# EEZ_DIB_MIO168_r1B5.net
KiCad netlist of a schematic drawn in EAGLE
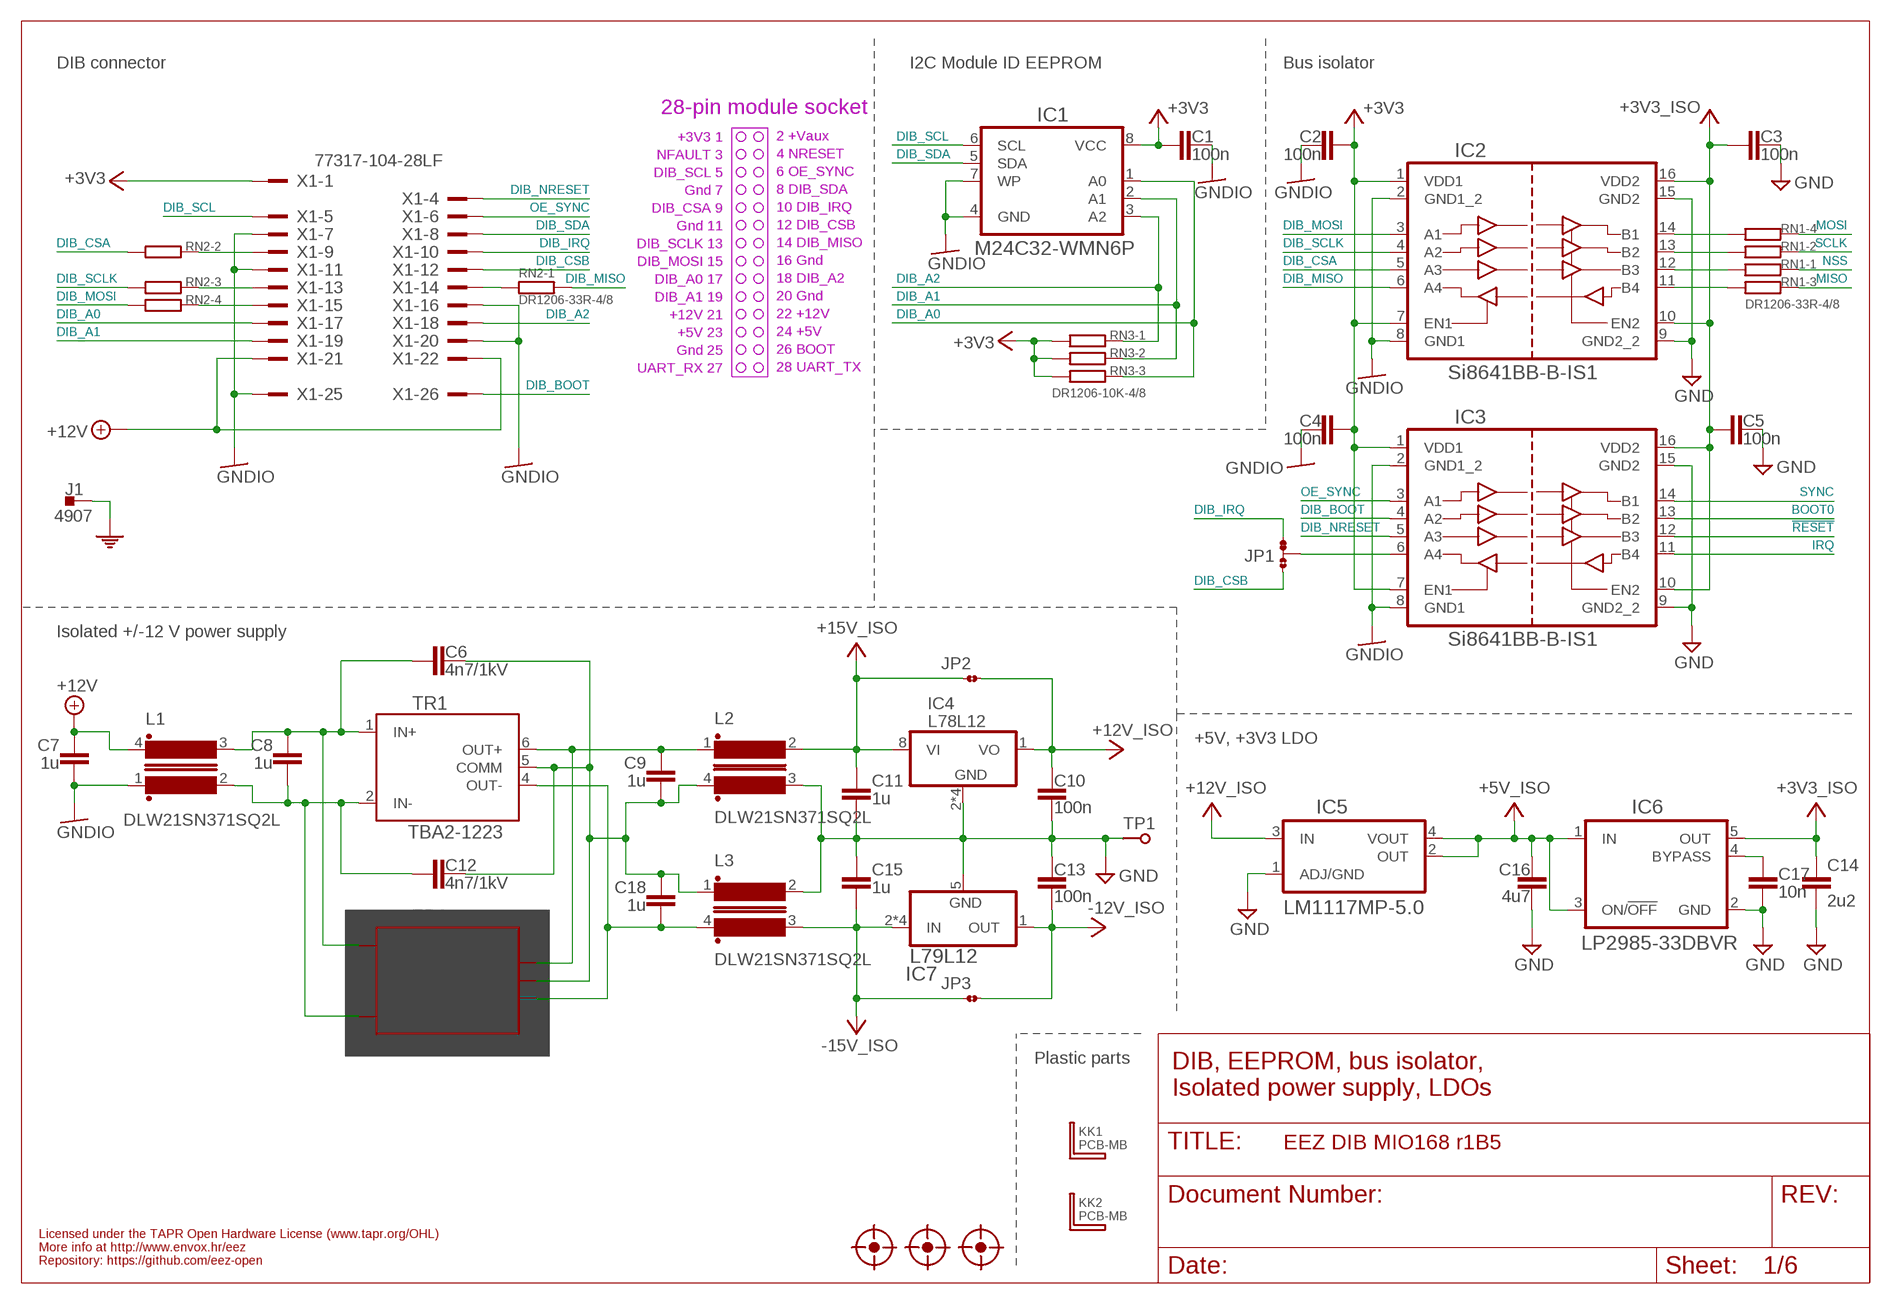
[diagram p0: schematic, sheet 1]
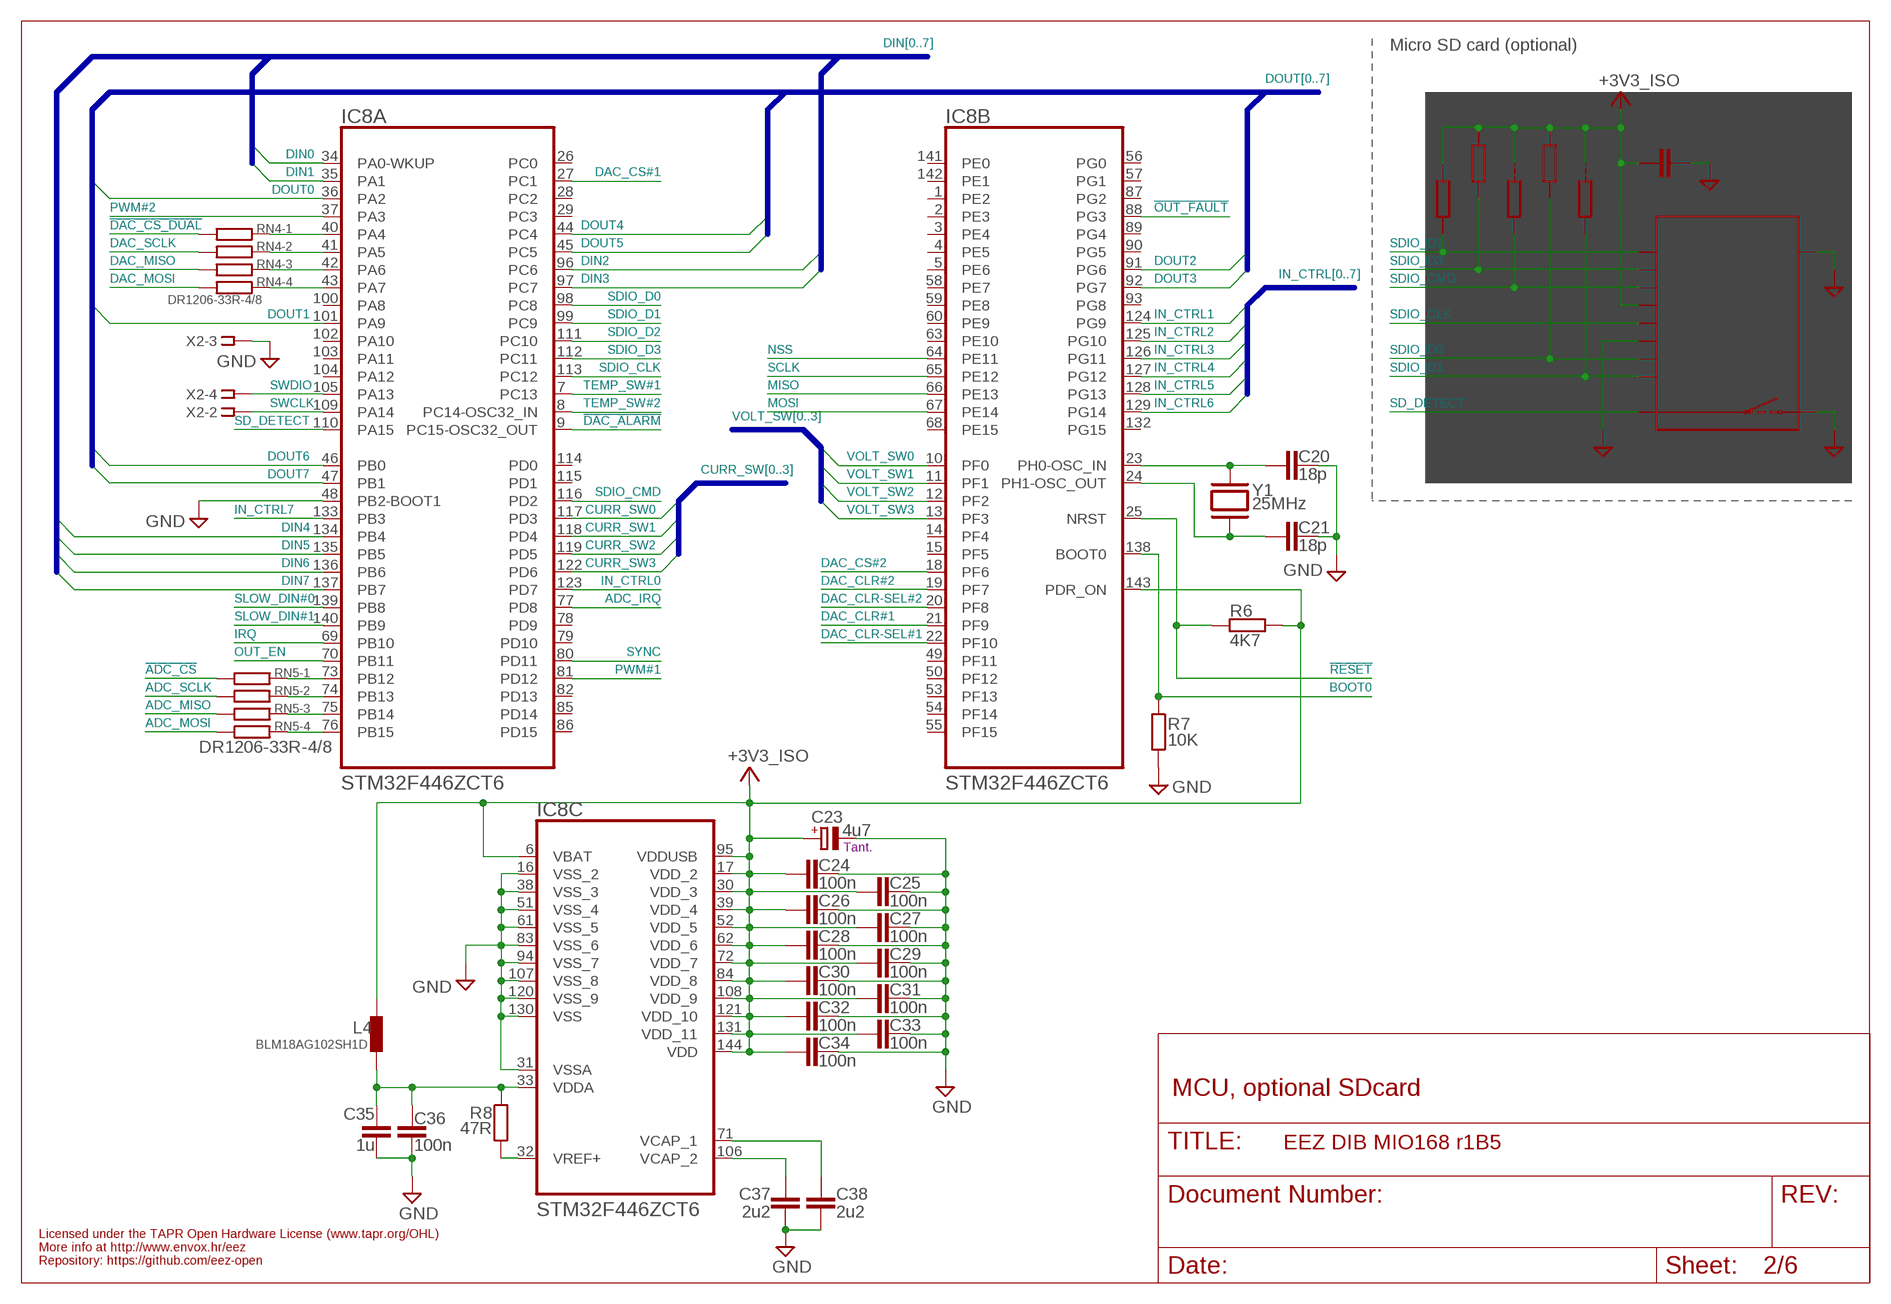
[diagram p1: schematic, sheet 2]
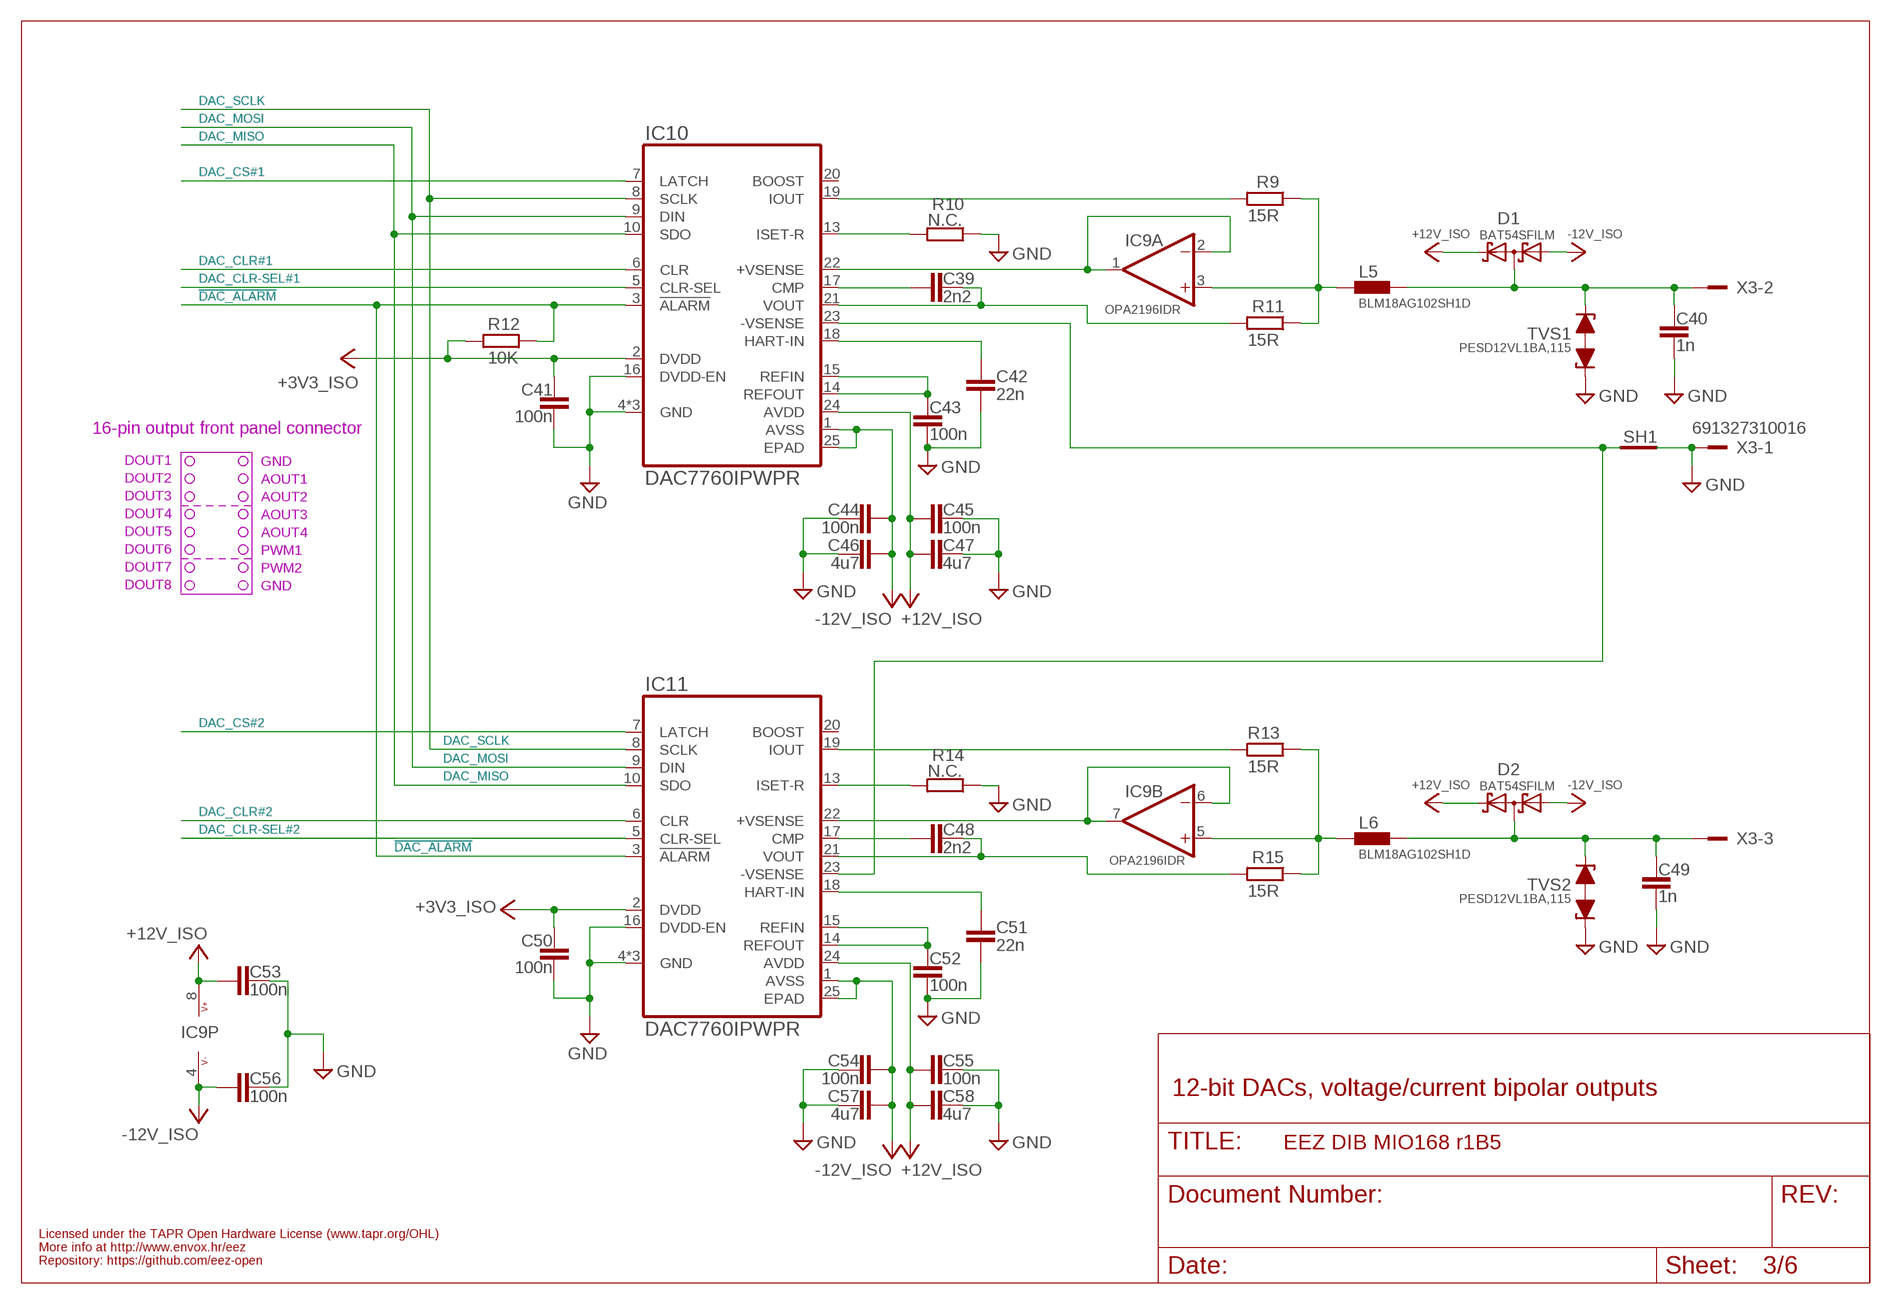
[diagram p2: schematic, sheet 3]
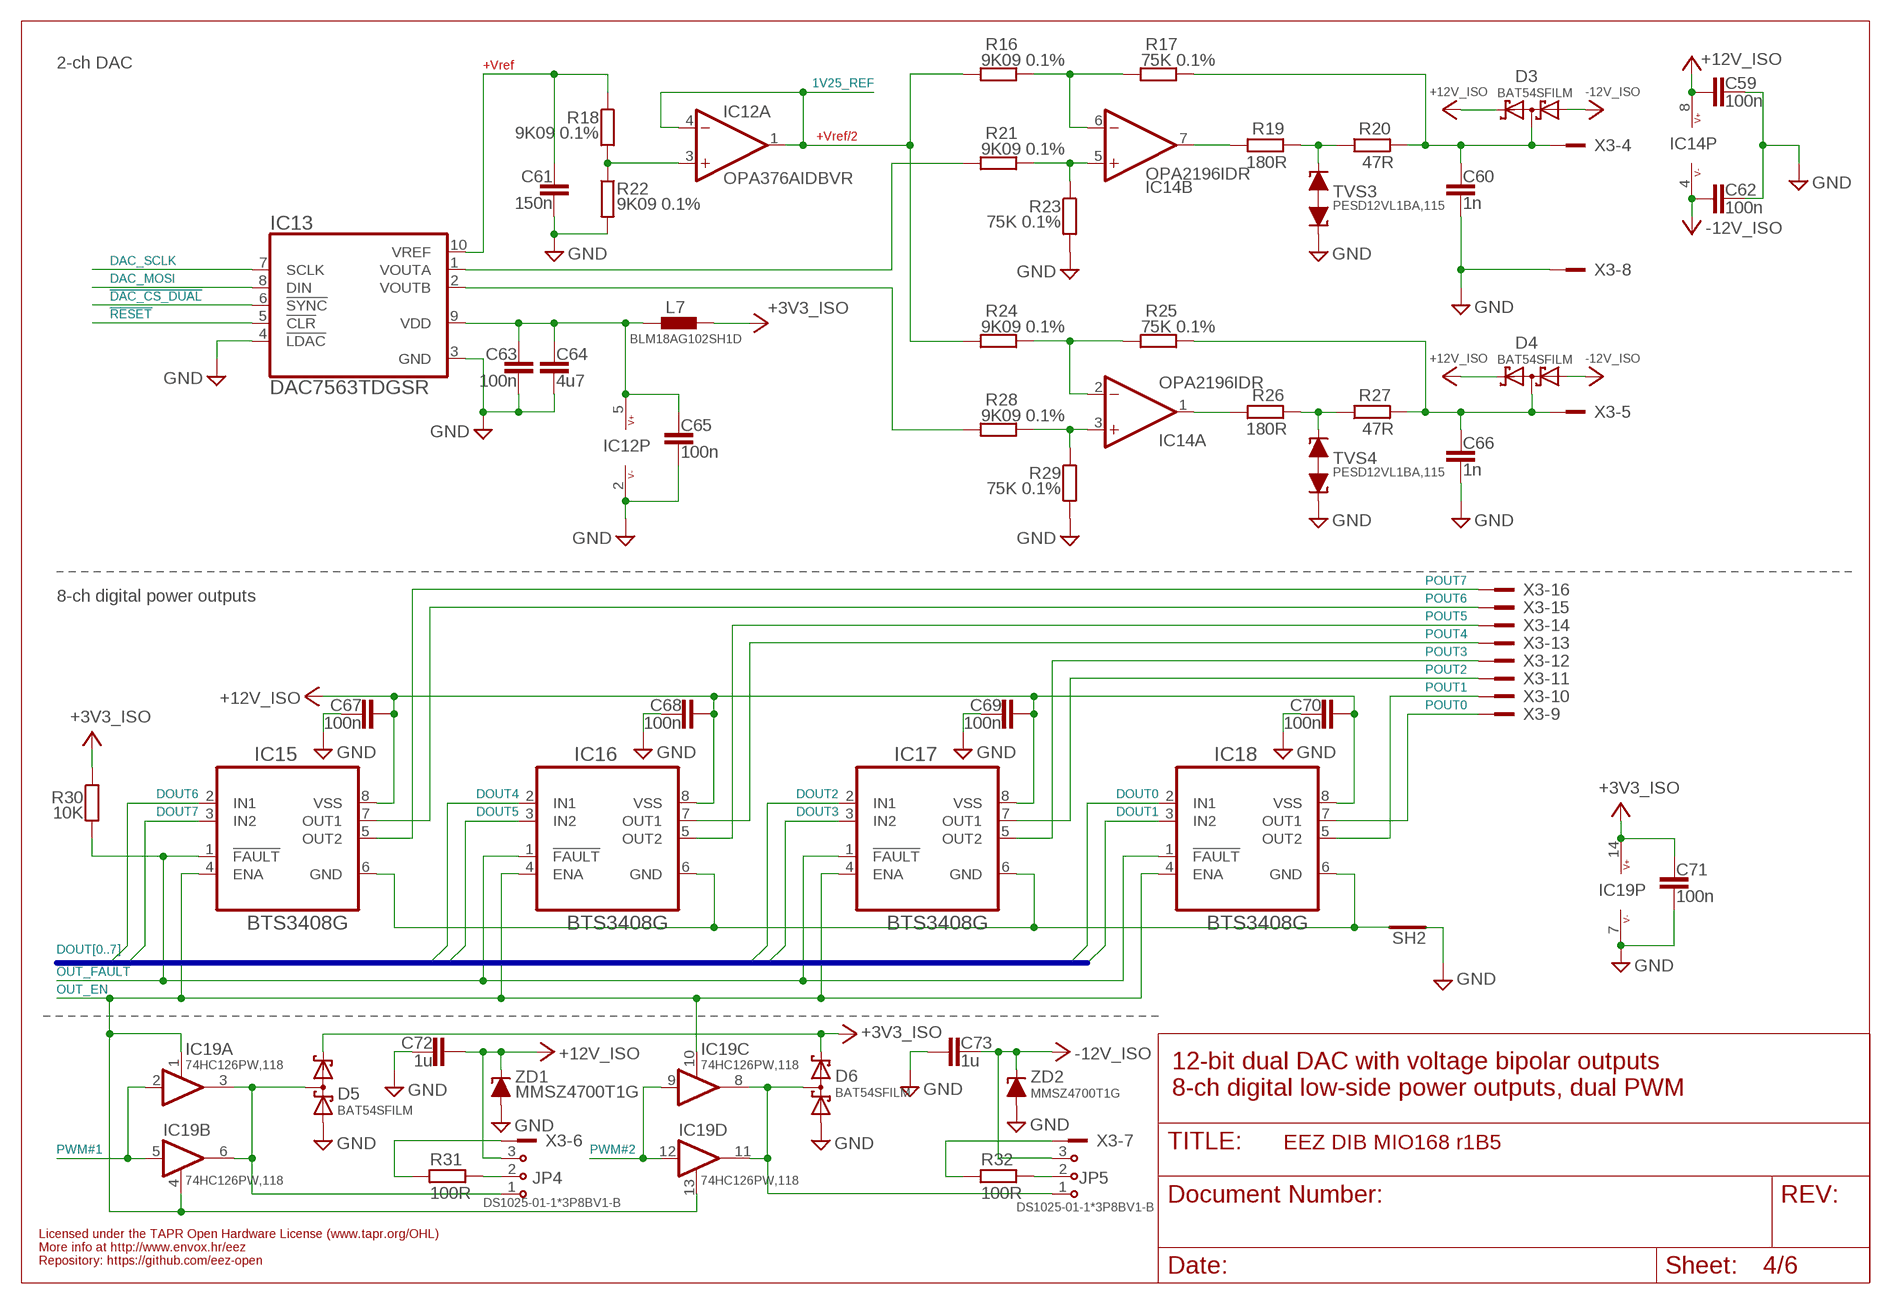
[diagram p3: schematic, sheet 4]
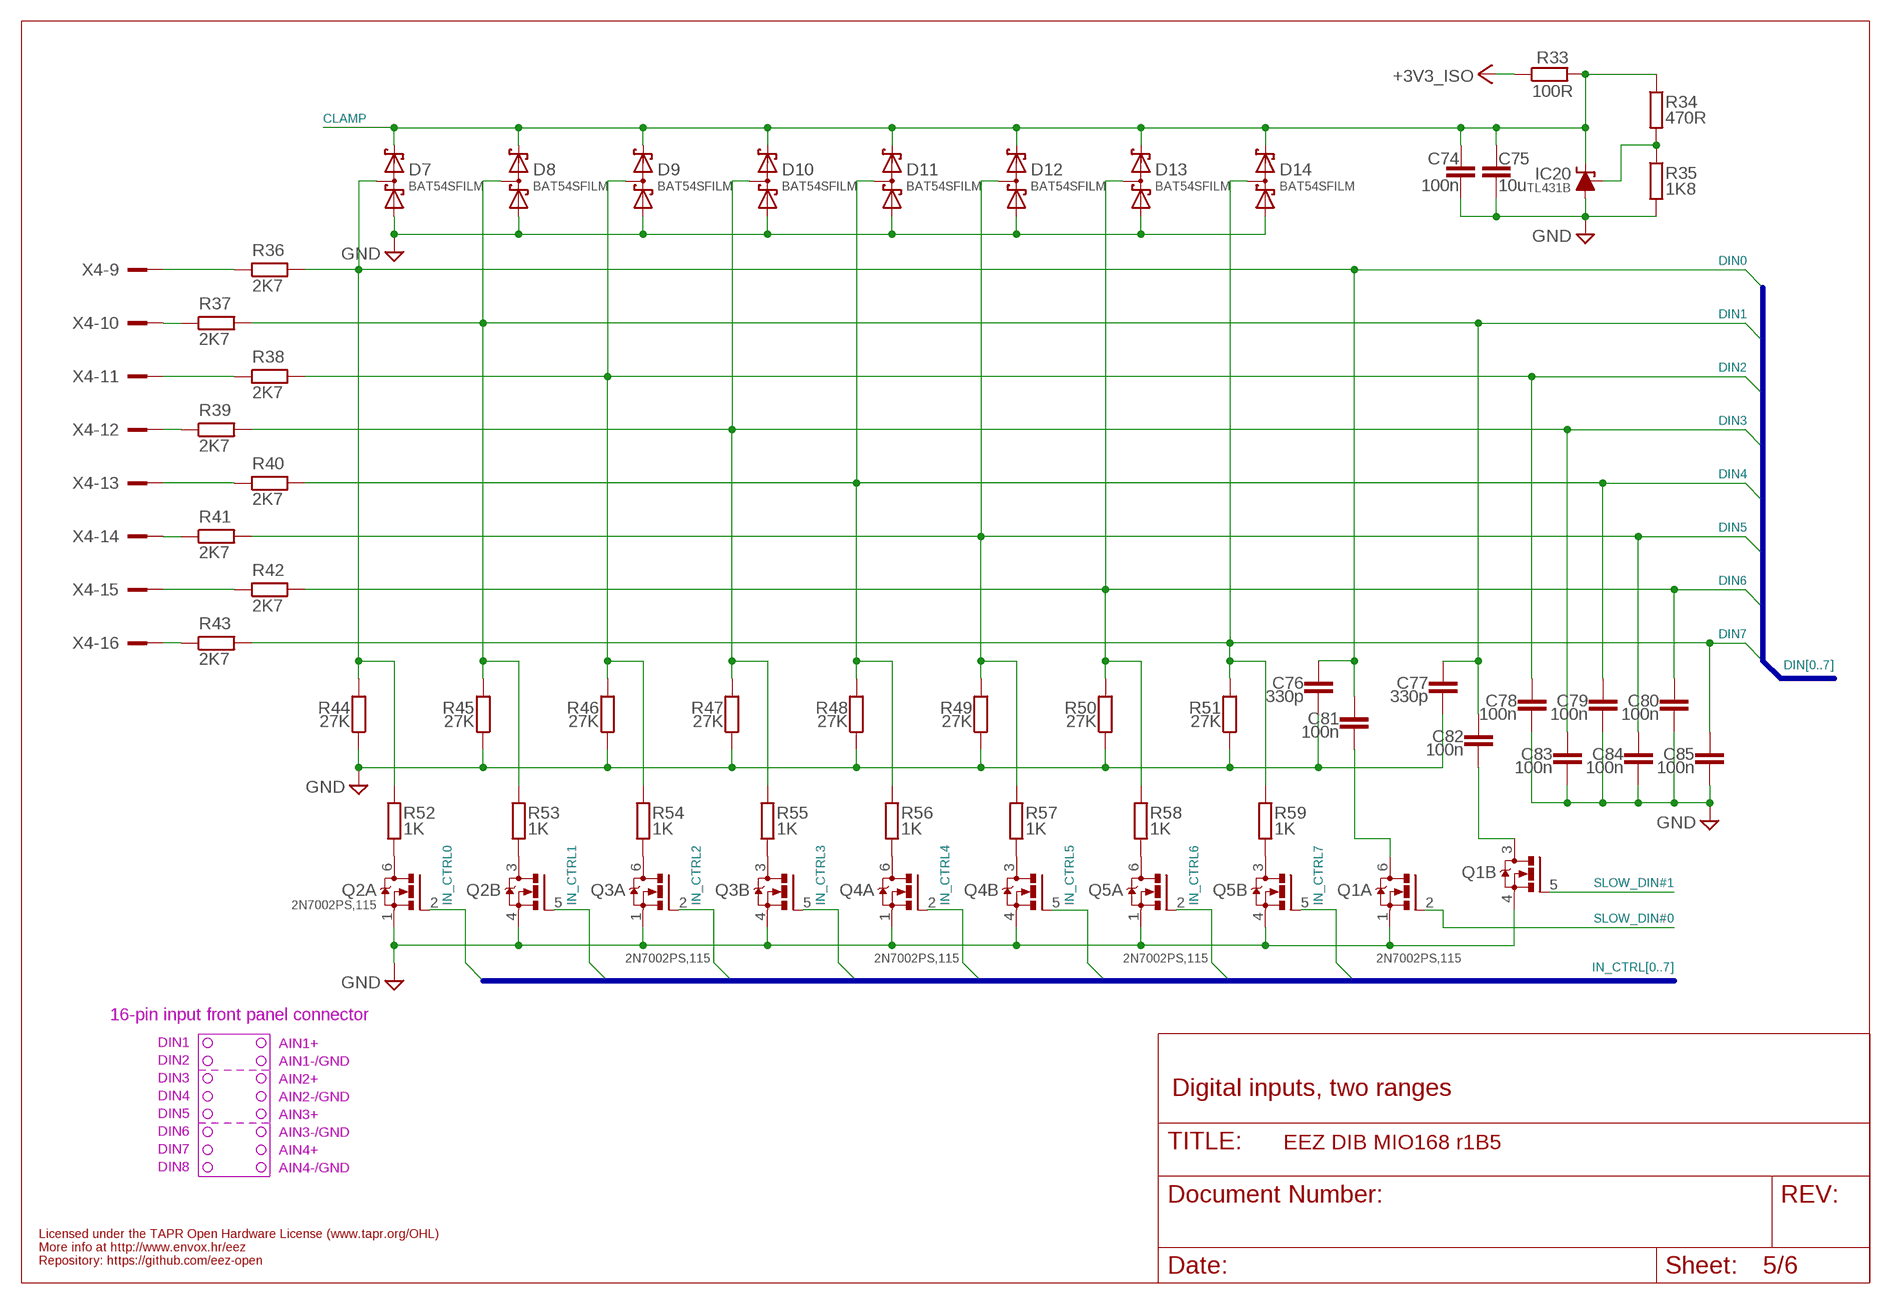
[diagram p4: schematic, sheet 5]
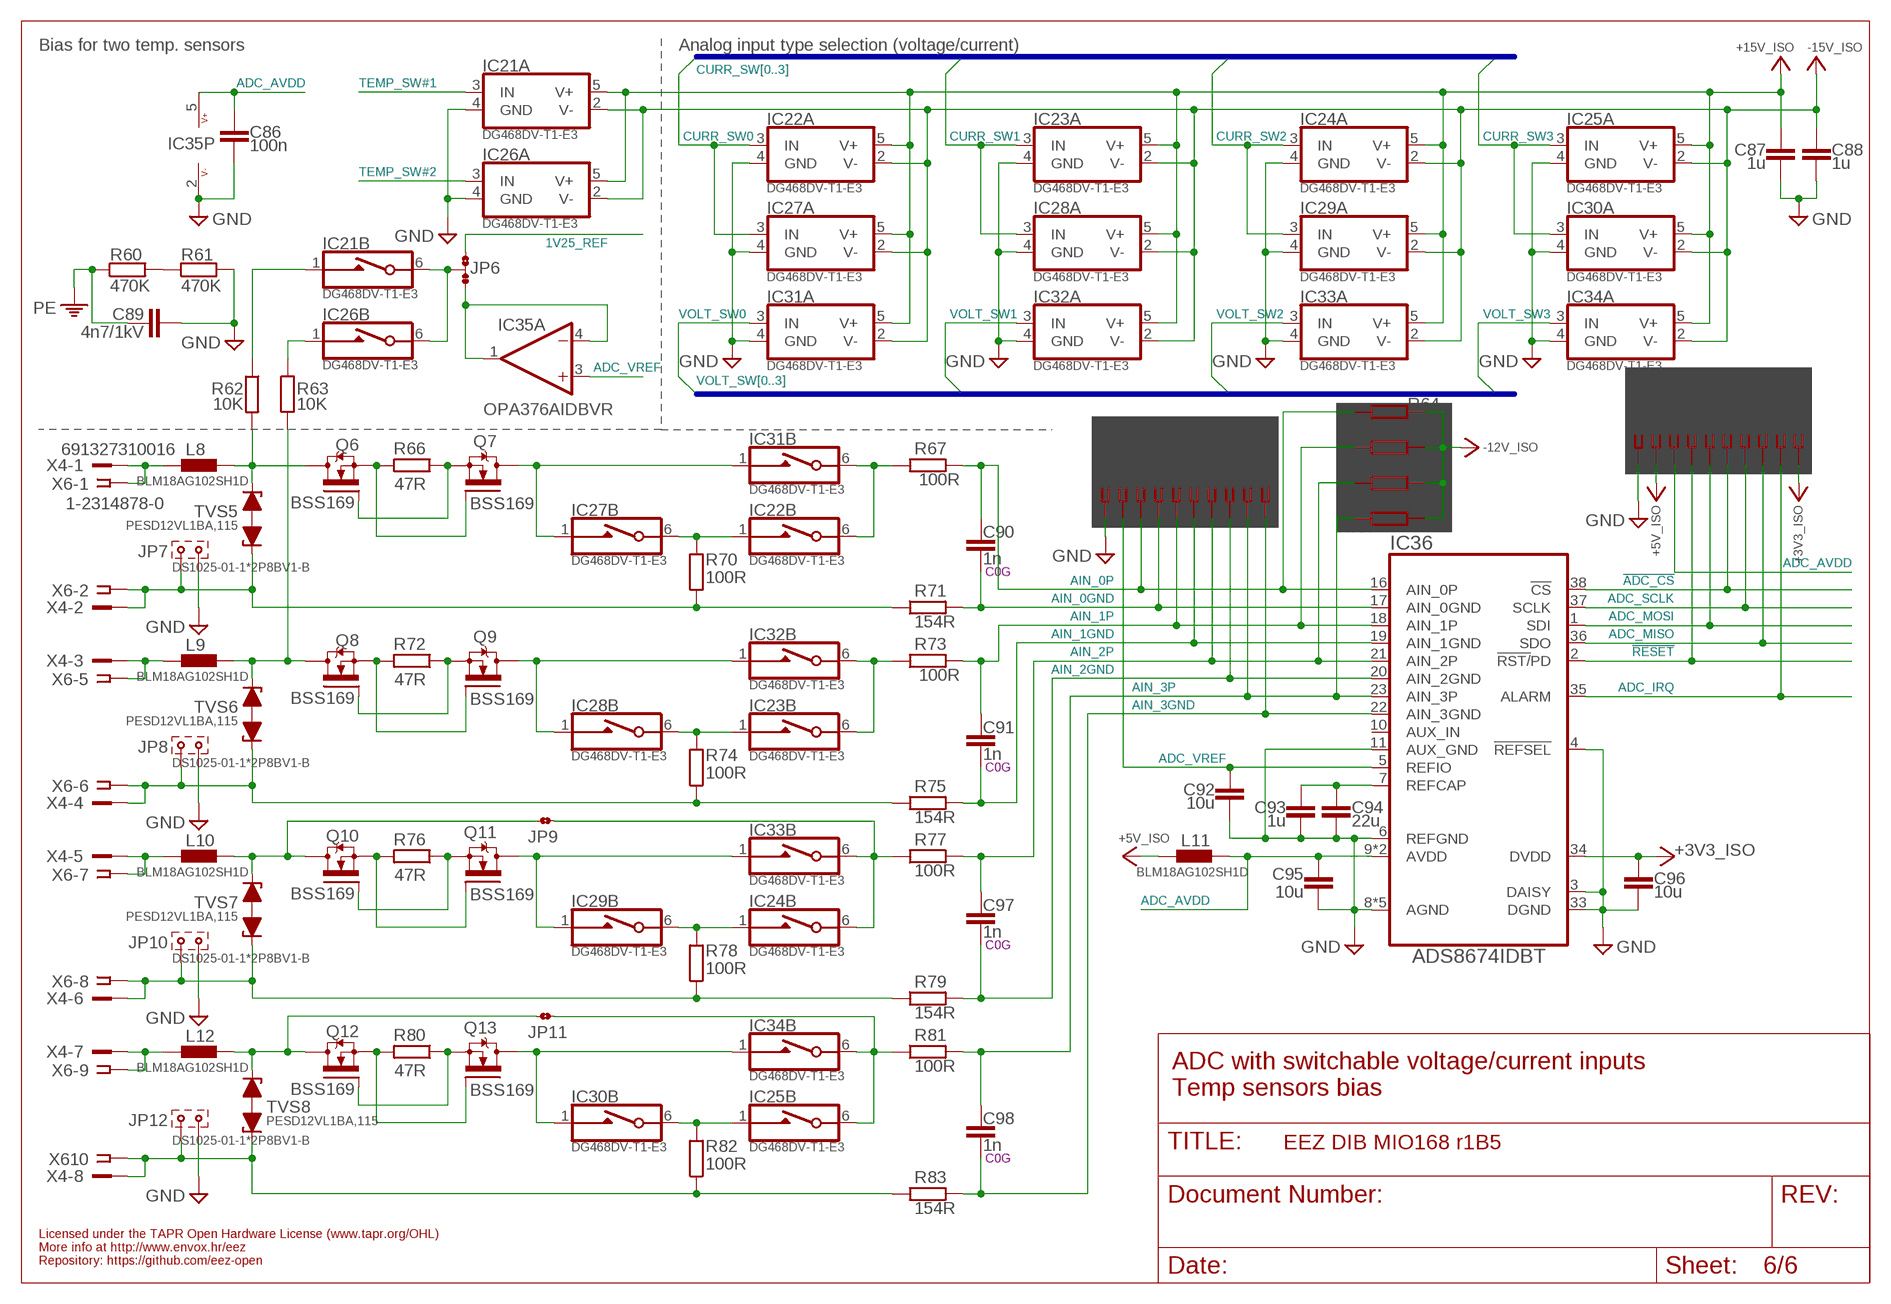
[diagram p5: schematic, sheet 6]

(export (version "E")
  (design (tool "Eeschema 10.0.6"))
  (components
    (comp (ref "C1")
      (value "100n")
      (footprint "eagle-import:C0603")
      (libsource (lib "eagle-import") (part "C-EUC0603"))
    )
    (comp (ref "C2")
      (value "100n")
      (footprint "eagle-import:C0603")
      (libsource (lib "eagle-import") (part "C-EUC0603"))
    )
    (comp (ref "C3")
      (value "100n")
      (footprint "eagle-import:C0603")
      (libsource (lib "eagle-import") (part "C-EUC0603"))
    )
    (comp (ref "C4")
      (value "100n")
      (footprint "eagle-import:C0603")
      (libsource (lib "eagle-import") (part "C-EUC0603"))
    )
    (comp (ref "C5")
      (value "100n")
      (footprint "eagle-import:C0603")
      (libsource (lib "eagle-import") (part "C-EUC0603"))
    )
    (comp (ref "C6")
      (value "4n7/1kV")
      (footprint "eagle-import:C1812")
      (libsource (lib "eagle-import") (part "C-EUC1812"))
    )
    (comp (ref "C7")
      (value "1u")
      (footprint "eagle-import:C0805")
      (libsource (lib "eagle-import") (part "C-EUC0805"))
    )
    (comp (ref "C8")
      (value "1u")
      (footprint "eagle-import:C0805")
      (libsource (lib "eagle-import") (part "C-EUC0805"))
    )
    (comp (ref "C9")
      (value "1u")
      (footprint "eagle-import:C0805")
      (libsource (lib "eagle-import") (part "C-EUC0805"))
    )
    (comp (ref "C10")
      (value "100n")
      (footprint "eagle-import:C0603")
      (libsource (lib "eagle-import") (part "C-EUC0603"))
    )
    (comp (ref "C11")
      (value "1u")
      (footprint "eagle-import:C0805")
      (libsource (lib "eagle-import") (part "C-EUC0805"))
    )
    (comp (ref "C12")
      (value "4n7/1kV")
      (footprint "eagle-import:C1812")
      (libsource (lib "eagle-import") (part "C-EUC1812"))
    )
    (comp (ref "C13")
      (value "100n")
      (footprint "eagle-import:C0603")
      (libsource (lib "eagle-import") (part "C-EUC0603"))
    )
    (comp (ref "C14")
      (value "2u2")
      (footprint "eagle-import:C0805")
      (libsource (lib "eagle-import") (part "C-EUC0805"))
    )
    (comp (ref "C15")
      (value "1u")
      (footprint "eagle-import:C0805")
      (libsource (lib "eagle-import") (part "C-EUC0805"))
    )
    (comp (ref "C16")
      (value "4u7")
      (footprint "eagle-import:C0805")
      (libsource (lib "eagle-import") (part "C-EUC0805"))
    )
    (comp (ref "C17")
      (value "10n")
      (footprint "eagle-import:C0805")
      (libsource (lib "eagle-import") (part "C-EUC0805"))
    )
    (comp (ref "C18")
      (value "1u")
      (footprint "eagle-import:C0805")
      (libsource (lib "eagle-import") (part "C-EUC0805"))
    )
    (comp (ref "FM1")
      (value "FIDUCIAL_2")
      (footprint "eagle-import:FIDUCIAL_DUAL")
      (libsource (lib "eagle-import") (part "FIDUCIAL_2"))
    )
    (comp (ref "FM2")
      (value "FIDUCIAL_2")
      (footprint "eagle-import:FIDUCIAL_DUAL")
      (libsource (lib "eagle-import") (part "FIDUCIAL_2"))
    )
    (comp (ref "FM3")
      (value "FIDUCIAL_2")
      (footprint "eagle-import:FIDUCIAL_DUAL")
      (libsource (lib "eagle-import") (part "FIDUCIAL_2"))
    )
    (comp (ref "IC1")
      (value "M24C32-WMN6P")
      (footprint "eagle-import:SOIC127P600X173-8N")
      (libsource (lib "eagle-import") (part "AT24CXXSOIC8"))
    )
    (comp (ref "IC2")
      (value "Si8641BB-B-IS1")
      (footprint "eagle-import:SOIC-16")
      (libsource (lib "eagle-import") (part "SI8641NSOIC-16"))
    )
    (comp (ref "IC3")
      (value "Si8641BB-B-IS1")
      (footprint "eagle-import:SOIC-16")
      (libsource (lib "eagle-import") (part "SI8641NSOIC-16"))
    )
    (comp (ref "IC4")
      (value "L78L12")
      (footprint "eagle-import:SOIC127P600X173-8N")
      (libsource (lib "eagle-import") (part "MC78LXXSOIC8"))
    )
    (comp (ref "IC5")
      (value "LM1117MP-5.0")
      (footprint "eagle-import:SOT230P696X180-4N")
      (libsource (lib "eagle-import") (part "LM1117MP-5.0"))
    )
    (comp (ref "IC6")
      (value "LP2985-33DBVR")
      (footprint "eagle-import:SOT95P270X145-5N")
      (libsource (lib "eagle-import") (part "LP2985"))
    )
    (comp (ref "IC7")
      (value "L79L12")
      (footprint "eagle-import:SOIC127P600X173-8N")
      (libsource (lib "eagle-import") (part "MC79LXXSOIC"))
    )
    (comp (ref "J1")
      (value "4907")
      (footprint "eagle-import:PCB_TAB-4907")
      (libsource (lib "eagle-import") (part "PCB_TAB-4907"))
    )
    (comp (ref "JP1")
      (value "JP3-CUT-0805-ROTATED")
      (footprint "eagle-import:JP3-0805-CUT2")
      (libsource (lib "eagle-import") (part "JP3-CUT-0805-ROTATED"))
    )
    (comp (ref "JP2")
      (value "JP2-CUT-0805")
      (footprint "eagle-import:R_0805")
      (libsource (lib "eagle-import") (part "JP2-CUT-0805"))
    )
    (comp (ref "JP3")
      (value "JP2-CUT-0805")
      (footprint "eagle-import:R_0805")
      (libsource (lib "eagle-import") (part "JP2-CUT-0805"))
    )
    (comp (ref "KK1")
      (value "PCB-MB")
      (footprint "eagle-import:PCB-MB")
      (libsource (lib "eagle-import") (part "PCB-MB"))
    )
    (comp (ref "KK2")
      (value "PCB-MB")
      (footprint "eagle-import:PCB-MB")
      (libsource (lib "eagle-import") (part "PCB-MB"))
    )
    (comp (ref "L1")
      (value "DLW21SN371SQ2L")
      (footprint "eagle-import:MURATA_DLW21S")
      (libsource (lib "eagle-import") (part "DLW21S"))
    )
    (comp (ref "L2")
      (value "DLW21SN371SQ2L")
      (footprint "eagle-import:MURATA_DLW21S")
      (libsource (lib "eagle-import") (part "DLW21S"))
    )
    (comp (ref "L3")
      (value "DLW21SN371SQ2L")
      (footprint "eagle-import:MURATA_DLW21S")
      (libsource (lib "eagle-import") (part "DLW21S"))
    )
    (comp (ref "RN1")
      (value "DR1206-33R-4/8")
      (footprint "eagle-import:CAY16")
      (libsource (lib "eagle-import") (part "R_ARRAY4"))
    )
    (comp (ref "RN2")
      (value "DR1206-33R-4/8")
      (footprint "eagle-import:CAY16")
      (libsource (lib "eagle-import") (part "R_ARRAY4"))
    )
    (comp (ref "RN3")
      (value "DR1206-10K-4/8")
      (footprint "eagle-import:CAY16")
      (libsource (lib "eagle-import") (part "R_ARRAY4"))
    )
    (comp (ref "TP1")
      (value "PCB_TEST_TABSHIELD")
      (footprint "eagle-import:PCB_SHIELD_TAB")
      (libsource (lib "eagle-import") (part "PCB_TEST_TABSHIELD"))
    )
    (comp (ref "TR1")
      (value "TBA2-1223")
      (footprint "eagle-import:TBA2")
      (libsource (lib "eagle-import") (part "TBA-DUAL-2W"))
    )
    (comp (ref "TR2")
      (value "MDD02M-15")
      (footprint "eagle-import:MDD02")
      (libsource (lib "eagle-import") (part "MDD02"))
    )
    (comp (ref "X1")
      (value "77317-104-28LF")
      (footprint "eagle-import:77317-104-28LF")
      (libsource (lib "eagle-import") (part "77317-104-28LF"))
    )
    (comp (ref "C74")
      (value "100n")
      (footprint "eagle-import:C0603")
      (libsource (lib "eagle-import") (part "C-EUC0603"))
    )
    (comp (ref "C75")
      (value "10u")
      (footprint "eagle-import:C1206")
      (libsource (lib "eagle-import") (part "C-EUC1206"))
    )
    (comp (ref "C76")
      (value "330p")
      (footprint "eagle-import:C0805")
      (libsource (lib "eagle-import") (part "C-EUC0805"))
    )
    (comp (ref "C77")
      (value "330p")
      (footprint "eagle-import:C0805")
      (libsource (lib "eagle-import") (part "C-EUC0805"))
    )
    (comp (ref "C78")
      (value "100n")
      (footprint "eagle-import:C0603")
      (libsource (lib "eagle-import") (part "C-EUC0603"))
    )
    (comp (ref "C79")
      (value "100n")
      (footprint "eagle-import:C0603")
      (libsource (lib "eagle-import") (part "C-EUC0603"))
    )
    (comp (ref "C80")
      (value "100n")
      (footprint "eagle-import:C0603")
      (libsource (lib "eagle-import") (part "C-EUC0603"))
    )
    (comp (ref "C81")
      (value "100n")
      (footprint "eagle-import:C0603")
      (libsource (lib "eagle-import") (part "C-EUC0603"))
    )
    (comp (ref "C82")
      (value "100n")
      (footprint "eagle-import:C0603")
      (libsource (lib "eagle-import") (part "C-EUC0603"))
    )
    (comp (ref "C83")
      (value "100n")
      (footprint "eagle-import:C0603")
      (libsource (lib "eagle-import") (part "C-EUC0603"))
    )
    (comp (ref "C84")
      (value "100n")
      (footprint "eagle-import:C0603")
      (libsource (lib "eagle-import") (part "C-EUC0603"))
    )
    (comp (ref "C85")
      (value "100n")
      (footprint "eagle-import:C0603")
      (libsource (lib "eagle-import") (part "C-EUC0603"))
    )
    (comp (ref "D7")
      (value "BAT54SFILM")
      (footprint "eagle-import:SOT23")
      (libsource (lib "eagle-import") (part "BAT54S"))
    )
    (comp (ref "D8")
      (value "BAT54SFILM")
      (footprint "eagle-import:SOT23")
      (libsource (lib "eagle-import") (part "BAT54S"))
    )
    (comp (ref "D9")
      (value "BAT54SFILM")
      (footprint "eagle-import:SOT23")
      (libsource (lib "eagle-import") (part "BAT54S"))
    )
    (comp (ref "D10")
      (value "BAT54SFILM")
      (footprint "eagle-import:SOT23")
      (libsource (lib "eagle-import") (part "BAT54S"))
    )
    (comp (ref "D11")
      (value "BAT54SFILM")
      (footprint "eagle-import:SOT23")
      (libsource (lib "eagle-import") (part "BAT54S"))
    )
    (comp (ref "D12")
      (value "BAT54SFILM")
      (footprint "eagle-import:SOT23")
      (libsource (lib "eagle-import") (part "BAT54S"))
    )
    (comp (ref "D13")
      (value "BAT54SFILM")
      (footprint "eagle-import:SOT23")
      (libsource (lib "eagle-import") (part "BAT54S"))
    )
    (comp (ref "D14")
      (value "BAT54SFILM")
      (footprint "eagle-import:SOT23")
      (libsource (lib "eagle-import") (part "BAT54S"))
    )
    (comp (ref "IC20")
      (value "TL431B")
      (footprint "eagle-import:SOT103P240X110-3N")
      (libsource (lib "eagle-import") (part "TL431"))
    )
    (comp (ref "Q1")
      (value "2N7002PS,115")
      (footprint "eagle-import:SC88")
      (libsource (lib "eagle-import") (part "2N7002PS,115"))
    )
    (comp (ref "Q2")
      (value "2N7002PS,115")
      (footprint "eagle-import:SC88")
      (libsource (lib "eagle-import") (part "2N7002PS,115"))
    )
    (comp (ref "Q3")
      (value "2N7002PS,115")
      (footprint "eagle-import:SC88")
      (libsource (lib "eagle-import") (part "2N7002PS,115"))
    )
    (comp (ref "Q4")
      (value "2N7002PS,115")
      (footprint "eagle-import:SC88")
      (libsource (lib "eagle-import") (part "2N7002PS,115"))
    )
    (comp (ref "Q5")
      (value "2N7002PS,115")
      (footprint "eagle-import:SC88")
      (libsource (lib "eagle-import") (part "2N7002PS,115"))
    )
    (comp (ref "R33")
      (value "100R")
      (footprint "eagle-import:R0805")
      (libsource (lib "eagle-import") (part "R-EU_R0805"))
    )
    (comp (ref "R34")
      (value "470R")
      (footprint "eagle-import:R0805")
      (libsource (lib "eagle-import") (part "R-EU_R0805"))
    )
    (comp (ref "R35")
      (value "1K8")
      (footprint "eagle-import:R0805")
      (libsource (lib "eagle-import") (part "R-EU_R0805"))
    )
    (comp (ref "R36")
      (value "2K7")
      (footprint "eagle-import:R1206")
      (libsource (lib "eagle-import") (part "R-EU_R1206"))
    )
    (comp (ref "R37")
      (value "2K7")
      (footprint "eagle-import:R1206")
      (libsource (lib "eagle-import") (part "R-EU_R1206"))
    )
    (comp (ref "R38")
      (value "2K7")
      (footprint "eagle-import:R1206")
      (libsource (lib "eagle-import") (part "R-EU_R1206"))
    )
    (comp (ref "R39")
      (value "2K7")
      (footprint "eagle-import:R1206")
      (libsource (lib "eagle-import") (part "R-EU_R1206"))
    )
    (comp (ref "R40")
      (value "2K7")
      (footprint "eagle-import:R1206")
      (libsource (lib "eagle-import") (part "R-EU_R1206"))
    )
    (comp (ref "R41")
      (value "2K7")
      (footprint "eagle-import:R1206")
      (libsource (lib "eagle-import") (part "R-EU_R1206"))
    )
    (comp (ref "R42")
      (value "2K7")
      (footprint "eagle-import:R1206")
      (libsource (lib "eagle-import") (part "R-EU_R1206"))
    )
    (comp (ref "R43")
      (value "2K7")
      (footprint "eagle-import:R1206")
      (libsource (lib "eagle-import") (part "R-EU_R1206"))
    )
    (comp (ref "R44")
      (value "27K")
      (footprint "eagle-import:R0805")
      (libsource (lib "eagle-import") (part "R-EU_R0805"))
    )
    (comp (ref "R45")
      (value "27K")
      (footprint "eagle-import:R0805")
      (libsource (lib "eagle-import") (part "R-EU_R0805"))
    )
    (comp (ref "R46")
      (value "27K")
      (footprint "eagle-import:R0805")
      (libsource (lib "eagle-import") (part "R-EU_R0805"))
    )
    (comp (ref "R47")
      (value "27K")
      (footprint "eagle-import:R0805")
      (libsource (lib "eagle-import") (part "R-EU_R0805"))
    )
    (comp (ref "R48")
      (value "27K")
      (footprint "eagle-import:R0805")
      (libsource (lib "eagle-import") (part "R-EU_R0805"))
    )
    (comp (ref "R49")
      (value "27K")
      (footprint "eagle-import:R0805")
      (libsource (lib "eagle-import") (part "R-EU_R0805"))
    )
    (comp (ref "R50")
      (value "27K")
      (footprint "eagle-import:R0805")
      (libsource (lib "eagle-import") (part "R-EU_R0805"))
    )
    (comp (ref "R51")
      (value "27K")
      (footprint "eagle-import:R0805")
      (libsource (lib "eagle-import") (part "R-EU_R0805"))
    )
    (comp (ref "R52")
      (value "1K")
      (footprint "eagle-import:R0805")
      (libsource (lib "eagle-import") (part "R-EU_R0805"))
    )
    (comp (ref "R53")
      (value "1K")
      (footprint "eagle-import:R0805")
      (libsource (lib "eagle-import") (part "R-EU_R0805"))
    )
    (comp (ref "R54")
      (value "1K")
      (footprint "eagle-import:R0805")
      (libsource (lib "eagle-import") (part "R-EU_R0805"))
    )
    (comp (ref "R55")
      (value "1K")
      (footprint "eagle-import:R0805")
      (libsource (lib "eagle-import") (part "R-EU_R0805"))
    )
    (comp (ref "R56")
      (value "1K")
      (footprint "eagle-import:R0805")
      (libsource (lib "eagle-import") (part "R-EU_R0805"))
    )
    (comp (ref "R57")
      (value "1K")
      (footprint "eagle-import:R0805")
      (libsource (lib "eagle-import") (part "R-EU_R0805"))
    )
    (comp (ref "R58")
      (value "1K")
      (footprint "eagle-import:R0805")
      (libsource (lib "eagle-import") (part "R-EU_R0805"))
    )
    (comp (ref "R59")
      (value "1K")
      (footprint "eagle-import:R0805")
      (libsource (lib "eagle-import") (part "R-EU_R0805"))
    )
    (comp (ref "X4")
      (value "691327310016")
      (footprint "eagle-import:691327310016")
      (libsource (lib "eagle-import") (part "691327310016"))
    )
    (comp (ref "C39")
      (value "2n2")
      (footprint "eagle-import:C0805")
      (libsource (lib "eagle-import") (part "C-EUC0805"))
    )
    (comp (ref "C40")
      (value "1n")
      (footprint "eagle-import:C0805")
      (libsource (lib "eagle-import") (part "C-EUC0805"))
    )
    (comp (ref "C41")
      (value "100n")
      (footprint "eagle-import:C0603")
      (libsource (lib "eagle-import") (part "C-EUC0603"))
    )
    (comp (ref "C42")
      (value "22n")
      (footprint "eagle-import:C0805")
      (libsource (lib "eagle-import") (part "C-EUC0805"))
    )
    (comp (ref "C43")
      (value "100n")
      (footprint "eagle-import:C0603")
      (libsource (lib "eagle-import") (part "C-EUC0603"))
    )
    (comp (ref "C44")
      (value "100n")
      (footprint "eagle-import:C0603")
      (libsource (lib "eagle-import") (part "C-EUC0603"))
    )
    (comp (ref "C45")
      (value "100n")
      (footprint "eagle-import:C0603")
      (libsource (lib "eagle-import") (part "C-EUC0603"))
    )
    (comp (ref "C46")
      (value "4u7")
      (footprint "eagle-import:C0805")
      (libsource (lib "eagle-import") (part "C-EUC0805"))
    )
    (comp (ref "C47")
      (value "4u7")
      (footprint "eagle-import:C0805")
      (libsource (lib "eagle-import") (part "C-EUC0805"))
    )
    (comp (ref "C48")
      (value "2n2")
      (footprint "eagle-import:C0805")
      (libsource (lib "eagle-import") (part "C-EUC0805"))
    )
    (comp (ref "C49")
      (value "1n")
      (footprint "eagle-import:C0805")
      (libsource (lib "eagle-import") (part "C-EUC0805"))
    )
    (comp (ref "C50")
      (value "100n")
      (footprint "eagle-import:C0603")
      (libsource (lib "eagle-import") (part "C-EUC0603"))
    )
    (comp (ref "C51")
      (value "22n")
      (footprint "eagle-import:C0805")
      (libsource (lib "eagle-import") (part "C-EUC0805"))
    )
    (comp (ref "C52")
      (value "100n")
      (footprint "eagle-import:C0603")
      (libsource (lib "eagle-import") (part "C-EUC0603"))
    )
    (comp (ref "C53")
      (value "100n")
      (footprint "eagle-import:C0603")
      (libsource (lib "eagle-import") (part "C-EUC0603"))
    )
    (comp (ref "C54")
      (value "100n")
      (footprint "eagle-import:C0603")
      (libsource (lib "eagle-import") (part "C-EUC0603"))
    )
    (comp (ref "C55")
      (value "100n")
      (footprint "eagle-import:C0603")
      (libsource (lib "eagle-import") (part "C-EUC0603"))
    )
    (comp (ref "C56")
      (value "100n")
      (footprint "eagle-import:C0603")
      (libsource (lib "eagle-import") (part "C-EUC0603"))
    )
    (comp (ref "C57")
      (value "4u7")
      (footprint "eagle-import:C0805")
      (libsource (lib "eagle-import") (part "C-EUC0805"))
    )
    (comp (ref "C58")
      (value "4u7")
      (footprint "eagle-import:C0805")
      (libsource (lib "eagle-import") (part "C-EUC0805"))
    )
    (comp (ref "D1")
      (value "BAT54SFILM")
      (footprint "eagle-import:SOT23")
      (libsource (lib "eagle-import") (part "BAT54S"))
    )
    (comp (ref "D2")
      (value "BAT54SFILM")
      (footprint "eagle-import:SOT23")
      (libsource (lib "eagle-import") (part "BAT54S"))
    )
    (comp (ref "IC9")
      (value "OPA2196IDR")
      (footprint "eagle-import:SOIC127P600X173-8N")
      (libsource (lib "eagle-import") (part "TL072SOIC8"))
    )
    (comp (ref "IC10")
      (value "DAC7760IPWPR")
      (footprint "eagle-import:PWP24")
      (libsource (lib "eagle-import") (part "DAC7760IPWPR"))
    )
    (comp (ref "IC11")
      (value "DAC7760IPWPR")
      (footprint "eagle-import:PWP24")
      (libsource (lib "eagle-import") (part "DAC7760IPWPR"))
    )
    (comp (ref "L5")
      (value "BLM18AG102SH1D")
      (footprint "eagle-import:BEAD0603")
      (libsource (lib "eagle-import") (part "FERRITE_BEAD0603"))
    )
    (comp (ref "L6")
      (value "BLM18AG102SH1D")
      (footprint "eagle-import:BEAD0603")
      (libsource (lib "eagle-import") (part "FERRITE_BEAD0603"))
    )
    (comp (ref "R9")
      (value "15R")
      (footprint "eagle-import:R0805")
      (libsource (lib "eagle-import") (part "R-EU_R0805"))
    )
    (comp (ref "R10")
      (value "N.C.")
      (footprint "eagle-import:R0805")
      (libsource (lib "eagle-import") (part "R-EU_R0805"))
    )
    (comp (ref "R11")
      (value "15R")
      (footprint "eagle-import:R0805")
      (libsource (lib "eagle-import") (part "R-EU_R0805"))
    )
    (comp (ref "R12")
      (value "10K")
      (footprint "eagle-import:R0805")
      (libsource (lib "eagle-import") (part "R-EU_R0805"))
    )
    (comp (ref "R13")
      (value "15R")
      (footprint "eagle-import:R0805")
      (libsource (lib "eagle-import") (part "R-EU_R0805"))
    )
    (comp (ref "R14")
      (value "N.C.")
      (footprint "eagle-import:R0805")
      (libsource (lib "eagle-import") (part "R-EU_R0805"))
    )
    (comp (ref "R15")
      (value "15R")
      (footprint "eagle-import:R0805")
      (libsource (lib "eagle-import") (part "R-EU_R0805"))
    )
    (comp (ref "SH1")
      (value "SHORTNOHOLE")
      (footprint "eagle-import:SHORT_NOHOLE")
      (libsource (lib "eagle-import") (part "SHORTNOHOLE"))
    )
    (comp (ref "TVS1")
      (value "PESD12VL1BA,115")
      (footprint "eagle-import:SOD323-BIDIR")
      (libsource (lib "eagle-import") (part "PESDXL1BA"))
    )
    (comp (ref "TVS2")
      (value "PESD12VL1BA,115")
      (footprint "eagle-import:SOD323-BIDIR")
      (libsource (lib "eagle-import") (part "PESDXL1BA"))
    )
    (comp (ref "X3")
      (value "691327310016")
      (footprint "eagle-import:691327310016")
      (libsource (lib "eagle-import") (part "691327310016"))
    )
    (comp (ref "C59")
      (value "100n")
      (footprint "eagle-import:C0603")
      (libsource (lib "eagle-import") (part "C-EUC0603"))
    )
    (comp (ref "C60")
      (value "1n")
      (footprint "eagle-import:C0805")
      (libsource (lib "eagle-import") (part "C-EUC0805"))
    )
    (comp (ref "C61")
      (value "150n")
      (footprint "eagle-import:C0805")
      (libsource (lib "eagle-import") (part "C-EUC0805"))
    )
    (comp (ref "C62")
      (value "100n")
      (footprint "eagle-import:C0603")
      (libsource (lib "eagle-import") (part "C-EUC0603"))
    )
    (comp (ref "C63")
      (value "100n")
      (footprint "eagle-import:C0603")
      (libsource (lib "eagle-import") (part "C-EUC0603"))
    )
    (comp (ref "C64")
      (value "4u7")
      (footprint "eagle-import:C0805")
      (libsource (lib "eagle-import") (part "C-EUC0805"))
    )
    (comp (ref "C65")
      (value "100n")
      (footprint "eagle-import:C0603")
      (libsource (lib "eagle-import") (part "C-EUC0603"))
    )
    (comp (ref "C66")
      (value "1n")
      (footprint "eagle-import:C0805")
      (libsource (lib "eagle-import") (part "C-EUC0805"))
    )
    (comp (ref "C67")
      (value "100n")
      (footprint "eagle-import:C0603")
      (libsource (lib "eagle-import") (part "C-EUC0603"))
    )
    (comp (ref "C68")
      (value "100n")
      (footprint "eagle-import:C0603")
      (libsource (lib "eagle-import") (part "C-EUC0603"))
    )
    (comp (ref "C69")
      (value "100n")
      (footprint "eagle-import:C0603")
      (libsource (lib "eagle-import") (part "C-EUC0603"))
    )
    (comp (ref "C70")
      (value "100n")
      (footprint "eagle-import:C0603")
      (libsource (lib "eagle-import") (part "C-EUC0603"))
    )
    (comp (ref "C71")
      (value "100n")
      (footprint "eagle-import:C0603")
      (libsource (lib "eagle-import") (part "C-EUC0603"))
    )
    (comp (ref "C72")
      (value "1u")
      (footprint "eagle-import:C0805")
      (libsource (lib "eagle-import") (part "C-EUC0805"))
    )
    (comp (ref "C73")
      (value "1u")
      (footprint "eagle-import:C0805")
      (libsource (lib "eagle-import") (part "C-EUC0805"))
    )
    (comp (ref "D3")
      (value "BAT54SFILM")
      (footprint "eagle-import:SOT23")
      (libsource (lib "eagle-import") (part "BAT54S"))
    )
    (comp (ref "D4")
      (value "BAT54SFILM")
      (footprint "eagle-import:SOT23")
      (libsource (lib "eagle-import") (part "BAT54S"))
    )
    (comp (ref "D5")
      (value "BAT54SFILM")
      (footprint "eagle-import:SOT23")
      (libsource (lib "eagle-import") (part "BAT54S"))
    )
    (comp (ref "D6")
      (value "BAT54SFILM")
      (footprint "eagle-import:SOT23")
      (libsource (lib "eagle-import") (part "BAT54S"))
    )
    (comp (ref "IC12")
      (value "OPA376AIDBVR")
      (footprint "eagle-import:DBV5")
      (libsource (lib "eagle-import") (part "OPA376AIDBVR"))
    )
    (comp (ref "IC13")
      (value "DAC7563TDGSR")
      (footprint "eagle-import:DGS10")
      (libsource (lib "eagle-import") (part "DAC7563TDGSR"))
    )
    (comp (ref "IC14")
      (value "OPA2196IDR")
      (footprint "eagle-import:SOIC127P600X173-8N")
      (libsource (lib "eagle-import") (part "TL072SOIC8"))
    )
    (comp (ref "IC15")
      (value "BTS3408G")
      (footprint "eagle-import:SOIC127P600X173-8N")
      (libsource (lib "eagle-import") (part "BTS3408G"))
    )
    (comp (ref "IC16")
      (value "BTS3408G")
      (footprint "eagle-import:SOIC127P600X173-8N")
      (libsource (lib "eagle-import") (part "BTS3408G"))
    )
    (comp (ref "IC17")
      (value "BTS3408G")
      (footprint "eagle-import:SOIC127P600X173-8N")
      (libsource (lib "eagle-import") (part "BTS3408G"))
    )
    (comp (ref "IC18")
      (value "BTS3408G")
      (footprint "eagle-import:SOIC127P600X173-8N")
      (libsource (lib "eagle-import") (part "BTS3408G"))
    )
    (comp (ref "IC19")
      (value "74HC126PW,118")
      (footprint "eagle-import:PW14")
      (libsource (lib "eagle-import") (part "74HC126PW,118"))
    )
    (comp (ref "JP4")
      (value "DS1025-01-1*3P8BV1-B")
      (footprint "eagle-import:ZL303-03P")
      (libsource (lib "eagle-import") (part "JUMPER-3PIN2MM"))
    )
    (comp (ref "JP5")
      (value "DS1025-01-1*3P8BV1-B")
      (footprint "eagle-import:ZL303-03P")
      (libsource (lib "eagle-import") (part "JUMPER-3PIN2MM"))
    )
    (comp (ref "L7")
      (value "BLM18AG102SH1D")
      (footprint "eagle-import:BEAD0603")
      (libsource (lib "eagle-import") (part "FERRITE_BEAD0603"))
    )
    (comp (ref "R16")
      (value "9K09 0.1%")
      (footprint "eagle-import:R0805")
      (libsource (lib "eagle-import") (part "R-EU_R0805"))
    )
    (comp (ref "R17")
      (value "75K 0.1%")
      (footprint "eagle-import:R0805")
      (libsource (lib "eagle-import") (part "R-EU_R0805"))
    )
    (comp (ref "R18")
      (value "9K09 0.1%")
      (footprint "eagle-import:R0805")
      (libsource (lib "eagle-import") (part "R-EU_R0805"))
    )
    (comp (ref "R19")
      (value "180R")
      (footprint "eagle-import:R0805")
      (libsource (lib "eagle-import") (part "R-EU_R0805"))
    )
    (comp (ref "R20")
      (value "47R")
      (footprint "eagle-import:R0805")
      (libsource (lib "eagle-import") (part "R-EU_R0805"))
    )
    (comp (ref "R21")
      (value "9K09 0.1%")
      (footprint "eagle-import:R0805")
      (libsource (lib "eagle-import") (part "R-EU_R0805"))
    )
    (comp (ref "R22")
      (value "9K09 0.1%")
      (footprint "eagle-import:R0805")
      (libsource (lib "eagle-import") (part "R-EU_R0805"))
    )
    (comp (ref "R23")
      (value "75K 0.1%")
      (footprint "eagle-import:R0805")
      (libsource (lib "eagle-import") (part "R-EU_R0805"))
    )
    (comp (ref "R24")
      (value "9K09 0.1%")
      (footprint "eagle-import:R0805")
      (libsource (lib "eagle-import") (part "R-EU_R0805"))
    )
    (comp (ref "R25")
      (value "75K 0.1%")
      (footprint "eagle-import:R0805")
      (libsource (lib "eagle-import") (part "R-EU_R0805"))
    )
    (comp (ref "R26")
      (value "180R")
      (footprint "eagle-import:R0805")
      (libsource (lib "eagle-import") (part "R-EU_R0805"))
    )
    (comp (ref "R27")
      (value "47R")
      (footprint "eagle-import:R0805")
      (libsource (lib "eagle-import") (part "R-EU_R0805"))
    )
    (comp (ref "R28")
      (value "9K09 0.1%")
      (footprint "eagle-import:R0805")
      (libsource (lib "eagle-import") (part "R-EU_R0805"))
    )
    (comp (ref "R29")
      (value "75K 0.1%")
      (footprint "eagle-import:R0805")
      (libsource (lib "eagle-import") (part "R-EU_R0805"))
    )
    (comp (ref "R30")
      (value "10K")
      (footprint "eagle-import:R0805")
      (libsource (lib "eagle-import") (part "R-EU_R0805"))
    )
    (comp (ref "R31")
      (value "100R")
      (footprint "eagle-import:R0805")
      (libsource (lib "eagle-import") (part "R-EU_R0805"))
    )
    (comp (ref "R32")
      (value "100R")
      (footprint "eagle-import:R0805")
      (libsource (lib "eagle-import") (part "R-EU_R0805"))
    )
    (comp (ref "SH2")
      (value "SHORTNOHOLE")
      (footprint "eagle-import:SHORT_NOHOLE")
      (libsource (lib "eagle-import") (part "SHORTNOHOLE"))
    )
    (comp (ref "TVS3")
      (value "PESD12VL1BA,115")
      (footprint "eagle-import:SOD323-BIDIR")
      (libsource (lib "eagle-import") (part "PESDXL1BA"))
    )
    (comp (ref "TVS4")
      (value "PESD12VL1BA,115")
      (footprint "eagle-import:SOD323-BIDIR")
      (libsource (lib "eagle-import") (part "PESDXL1BA"))
    )
    (comp (ref "ZD1")
      (value "MMSZ4700T1G")
      (footprint "eagle-import:SOD123")
      (libsource (lib "eagle-import") (part "ZENER-DIODESOD123"))
    )
    (comp (ref "ZD2")
      (value "MMSZ4700T1G")
      (footprint "eagle-import:SOD123")
      (libsource (lib "eagle-import") (part "ZENER-DIODESOD123"))
    )
    (comp (ref "C86")
      (value "100n")
      (footprint "eagle-import:C0603")
      (libsource (lib "eagle-import") (part "C-EUC0603"))
    )
    (comp (ref "C87")
      (value "1u")
      (footprint "eagle-import:C0805")
      (libsource (lib "eagle-import") (part "C-EUC0805"))
    )
    (comp (ref "C88")
      (value "1u")
      (footprint "eagle-import:C0805")
      (libsource (lib "eagle-import") (part "C-EUC0805"))
    )
    (comp (ref "C89")
      (value "4n7/1kV")
      (footprint "eagle-import:C1812")
      (libsource (lib "eagle-import") (part "C-EUC1812"))
    )
    (comp (ref "C90")
      (value "1n")
      (footprint "eagle-import:C0805")
      (libsource (lib "eagle-import") (part "C-EUC0805"))
    )
    (comp (ref "C91")
      (value "1n")
      (footprint "eagle-import:C0805")
      (libsource (lib "eagle-import") (part "C-EUC0805"))
    )
    (comp (ref "C92")
      (value "10u")
      (footprint "eagle-import:C1206")
      (libsource (lib "eagle-import") (part "C-EUC1206"))
    )
    (comp (ref "C93")
      (value "1u")
      (footprint "eagle-import:C0805")
      (libsource (lib "eagle-import") (part "C-EUC0805"))
    )
    (comp (ref "C94")
      (value "22u")
      (footprint "eagle-import:C1206")
      (libsource (lib "eagle-import") (part "C-EUC1206"))
    )
    (comp (ref "C95")
      (value "10u")
      (footprint "eagle-import:C1206")
      (libsource (lib "eagle-import") (part "C-EUC1206"))
    )
    (comp (ref "C96")
      (value "10u")
      (footprint "eagle-import:C1206")
      (libsource (lib "eagle-import") (part "C-EUC1206"))
    )
    (comp (ref "C97")
      (value "1n")
      (footprint "eagle-import:C0805")
      (libsource (lib "eagle-import") (part "C-EUC0805"))
    )
    (comp (ref "C98")
      (value "1n")
      (footprint "eagle-import:C0805")
      (libsource (lib "eagle-import") (part "C-EUC0805"))
    )
    (comp (ref "IC21")
      (value "DG468DV-T1-E3")
      (footprint "eagle-import:DG6_TSOP6")
      (libsource (lib "eagle-import") (part "DG468DV-T1-E3"))
    )
    (comp (ref "IC22")
      (value "DG468DV-T1-E3")
      (footprint "eagle-import:DG6_TSOP6")
      (libsource (lib "eagle-import") (part "DG468DV-T1-E3"))
    )
    (comp (ref "IC23")
      (value "DG468DV-T1-E3")
      (footprint "eagle-import:DG6_TSOP6")
      (libsource (lib "eagle-import") (part "DG468DV-T1-E3"))
    )
    (comp (ref "IC24")
      (value "DG468DV-T1-E3")
      (footprint "eagle-import:DG6_TSOP6")
      (libsource (lib "eagle-import") (part "DG468DV-T1-E3"))
    )
    (comp (ref "IC25")
      (value "DG468DV-T1-E3")
      (footprint "eagle-import:DG6_TSOP6")
      (libsource (lib "eagle-import") (part "DG468DV-T1-E3"))
    )
    (comp (ref "IC26")
      (value "DG468DV-T1-E3")
      (footprint "eagle-import:DG6_TSOP6")
      (libsource (lib "eagle-import") (part "DG468DV-T1-E3"))
    )
    (comp (ref "IC27")
      (value "DG468DV-T1-E3")
      (footprint "eagle-import:DG6_TSOP6")
      (libsource (lib "eagle-import") (part "DG468DV-T1-E3"))
    )
    (comp (ref "IC28")
      (value "DG468DV-T1-E3")
      (footprint "eagle-import:DG6_TSOP6")
      (libsource (lib "eagle-import") (part "DG468DV-T1-E3"))
    )
    (comp (ref "IC29")
      (value "DG468DV-T1-E3")
      (footprint "eagle-import:DG6_TSOP6")
      (libsource (lib "eagle-import") (part "DG468DV-T1-E3"))
    )
    (comp (ref "IC30")
      (value "DG468DV-T1-E3")
      (footprint "eagle-import:DG6_TSOP6")
      (libsource (lib "eagle-import") (part "DG468DV-T1-E3"))
    )
    (comp (ref "IC31")
      (value "DG468DV-T1-E3")
      (footprint "eagle-import:DG6_TSOP6")
      (libsource (lib "eagle-import") (part "DG468DV-T1-E3"))
    )
    (comp (ref "IC32")
      (value "DG468DV-T1-E3")
      (footprint "eagle-import:DG6_TSOP6")
      (libsource (lib "eagle-import") (part "DG468DV-T1-E3"))
    )
    (comp (ref "IC33")
      (value "DG468DV-T1-E3")
      (footprint "eagle-import:DG6_TSOP6")
      (libsource (lib "eagle-import") (part "DG468DV-T1-E3"))
    )
    (comp (ref "IC34")
      (value "DG468DV-T1-E3")
      (footprint "eagle-import:DG6_TSOP6")
      (libsource (lib "eagle-import") (part "DG468DV-T1-E3"))
    )
    (comp (ref "IC35")
      (value "OPA376AIDBVR")
      (footprint "eagle-import:DBV5")
      (libsource (lib "eagle-import") (part "OPA376AIDBVR"))
    )
    (comp (ref "IC36")
      (value "ADS8674IDBT")
      (footprint "eagle-import:DBT38")
      (libsource (lib "eagle-import") (part "ADS8674IDBT"))
    )
    (comp (ref "JP6")
      (value "JP3-CUT-0805-ROTATED")
      (footprint "eagle-import:JP3-0805-CUT2")
      (libsource (lib "eagle-import") (part "JP3-CUT-0805-ROTATED"))
    )
    (comp (ref "JP7")
      (value "DS1025-01-1*2P8BV1-B")
      (footprint "eagle-import:2MM-2")
      (libsource (lib "eagle-import") (part "JUMPER-2PIN-2MM"))
    )
    (comp (ref "JP8")
      (value "DS1025-01-1*2P8BV1-B")
      (footprint "eagle-import:2MM-2")
      (libsource (lib "eagle-import") (part "JUMPER-2PIN-2MM"))
    )
    (comp (ref "JP9")
      (value "JP2-CUT-0805")
      (footprint "eagle-import:R_0805")
      (libsource (lib "eagle-import") (part "JP2-CUT-0805"))
    )
    (comp (ref "JP10")
      (value "DS1025-01-1*2P8BV1-B")
      (footprint "eagle-import:2MM-2")
      (libsource (lib "eagle-import") (part "JUMPER-2PIN-2MM"))
    )
    (comp (ref "JP11")
      (value "JP2-CUT-0805")
      (footprint "eagle-import:R_0805")
      (libsource (lib "eagle-import") (part "JP2-CUT-0805"))
    )
    (comp (ref "JP12")
      (value "DS1025-01-1*2P8BV1-B")
      (footprint "eagle-import:2MM-2")
      (libsource (lib "eagle-import") (part "JUMPER-2PIN-2MM"))
    )
    (comp (ref "L8")
      (value "BLM18AG102SH1D")
      (footprint "eagle-import:BEAD0603")
      (libsource (lib "eagle-import") (part "FERRITE_BEAD0603"))
    )
    (comp (ref "L9")
      (value "BLM18AG102SH1D")
      (footprint "eagle-import:BEAD0603")
      (libsource (lib "eagle-import") (part "FERRITE_BEAD0603"))
    )
    (comp (ref "L10")
      (value "BLM18AG102SH1D")
      (footprint "eagle-import:BEAD0603")
      (libsource (lib "eagle-import") (part "FERRITE_BEAD0603"))
    )
    (comp (ref "L11")
      (value "BLM18AG102SH1D")
      (footprint "eagle-import:BEAD0603")
      (libsource (lib "eagle-import") (part "FERRITE_BEAD0603"))
    )
    (comp (ref "L12")
      (value "BLM18AG102SH1D")
      (footprint "eagle-import:BEAD0603")
      (libsource (lib "eagle-import") (part "FERRITE_BEAD0603"))
    )
    (comp (ref "Q6")
      (value "BSS169")
      (footprint "eagle-import:SOT103P240X110-3N")
      (libsource (lib "eagle-import") (part "BSS169"))
    )
    (comp (ref "Q7")
      (value "BSS169")
      (footprint "eagle-import:SOT103P240X110-3N")
      (libsource (lib "eagle-import") (part "BSS169"))
    )
    (comp (ref "Q8")
      (value "BSS169")
      (footprint "eagle-import:SOT103P240X110-3N")
      (libsource (lib "eagle-import") (part "BSS169"))
    )
    (comp (ref "Q9")
      (value "BSS169")
      (footprint "eagle-import:SOT103P240X110-3N")
      (libsource (lib "eagle-import") (part "BSS169"))
    )
    (comp (ref "Q10")
      (value "BSS169")
      (footprint "eagle-import:SOT103P240X110-3N")
      (libsource (lib "eagle-import") (part "BSS169"))
    )
    (comp (ref "Q11")
      (value "BSS169")
      (footprint "eagle-import:SOT103P240X110-3N")
      (libsource (lib "eagle-import") (part "BSS169"))
    )
    (comp (ref "Q12")
      (value "BSS169")
      (footprint "eagle-import:SOT103P240X110-3N")
      (libsource (lib "eagle-import") (part "BSS169"))
    )
    (comp (ref "Q13")
      (value "BSS169")
      (footprint "eagle-import:SOT103P240X110-3N")
      (libsource (lib "eagle-import") (part "BSS169"))
    )
    (comp (ref "R60")
      (value "470K")
      (footprint "eagle-import:R1206")
      (libsource (lib "eagle-import") (part "R-EU_R1206"))
    )
    (comp (ref "R61")
      (value "470K")
      (footprint "eagle-import:R1206")
      (libsource (lib "eagle-import") (part "R-EU_R1206"))
    )
    (comp (ref "R62")
      (value "10K")
      (footprint "eagle-import:R0805")
      (libsource (lib "eagle-import") (part "R-EU_R0805"))
    )
    (comp (ref "R63")
      (value "10K")
      (footprint "eagle-import:R0805")
      (libsource (lib "eagle-import") (part "R-EU_R0805"))
    )
    (comp (ref "R64")
      (value "N.C.")
      (footprint "eagle-import:R0805")
      (libsource (lib "eagle-import") (part "R-EU_R0805"))
    )
    (comp (ref "R65")
      (value "N.C.")
      (footprint "eagle-import:R0805")
      (libsource (lib "eagle-import") (part "R-EU_R0805"))
    )
    (comp (ref "R66")
      (value "47R")
      (footprint "eagle-import:R0805")
      (libsource (lib "eagle-import") (part "R-EU_R0805"))
    )
    (comp (ref "R67")
      (value "100R")
      (footprint "eagle-import:R0805")
      (libsource (lib "eagle-import") (part "R-EU_R0805"))
    )
    (comp (ref "R68")
      (value "N.C.")
      (footprint "eagle-import:R0805")
      (libsource (lib "eagle-import") (part "R-EU_R0805"))
    )
    (comp (ref "R69")
      (value "N.C.")
      (footprint "eagle-import:R0805")
      (libsource (lib "eagle-import") (part "R-EU_R0805"))
    )
    (comp (ref "R70")
      (value "100R")
      (footprint "eagle-import:R0805")
      (libsource (lib "eagle-import") (part "R-EU_R0805"))
    )
    (comp (ref "R71")
      (value "154R")
      (footprint "eagle-import:R0805")
      (libsource (lib "eagle-import") (part "R-EU_R0805"))
    )
    (comp (ref "R72")
      (value "47R")
      (footprint "eagle-import:R0805")
      (libsource (lib "eagle-import") (part "R-EU_R0805"))
    )
    (comp (ref "R73")
      (value "100R")
      (footprint "eagle-import:R0805")
      (libsource (lib "eagle-import") (part "R-EU_R0805"))
    )
    (comp (ref "R74")
      (value "100R")
      (footprint "eagle-import:R0805")
      (libsource (lib "eagle-import") (part "R-EU_R0805"))
    )
    (comp (ref "R75")
      (value "154R")
      (footprint "eagle-import:R0805")
      (libsource (lib "eagle-import") (part "R-EU_R0805"))
    )
    (comp (ref "R76")
      (value "47R")
      (footprint "eagle-import:R0805")
      (libsource (lib "eagle-import") (part "R-EU_R0805"))
    )
    (comp (ref "R77")
      (value "100R")
      (footprint "eagle-import:R0805")
      (libsource (lib "eagle-import") (part "R-EU_R0805"))
    )
    (comp (ref "R78")
      (value "100R")
      (footprint "eagle-import:R0805")
      (libsource (lib "eagle-import") (part "R-EU_R0805"))
    )
    (comp (ref "R79")
      (value "154R")
      (footprint "eagle-import:R0805")
      (libsource (lib "eagle-import") (part "R-EU_R0805"))
    )
    (comp (ref "R80")
      (value "47R")
      (footprint "eagle-import:R0805")
      (libsource (lib "eagle-import") (part "R-EU_R0805"))
    )
    (comp (ref "R81")
      (value "100R")
      (footprint "eagle-import:R0805")
      (libsource (lib "eagle-import") (part "R-EU_R0805"))
    )
    (comp (ref "R82")
      (value "100R")
      (footprint "eagle-import:R0805")
      (libsource (lib "eagle-import") (part "R-EU_R0805"))
    )
    (comp (ref "R83")
      (value "154R")
      (footprint "eagle-import:R0805")
      (libsource (lib "eagle-import") (part "R-EU_R0805"))
    )
    (comp (ref "TVS5")
      (value "PESD12VL1BA,115")
      (footprint "eagle-import:SOD323-BIDIR")
      (libsource (lib "eagle-import") (part "PESDXL1BA"))
    )
    (comp (ref "TVS6")
      (value "PESD12VL1BA,115")
      (footprint "eagle-import:SOD323-BIDIR")
      (libsource (lib "eagle-import") (part "PESDXL1BA"))
    )
    (comp (ref "TVS7")
      (value "PESD12VL1BA,115")
      (footprint "eagle-import:SOD323-BIDIR")
      (libsource (lib "eagle-import") (part "PESDXL1BA"))
    )
    (comp (ref "TVS8")
      (value "PESD12VL1BA,115")
      (footprint "eagle-import:SOD323-BIDIR")
      (libsource (lib "eagle-import") (part "PESDXL1BA"))
    )
    (comp (ref "X5")
      (value "1-2314878-0")
      (footprint "eagle-import:1-2314878-0")
      (libsource (lib "eagle-import") (part "1-2314878-0"))
    )
    (comp (ref "X6")
      (value "1-2314878-0")
      (footprint "eagle-import:1-2314878-0")
      (libsource (lib "eagle-import") (part "1-2314878-0"))
    )
    (comp (ref "X7")
      (value "1-2314878-0")
      (footprint "eagle-import:1-2314878-0")
      (libsource (lib "eagle-import") (part "1-2314878-0"))
    )
    (comp (ref "C19")
      (value "N.C.")
      (footprint "eagle-import:C0805")
      (libsource (lib "eagle-import") (part "C-EUC0805"))
    )
    (comp (ref "C20")
      (value "18p")
      (footprint "eagle-import:C0603")
      (libsource (lib "eagle-import") (part "C-EUC0603"))
    )
    (comp (ref "C21")
      (value "18p")
      (footprint "eagle-import:C0603")
      (libsource (lib "eagle-import") (part "C-EUC0603"))
    )
    (comp (ref "C23")
      (value "4u7")
      (footprint "eagle-import:EC1206")
      (libsource (lib "eagle-import") (part "ECAP1206"))
    )
    (comp (ref "C24")
      (value "100n")
      (footprint "eagle-import:C0603")
      (libsource (lib "eagle-import") (part "C-EUC0603"))
    )
    (comp (ref "C25")
      (value "100n")
      (footprint "eagle-import:C0603")
      (libsource (lib "eagle-import") (part "C-EUC0603"))
    )
    (comp (ref "C26")
      (value "100n")
      (footprint "eagle-import:C0603")
      (libsource (lib "eagle-import") (part "C-EUC0603"))
    )
    (comp (ref "C27")
      (value "100n")
      (footprint "eagle-import:C0603")
      (libsource (lib "eagle-import") (part "C-EUC0603"))
    )
    (comp (ref "C28")
      (value "100n")
      (footprint "eagle-import:C0603")
      (libsource (lib "eagle-import") (part "C-EUC0603"))
    )
    (comp (ref "C29")
      (value "100n")
      (footprint "eagle-import:C0603")
      (libsource (lib "eagle-import") (part "C-EUC0603"))
    )
    (comp (ref "C30")
      (value "100n")
      (footprint "eagle-import:C0603")
      (libsource (lib "eagle-import") (part "C-EUC0603"))
    )
    (comp (ref "C31")
      (value "100n")
      (footprint "eagle-import:C0603")
      (libsource (lib "eagle-import") (part "C-EUC0603"))
    )
    (comp (ref "C32")
      (value "100n")
      (footprint "eagle-import:C0603")
      (libsource (lib "eagle-import") (part "C-EUC0603"))
    )
    (comp (ref "C33")
      (value "100n")
      (footprint "eagle-import:C0603")
      (libsource (lib "eagle-import") (part "C-EUC0603"))
    )
    (comp (ref "C34")
      (value "100n")
      (footprint "eagle-import:C0603")
      (libsource (lib "eagle-import") (part "C-EUC0603"))
    )
    (comp (ref "C35")
      (value "1u")
      (footprint "eagle-import:C0805")
      (libsource (lib "eagle-import") (part "C-EUC0805"))
    )
    (comp (ref "C36")
      (value "100n")
      (footprint "eagle-import:C0603")
      (libsource (lib "eagle-import") (part "C-EUC0603"))
    )
    (comp (ref "C37")
      (value "2u2")
      (footprint "eagle-import:C0805")
      (libsource (lib "eagle-import") (part "C-EUC0805"))
    )
    (comp (ref "C38")
      (value "2u2")
      (footprint "eagle-import:C0805")
      (libsource (lib "eagle-import") (part "C-EUC0805"))
    )
    (comp (ref "IC8")
      (value "STM32F446ZCT6")
      (footprint "eagle-import:LQFP-144")
      (libsource (lib "eagle-import") (part "STM32F446ZCT6"))
    )
    (comp (ref "J2")
      (value "N.C.")
      (footprint "eagle-import:5033981892")
      (libsource (lib "eagle-import") (part "5033981892"))
    )
    (comp (ref "L4")
      (value "BLM18AG102SH1D")
      (footprint "eagle-import:BEAD0603")
      (libsource (lib "eagle-import") (part "FERRITE_BEAD0603"))
    )
    (comp (ref "R1")
      (value "N.C.")
      (footprint "eagle-import:R0805")
      (libsource (lib "eagle-import") (part "R-EU_R0805"))
    )
    (comp (ref "R2")
      (value "N.C.")
      (footprint "eagle-import:R0805")
      (libsource (lib "eagle-import") (part "R-EU_R0805"))
    )
    (comp (ref "R3")
      (value "N.C.")
      (footprint "eagle-import:R0805")
      (libsource (lib "eagle-import") (part "R-EU_R0805"))
    )
    (comp (ref "R4")
      (value "N.C.")
      (footprint "eagle-import:R0805")
      (libsource (lib "eagle-import") (part "R-EU_R0805"))
    )
    (comp (ref "R5")
      (value "N.C.")
      (footprint "eagle-import:R0805")
      (libsource (lib "eagle-import") (part "R-EU_R0805"))
    )
    (comp (ref "R6")
      (value "4K7")
      (footprint "eagle-import:R0805")
      (libsource (lib "eagle-import") (part "R-EU_R0805"))
    )
    (comp (ref "R7")
      (value "10K")
      (footprint "eagle-import:R0805")
      (libsource (lib "eagle-import") (part "R-EU_R0805"))
    )
    (comp (ref "R8")
      (value "47R")
      (footprint "eagle-import:R0805")
      (libsource (lib "eagle-import") (part "R-EU_R0805"))
    )
    (comp (ref "RN4")
      (value "DR1206-33R-4/8")
      (footprint "eagle-import:CAY16")
      (libsource (lib "eagle-import") (part "R_ARRAY4"))
    )
    (comp (ref "RN5")
      (value "DR1206-33R-4/8")
      (footprint "eagle-import:CAY16")
      (libsource (lib "eagle-import") (part "R_ARRAY4"))
    )
    (comp (ref "X2")
      (value "SSW-106-02-S-S")
      (footprint "eagle-import:SSW-106-02-S-S")
      (libsource (lib "eagle-import") (part "SSW-106-02-S-S"))
    )
    (comp (ref "Y1")
      (value "25MHz")
      (footprint "eagle-import:HC-49_4H")
      (libsource (lib "eagle-import") (part "XTALSMD"))
    )
  )
  (nets
    (net (code "1") (name "+3V3") (class "Default")
      (node (ref "C1") (pin "2") (pinfunction "2_2") (pintype "passive"))
      (node (ref "C2") (pin "1") (pinfunction "1_1") (pintype "passive"))
      (node (ref "C4") (pin "1") (pinfunction "1_1") (pintype "passive"))
      (node (ref "IC1") (pin "8") (pinfunction "VCC_8") (pintype "power_in"))
      (node (ref "IC2") (pin "1") (pinfunction "VDD1_1") (pintype "passive"))
      (node (ref "IC2") (pin "7") (pinfunction "EN1_7") (pintype "input"))
      (node (ref "IC3") (pin "1") (pinfunction "VDD1_1") (pintype "passive"))
      (node (ref "IC3") (pin "7") (pinfunction "EN1_7") (pintype "input"))
      (node (ref "RN3") (pin "6") (pinfunction "2_6") (pintype "passive"))
      (node (ref "RN3") (pin "7") (pinfunction "2_7") (pintype "passive"))
      (node (ref "RN3") (pin "8") (pinfunction "2_8") (pintype "passive"))
      (node (ref "X1") (pin "1") (pinfunction "1_1") (pintype "passive"))
    )
    (net (code "2") (name "+3V3_ISO") (class "Default")
      (node (ref "C14") (pin "1") (pinfunction "1_1") (pintype "passive"))
      (node (ref "C19") (pin "1") (pinfunction "1_1") (pintype "passive"))
      (node (ref "C23") (pin "+") (pinfunction "+_+") (pintype "passive"))
      (node (ref "C24") (pin "1") (pinfunction "1_1") (pintype "passive"))
      (node (ref "C25") (pin "1") (pinfunction "1_1") (pintype "passive"))
      (node (ref "C26") (pin "1") (pinfunction "1_1") (pintype "passive"))
      (node (ref "C27") (pin "1") (pinfunction "1_1") (pintype "passive"))
      (node (ref "C28") (pin "1") (pinfunction "1_1") (pintype "passive"))
      (node (ref "C29") (pin "1") (pinfunction "1_1") (pintype "passive"))
      (node (ref "C3") (pin "2") (pinfunction "2_2") (pintype "passive"))
      (node (ref "C30") (pin "1") (pinfunction "1_1") (pintype "passive"))
      (node (ref "C31") (pin "1") (pinfunction "1_1") (pintype "passive"))
      (node (ref "C32") (pin "1") (pinfunction "1_1") (pintype "passive"))
      (node (ref "C33") (pin "1") (pinfunction "1_1") (pintype "passive"))
      (node (ref "C34") (pin "1") (pinfunction "1_1") (pintype "passive"))
      (node (ref "C41") (pin "1") (pinfunction "1_1") (pintype "passive"))
      (node (ref "C5") (pin "2") (pinfunction "2_2") (pintype "passive"))
      (node (ref "C50") (pin "1") (pinfunction "1_1") (pintype "passive"))
      (node (ref "C71") (pin "2") (pinfunction "2_2") (pintype "passive"))
      (node (ref "C96") (pin "2") (pinfunction "2_2") (pintype "passive"))
      (node (ref "D5") (pin "2") (pinfunction "C2_2") (pintype "passive"))
      (node (ref "D6") (pin "2") (pinfunction "C2_2") (pintype "passive"))
      (node (ref "IC10") (pin "2") (pinfunction "DVDD_2") (pintype "power_in"))
      (node (ref "IC11") (pin "2") (pinfunction "DVDD_2") (pintype "power_in"))
      (node (ref "IC19") (pin "14") (pinfunction "V+_14") (pintype "power_in"))
      (node (ref "IC2") (pin "10") (pinfunction "EN2_10") (pintype "input"))
      (node (ref "IC2") (pin "16") (pinfunction "VDD2_16") (pintype "passive"))
      (node (ref "IC3") (pin "10") (pinfunction "EN2_10") (pintype "input"))
      (node (ref "IC3") (pin "16") (pinfunction "VDD2_16") (pintype "passive"))
      (node (ref "IC36") (pin "34") (pinfunction "DVDD_34") (pintype "power_in"))
      (node (ref "IC6") (pin "5") (pinfunction "OUT_5") (pintype "passive"))
      (node (ref "IC8") (pin "108") (pinfunction "VDD_9_108") (pintype "power_in"))
      (node (ref "IC8") (pin "121") (pinfunction "VDD_10_121") (pintype "power_in"))
      (node (ref "IC8") (pin "131") (pinfunction "VDD_11_131") (pintype "power_in"))
      (node (ref "IC8") (pin "143") (pinfunction "PDR_ON_143") (pintype "input"))
      (node (ref "IC8") (pin "144") (pinfunction "VDD_144") (pintype "power_in"))
      (node (ref "IC8") (pin "17") (pinfunction "VDD_2_17") (pintype "bidirectional"))
      (node (ref "IC8") (pin "30") (pinfunction "VDD_3_30") (pintype "power_in"))
      (node (ref "IC8") (pin "39") (pinfunction "VDD_4_39") (pintype "power_in"))
      (node (ref "IC8") (pin "52") (pinfunction "VDD_5_52") (pintype "power_in"))
      (node (ref "IC8") (pin "6") (pinfunction "VBAT_6") (pintype "power_in"))
      (node (ref "IC8") (pin "62") (pinfunction "VDD_6_62") (pintype "power_in"))
      (node (ref "IC8") (pin "72") (pinfunction "VDD_7_72") (pintype "power_in"))
      (node (ref "IC8") (pin "84") (pinfunction "VDD_8_84") (pintype "power_in"))
      (node (ref "IC8") (pin "95") (pinfunction "VDDUSB_95") (pintype "power_in"))
      (node (ref "J2") (pin "4") (pinfunction "VDD_4") (pintype "power_in"))
      (node (ref "L4") (pin "P$1") (pinfunction "1_P$1") (pintype "passive"))
      (node (ref "L7") (pin "P$2") (pinfunction "2_P$2") (pintype "passive"))
      (node (ref "R1") (pin "1") (pinfunction "1_1") (pintype "passive"))
      (node (ref "R12") (pin "1") (pinfunction "1_1") (pintype "passive"))
      (node (ref "R2") (pin "1") (pinfunction "1_1") (pintype "passive"))
      (node (ref "R3") (pin "1") (pinfunction "1_1") (pintype "passive"))
      (node (ref "R30") (pin "1") (pinfunction "1_1") (pintype "passive"))
      (node (ref "R33") (pin "1") (pinfunction "1_1") (pintype "passive"))
      (node (ref "R4") (pin "1") (pinfunction "1_1") (pintype "passive"))
      (node (ref "R5") (pin "1") (pinfunction "1_1") (pintype "passive"))
      (node (ref "R6") (pin "1") (pinfunction "1_1") (pintype "passive"))
      (node (ref "X5") (pin "10") (pinfunction "1_10") (pintype "passive"))
    )
    (net (code "3") (name "+5V_ISO") (class "Default")
      (node (ref "C16") (pin "2") (pinfunction "2_2") (pintype "passive"))
      (node (ref "IC5") (pin "2") (pinfunction "OUT_2") (pintype "output"))
      (node (ref "IC5") (pin "4") (pinfunction "VOUT_4") (pintype "output"))
      (node (ref "IC6") (pin "1") (pinfunction "IN_1") (pintype "input"))
      (node (ref "IC6") (pin "3") (pinfunction "ON/~{OFF}_3") (pintype "input"))
      (node (ref "L11") (pin "P$1") (pinfunction "1_P$1") (pintype "passive"))
      (node (ref "X5") (pin "2") (pinfunction "1_2") (pintype "passive"))
    )
    (net (code "4") (name "+12V") (class "Default")
      (node (ref "C7") (pin "2") (pinfunction "2_2") (pintype "passive"))
      (node (ref "L1") (pin "4") (pinfunction "4_4") (pintype "passive"))
      (node (ref "X1") (pin "21") (pinfunction "1_21") (pintype "passive"))
      (node (ref "X1") (pin "22") (pinfunction "1_22") (pintype "passive"))
    )
    (net (code "5") (name "+12V_ISO") (class "Default")
      (node (ref "C10") (pin "1") (pinfunction "1_1") (pintype "passive"))
      (node (ref "C45") (pin "1") (pinfunction "1_1") (pintype "passive"))
      (node (ref "C47") (pin "2") (pinfunction "2_2") (pintype "passive"))
      (node (ref "C53") (pin "1") (pinfunction "1_1") (pintype "passive"))
      (node (ref "C55") (pin "1") (pinfunction "1_1") (pintype "passive"))
      (node (ref "C58") (pin "2") (pinfunction "2_2") (pintype "passive"))
      (node (ref "C59") (pin "1") (pinfunction "1_1") (pintype "passive"))
      (node (ref "C67") (pin "2") (pinfunction "2_2") (pintype "passive"))
      (node (ref "C68") (pin "2") (pinfunction "2_2") (pintype "passive"))
      (node (ref "C69") (pin "2") (pinfunction "2_2") (pintype "passive"))
      (node (ref "C70") (pin "2") (pinfunction "2_2") (pintype "passive"))
      (node (ref "C72") (pin "1") (pinfunction "1_1") (pintype "passive"))
      (node (ref "D1") (pin "2") (pinfunction "C2_2") (pintype "passive"))
      (node (ref "D2") (pin "2") (pinfunction "C2_2") (pintype "passive"))
      (node (ref "D3") (pin "2") (pinfunction "C2_2") (pintype "passive"))
      (node (ref "D4") (pin "2") (pinfunction "C2_2") (pintype "passive"))
      (node (ref "IC10") (pin "24") (pinfunction "AVDD_24") (pintype "power_in"))
      (node (ref "IC11") (pin "24") (pinfunction "AVDD_24") (pintype "power_in"))
      (node (ref "IC14") (pin "8") (pinfunction "V+_8") (pintype "power_in"))
      (node (ref "IC15") (pin "8") (pinfunction "VSS_8") (pintype "passive"))
      (node (ref "IC16") (pin "8") (pinfunction "VSS_8") (pintype "passive"))
      (node (ref "IC17") (pin "8") (pinfunction "VSS_8") (pintype "passive"))
      (node (ref "IC18") (pin "8") (pinfunction "VSS_8") (pintype "passive"))
      (node (ref "IC4") (pin "1") (pinfunction "VO_1") (pintype "passive"))
      (node (ref "IC5") (pin "3") (pinfunction "IN_3") (pintype "input"))
      (node (ref "IC9") (pin "8") (pinfunction "V+_8") (pintype "power_in"))
      (node (ref "JP2") (pin "2") (pinfunction "2_2") (pintype "passive"))
      (node (ref "JP4") (pin "3") (pinfunction "3_3") (pintype "passive"))
      (node (ref "ZD1") (pin "C") (pinfunction "C_C") (pintype "passive"))
    )
    (net (code "6") (name "+15V_ISO") (class "Default")
      (node (ref "C11") (pin "2") (pinfunction "2_2") (pintype "passive"))
      (node (ref "C87") (pin "1") (pinfunction "1_1") (pintype "passive"))
      (node (ref "IC21") (pin "5") (pinfunction "V+_5") (pintype "passive"))
      (node (ref "IC22") (pin "5") (pinfunction "V+_5") (pintype "passive"))
      (node (ref "IC23") (pin "5") (pinfunction "V+_5") (pintype "passive"))
      (node (ref "IC24") (pin "5") (pinfunction "V+_5") (pintype "passive"))
      (node (ref "IC25") (pin "5") (pinfunction "V+_5") (pintype "passive"))
      (node (ref "IC26") (pin "5") (pinfunction "V+_5") (pintype "passive"))
      (node (ref "IC27") (pin "5") (pinfunction "V+_5") (pintype "passive"))
      (node (ref "IC28") (pin "5") (pinfunction "V+_5") (pintype "passive"))
      (node (ref "IC29") (pin "5") (pinfunction "V+_5") (pintype "passive"))
      (node (ref "IC30") (pin "5") (pinfunction "V+_5") (pintype "passive"))
      (node (ref "IC31") (pin "5") (pinfunction "V+_5") (pintype "passive"))
      (node (ref "IC32") (pin "5") (pinfunction "V+_5") (pintype "passive"))
      (node (ref "IC33") (pin "5") (pinfunction "V+_5") (pintype "passive"))
      (node (ref "IC34") (pin "5") (pinfunction "V+_5") (pintype "passive"))
      (node (ref "IC4") (pin "8") (pinfunction "VI_8") (pintype "input"))
      (node (ref "JP2") (pin "1") (pinfunction "1_1") (pintype "passive"))
      (node (ref "L2") (pin "2") (pinfunction "2_2") (pintype "passive"))
    )
    (net (code "7") (name "-12V_ISO") (class "Default")
      (node (ref "C13") (pin "2") (pinfunction "2_2") (pintype "passive"))
      (node (ref "C44") (pin "1") (pinfunction "1_1") (pintype "passive"))
      (node (ref "C46") (pin "2") (pinfunction "2_2") (pintype "passive"))
      (node (ref "C54") (pin "1") (pinfunction "1_1") (pintype "passive"))
      (node (ref "C56") (pin "1") (pinfunction "1_1") (pintype "passive"))
      (node (ref "C57") (pin "2") (pinfunction "2_2") (pintype "passive"))
      (node (ref "C62") (pin "1") (pinfunction "1_1") (pintype "passive"))
      (node (ref "C73") (pin "1") (pinfunction "1_1") (pintype "passive"))
      (node (ref "D1") (pin "1") (pinfunction "A1_1") (pintype "passive"))
      (node (ref "D2") (pin "1") (pinfunction "A1_1") (pintype "passive"))
      (node (ref "D3") (pin "1") (pinfunction "A1_1") (pintype "passive"))
      (node (ref "D4") (pin "1") (pinfunction "A1_1") (pintype "passive"))
      (node (ref "IC10") (pin "1") (pinfunction "AVSS_1") (pintype "power_in"))
      (node (ref "IC10") (pin "25") (pinfunction "EPAD_25") (pintype "passive"))
      (node (ref "IC11") (pin "1") (pinfunction "AVSS_1") (pintype "power_in"))
      (node (ref "IC11") (pin "25") (pinfunction "EPAD_25") (pintype "passive"))
      (node (ref "IC14") (pin "4") (pinfunction "V-_4") (pintype "power_in"))
      (node (ref "IC7") (pin "1") (pinfunction "OUT_1") (pintype "passive"))
      (node (ref "IC9") (pin "4") (pinfunction "V-_4") (pintype "power_in"))
      (node (ref "JP3") (pin "2") (pinfunction "2_2") (pintype "passive"))
      (node (ref "JP5") (pin "3") (pinfunction "3_3") (pintype "passive"))
      (node (ref "R64") (pin "1") (pinfunction "1_1") (pintype "passive"))
      (node (ref "R65") (pin "1") (pinfunction "1_1") (pintype "passive"))
      (node (ref "R68") (pin "1") (pinfunction "1_1") (pintype "passive"))
      (node (ref "R69") (pin "1") (pinfunction "1_1") (pintype "passive"))
      (node (ref "ZD2") (pin "C") (pinfunction "C_C") (pintype "passive"))
    )
    (net (code "8") (name "-15V_ISO") (class "Default")
      (node (ref "C15") (pin "1") (pinfunction "1_1") (pintype "passive"))
      (node (ref "C88") (pin "1") (pinfunction "1_1") (pintype "passive"))
      (node (ref "IC21") (pin "2") (pinfunction "V-_2") (pintype "passive"))
      (node (ref "IC22") (pin "2") (pinfunction "V-_2") (pintype "passive"))
      (node (ref "IC23") (pin "2") (pinfunction "V-_2") (pintype "passive"))
      (node (ref "IC24") (pin "2") (pinfunction "V-_2") (pintype "passive"))
      (node (ref "IC25") (pin "2") (pinfunction "V-_2") (pintype "passive"))
      (node (ref "IC26") (pin "2") (pinfunction "V-_2") (pintype "passive"))
      (node (ref "IC27") (pin "2") (pinfunction "V-_2") (pintype "passive"))
      (node (ref "IC28") (pin "2") (pinfunction "V-_2") (pintype "passive"))
      (node (ref "IC29") (pin "2") (pinfunction "V-_2") (pintype "passive"))
      (node (ref "IC30") (pin "2") (pinfunction "V-_2") (pintype "passive"))
      (node (ref "IC31") (pin "2") (pinfunction "V-_2") (pintype "passive"))
      (node (ref "IC32") (pin "2") (pinfunction "V-_2") (pintype "passive"))
      (node (ref "IC33") (pin "2") (pinfunction "V-_2") (pintype "passive"))
      (node (ref "IC34") (pin "2") (pinfunction "V-_2") (pintype "passive"))
      (node (ref "IC7") (pin "2") (pinfunction "IN_2") (pintype "input"))
      (node (ref "IC7") (pin "3") (pinfunction "IN_3") (pintype "input"))
      (node (ref "IC7") (pin "6") (pinfunction "IN_6") (pintype "input"))
      (node (ref "IC7") (pin "7") (pinfunction "IN_7") (pintype "input"))
      (node (ref "JP3") (pin "1") (pinfunction "1_1") (pintype "passive"))
      (node (ref "L3") (pin "3") (pinfunction "3_3") (pintype "passive"))
    )
    (net (code "18") (name "1V25_REF") (class "Default")
      (node (ref "IC12") (pin "1") (pinfunction "OUT_1") (pintype "output"))
      (node (ref "IC12") (pin "4") (pinfunction "-IN_4") (pintype "input"))
      (node (ref "JP6") (pin "NO") (pinfunction "NO_NO") (pintype "passive"))
      (node (ref "R16") (pin "2") (pinfunction "2_2") (pintype "passive"))
      (node (ref "R24") (pin "2") (pinfunction "2_2") (pintype "passive"))
    )
    (net (code "19") (name "ADC_AVDD") (class "Default")
      (node (ref "C86") (pin "1") (pinfunction "1_1") (pintype "passive"))
      (node (ref "C95") (pin "2") (pinfunction "2_2") (pintype "passive"))
      (node (ref "IC35") (pin "5") (pinfunction "V+_5") (pintype "power_in"))
      (node (ref "IC36") (pin "30") (pinfunction "AVDD_30") (pintype "power_in"))
      (node (ref "IC36") (pin "9") (pinfunction "AVDD_9") (pintype "power_in"))
      (node (ref "L11") (pin "P$2") (pinfunction "2_P$2") (pintype "passive"))
      (node (ref "X5") (pin "3") (pinfunction "1_3") (pintype "passive"))
    )
    (net (code "20") (name "ADC_IRQ") (class "Default")
      (node (ref "IC36") (pin "35") (pinfunction "ALARM_35") (pintype "output"))
      (node (ref "IC8") (pin "77") (pinfunction "PD8_77") (pintype "bidirectional"))
      (node (ref "X5") (pin "9") (pinfunction "1_9") (pintype "passive"))
    )
    (net (code "21") (name "ADC_MISO") (class "Default")
      (node (ref "IC36") (pin "36") (pinfunction "SDO_36") (pintype "output"))
      (node (ref "RN5") (pin "3") (pinfunction "1_3") (pintype "passive"))
      (node (ref "X5") (pin "8") (pinfunction "1_8") (pintype "passive"))
    )
    (net (code "22") (name "ADC_MOSI") (class "Default")
      (node (ref "IC36") (pin "1") (pinfunction "SDI_1") (pintype "input"))
      (node (ref "RN5") (pin "4") (pinfunction "1_4") (pintype "passive"))
      (node (ref "X5") (pin "5") (pinfunction "1_5") (pintype "passive"))
    )
    (net (code "23") (name "ADC_SCLK") (class "Default")
      (node (ref "IC36") (pin "37") (pinfunction "SCLK_37") (pintype "input"))
      (node (ref "RN5") (pin "2") (pinfunction "1_2") (pintype "passive"))
      (node (ref "X5") (pin "7") (pinfunction "1_7") (pintype "passive"))
    )
    (net (code "24") (name "ADC_VREF") (class "Default")
      (node (ref "C92") (pin "2") (pinfunction "2_2") (pintype "passive"))
      (node (ref "IC35") (pin "3") (pinfunction "+IN_3") (pintype "input"))
      (node (ref "IC36") (pin "5") (pinfunction "REFIO_5") (pintype "bidirectional"))
      (node (ref "X7") (pin "2") (pinfunction "1_2") (pintype "passive"))
    )
    (net (code "25") (name "AIN_0GND") (class "Default")
      (node (ref "C90") (pin "1") (pinfunction "1_1") (pintype "passive"))
      (node (ref "IC36") (pin "17") (pinfunction "AIN_0GND_17") (pintype "input"))
      (node (ref "R71") (pin "2") (pinfunction "2_2") (pintype "passive"))
      (node (ref "X7") (pin "4") (pinfunction "1_4") (pintype "passive"))
    )
    (net (code "26") (name "AIN_0P") (class "Default")
      (node (ref "C90") (pin "2") (pinfunction "2_2") (pintype "passive"))
      (node (ref "IC36") (pin "16") (pinfunction "AIN_0P_16") (pintype "input"))
      (node (ref "R64") (pin "2") (pinfunction "2_2") (pintype "passive"))
      (node (ref "R67") (pin "2") (pinfunction "2_2") (pintype "passive"))
      (node (ref "X7") (pin "3") (pinfunction "1_3") (pintype "passive"))
    )
    (net (code "27") (name "AIN_1GND") (class "Default")
      (node (ref "C91") (pin "1") (pinfunction "1_1") (pintype "passive"))
      (node (ref "IC36") (pin "19") (pinfunction "AIN_1GND_19") (pintype "input"))
      (node (ref "R75") (pin "2") (pinfunction "2_2") (pintype "passive"))
      (node (ref "X7") (pin "6") (pinfunction "1_6") (pintype "passive"))
    )
    (net (code "28") (name "AIN_1P") (class "Default")
      (node (ref "C91") (pin "2") (pinfunction "2_2") (pintype "passive"))
      (node (ref "IC36") (pin "18") (pinfunction "AIN_1P_18") (pintype "input"))
      (node (ref "R65") (pin "2") (pinfunction "2_2") (pintype "passive"))
      (node (ref "R73") (pin "2") (pinfunction "2_2") (pintype "passive"))
      (node (ref "X7") (pin "5") (pinfunction "1_5") (pintype "passive"))
    )
    (net (code "29") (name "AIN_2GND") (class "Default")
      (node (ref "C97") (pin "1") (pinfunction "1_1") (pintype "passive"))
      (node (ref "IC36") (pin "20") (pinfunction "AIN_2GND_20") (pintype "input"))
      (node (ref "R79") (pin "2") (pinfunction "2_2") (pintype "passive"))
      (node (ref "X7") (pin "8") (pinfunction "1_8") (pintype "passive"))
    )
    (net (code "30") (name "AIN_2P") (class "Default")
      (node (ref "C97") (pin "2") (pinfunction "2_2") (pintype "passive"))
      (node (ref "IC36") (pin "21") (pinfunction "AIN_2P_21") (pintype "input"))
      (node (ref "R68") (pin "2") (pinfunction "2_2") (pintype "passive"))
      (node (ref "R77") (pin "2") (pinfunction "2_2") (pintype "passive"))
      (node (ref "X7") (pin "7") (pinfunction "1_7") (pintype "passive"))
    )
    (net (code "31") (name "AIN_3GND") (class "Default")
      (node (ref "C98") (pin "1") (pinfunction "1_1") (pintype "passive"))
      (node (ref "IC36") (pin "22") (pinfunction "AIN_3GND_22") (pintype "input"))
      (node (ref "R83") (pin "2") (pinfunction "2_2") (pintype "passive"))
      (node (ref "X7") (pin "10") (pinfunction "1_10") (pintype "passive"))
    )
    (net (code "32") (name "AIN_3P") (class "Default")
      (node (ref "C98") (pin "2") (pinfunction "2_2") (pintype "passive"))
      (node (ref "IC36") (pin "23") (pinfunction "AIN_3P_23") (pintype "input"))
      (node (ref "R69") (pin "2") (pinfunction "2_2") (pintype "passive"))
      (node (ref "R81") (pin "2") (pinfunction "2_2") (pintype "passive"))
      (node (ref "X7") (pin "9") (pinfunction "1_9") (pintype "passive"))
    )
    (net (code "33") (name "BOOT0") (class "Default")
      (node (ref "IC3") (pin "13") (pinfunction "B2_13") (pintype "output"))
      (node (ref "IC8") (pin "138") (pinfunction "BOOT0_138") (pintype "input"))
      (node (ref "R7") (pin "2") (pinfunction "2_2") (pintype "passive"))
    )
    (net (code "34") (name "CLAMP") (class "Default")
      (node (ref "C74") (pin "1") (pinfunction "1_1") (pintype "passive"))
      (node (ref "C75") (pin "1") (pinfunction "1_1") (pintype "passive"))
      (node (ref "D10") (pin "2") (pinfunction "C2_2") (pintype "passive"))
      (node (ref "D11") (pin "2") (pinfunction "C2_2") (pintype "passive"))
      (node (ref "D12") (pin "2") (pinfunction "C2_2") (pintype "passive"))
      (node (ref "D13") (pin "2") (pinfunction "C2_2") (pintype "passive"))
      (node (ref "D14") (pin "2") (pinfunction "C2_2") (pintype "passive"))
      (node (ref "D7") (pin "2") (pinfunction "C2_2") (pintype "passive"))
      (node (ref "D8") (pin "2") (pinfunction "C2_2") (pintype "passive"))
      (node (ref "D9") (pin "2") (pinfunction "C2_2") (pintype "passive"))
      (node (ref "IC20") (pin "1") (pinfunction "C_1") (pintype "passive"))
      (node (ref "R33") (pin "2") (pinfunction "2_2") (pintype "passive"))
      (node (ref "R34") (pin "1") (pinfunction "1_1") (pintype "passive"))
    )
    (net (code "35") (name "CURR_SW0") (class "Default")
      (node (ref "IC22") (pin "3") (pinfunction "IN_3") (pintype "input"))
      (node (ref "IC27") (pin "3") (pinfunction "IN_3") (pintype "input"))
      (node (ref "IC8") (pin "117") (pinfunction "PD3_117") (pintype "bidirectional"))
    )
    (net (code "36") (name "CURR_SW1") (class "Default")
      (node (ref "IC23") (pin "3") (pinfunction "IN_3") (pintype "input"))
      (node (ref "IC28") (pin "3") (pinfunction "IN_3") (pintype "input"))
      (node (ref "IC8") (pin "118") (pinfunction "PD4_118") (pintype "bidirectional"))
    )
    (net (code "37") (name "CURR_SW2") (class "Default")
      (node (ref "IC24") (pin "3") (pinfunction "IN_3") (pintype "input"))
      (node (ref "IC29") (pin "3") (pinfunction "IN_3") (pintype "input"))
      (node (ref "IC8") (pin "119") (pinfunction "PD5_119") (pintype "bidirectional"))
    )
    (net (code "38") (name "CURR_SW3") (class "Default")
      (node (ref "IC25") (pin "3") (pinfunction "IN_3") (pintype "input"))
      (node (ref "IC30") (pin "3") (pinfunction "IN_3") (pintype "input"))
      (node (ref "IC8") (pin "122") (pinfunction "PD6_122") (pintype "bidirectional"))
    )
    (net (code "39") (name "DAC_CLR#1") (class "Default")
      (node (ref "IC10") (pin "6") (pinfunction "CLR_6") (pintype "input"))
      (node (ref "IC8") (pin "21") (pinfunction "PF9_21") (pintype "bidirectional"))
    )
    (net (code "40") (name "DAC_CLR#2") (class "Default")
      (node (ref "IC11") (pin "6") (pinfunction "CLR_6") (pintype "input"))
      (node (ref "IC8") (pin "19") (pinfunction "PF7_19") (pintype "bidirectional"))
    )
    (net (code "41") (name "DAC_CLR-SEL#1") (class "Default")
      (node (ref "IC10") (pin "5") (pinfunction "CLR-SEL_5") (pintype "input"))
      (node (ref "IC8") (pin "22") (pinfunction "PF10_22") (pintype "bidirectional"))
    )
    (net (code "42") (name "DAC_CLR-SEL#2") (class "Default")
      (node (ref "IC11") (pin "5") (pinfunction "CLR-SEL_5") (pintype "input"))
      (node (ref "IC8") (pin "20") (pinfunction "PF8_20") (pintype "bidirectional"))
    )
    (net (code "43") (name "DAC_CS#1") (class "Default")
      (node (ref "IC10") (pin "7") (pinfunction "LATCH_7") (pintype "input"))
      (node (ref "IC8") (pin "27") (pinfunction "PC1_27") (pintype "bidirectional"))
    )
    (net (code "44") (name "DAC_CS#2") (class "Default")
      (node (ref "IC11") (pin "7") (pinfunction "LATCH_7") (pintype "input"))
      (node (ref "IC8") (pin "18") (pinfunction "PF6_18") (pintype "bidirectional"))
    )
    (net (code "45") (name "DAC_MISO") (class "Default")
      (node (ref "IC10") (pin "10") (pinfunction "SDO_10") (pintype "output"))
      (node (ref "IC11") (pin "10") (pinfunction "SDO_10") (pintype "output"))
      (node (ref "RN4") (pin "3") (pinfunction "1_3") (pintype "passive"))
    )
    (net (code "46") (name "DAC_MOSI") (class "Default")
      (node (ref "IC10") (pin "9") (pinfunction "DIN_9") (pintype "input"))
      (node (ref "IC11") (pin "9") (pinfunction "DIN_9") (pintype "input"))
      (node (ref "IC13") (pin "8") (pinfunction "DIN_8") (pintype "input"))
      (node (ref "RN4") (pin "4") (pinfunction "1_4") (pintype "passive"))
    )
    (net (code "47") (name "DAC_SCLK") (class "Default")
      (node (ref "IC10") (pin "8") (pinfunction "SCLK_8") (pintype "input"))
      (node (ref "IC11") (pin "8") (pinfunction "SCLK_8") (pintype "input"))
      (node (ref "IC13") (pin "7") (pinfunction "SCLK_7") (pintype "input"))
      (node (ref "RN4") (pin "2") (pinfunction "1_2") (pintype "passive"))
    )
    (net (code "48") (name "DIB_A0") (class "Default")
      (node (ref "IC1") (pin "1") (pinfunction "A0_1") (pintype "input"))
      (node (ref "RN3") (pin "3") (pinfunction "1_3") (pintype "passive"))
      (node (ref "X1") (pin "17") (pinfunction "1_17") (pintype "passive"))
    )
    (net (code "49") (name "DIB_A1") (class "Default")
      (node (ref "IC1") (pin "2") (pinfunction "A1_2") (pintype "input"))
      (node (ref "RN3") (pin "2") (pinfunction "1_2") (pintype "passive"))
      (node (ref "X1") (pin "19") (pinfunction "1_19") (pintype "passive"))
    )
    (net (code "50") (name "DIB_A2") (class "Default")
      (node (ref "IC1") (pin "3") (pinfunction "A2_3") (pintype "input"))
      (node (ref "RN3") (pin "1") (pinfunction "1_1") (pintype "passive"))
      (node (ref "X1") (pin "18") (pinfunction "1_18") (pintype "passive"))
    )
    (net (code "51") (name "DIB_BOOT") (class "Default")
      (node (ref "IC3") (pin "4") (pinfunction "A2_4") (pintype "input"))
      (node (ref "X1") (pin "26") (pinfunction "1_26") (pintype "passive"))
    )
    (net (code "52") (name "DIB_CSA") (class "Default")
      (node (ref "IC2") (pin "5") (pinfunction "A3_5") (pintype "input"))
      (node (ref "RN2") (pin "2") (pinfunction "1_2") (pintype "passive"))
    )
    (net (code "53") (name "DIB_CSB") (class "Default")
      (node (ref "JP1") (pin "NO") (pinfunction "NO_NO") (pintype "passive"))
      (node (ref "X1") (pin "12") (pinfunction "1_12") (pintype "passive"))
    )
    (net (code "54") (name "DIB_IRQ") (class "Default")
      (node (ref "JP1") (pin "NC") (pinfunction "NC_NC") (pintype "passive"))
      (node (ref "X1") (pin "10") (pinfunction "1_10") (pintype "passive"))
    )
    (net (code "55") (name "DIB_MISO") (class "Default")
      (node (ref "IC2") (pin "6") (pinfunction "A4_6") (pintype "output"))
      (node (ref "RN2") (pin "1") (pinfunction "1_1") (pintype "passive"))
    )
    (net (code "56") (name "DIB_MOSI") (class "Default")
      (node (ref "IC2") (pin "3") (pinfunction "A1_3") (pintype "input"))
      (node (ref "RN2") (pin "4") (pinfunction "1_4") (pintype "passive"))
    )
    (net (code "57") (name "DIB_NRESET") (class "Default")
      (node (ref "IC3") (pin "5") (pinfunction "A3_5") (pintype "input"))
      (node (ref "X1") (pin "4") (pinfunction "1_4") (pintype "passive"))
    )
    (net (code "58") (name "DIB_SCL") (class "Default")
      (node (ref "IC1") (pin "6") (pinfunction "SCL_6") (pintype "bidirectional"))
      (node (ref "X1") (pin "5") (pinfunction "1_5") (pintype "passive"))
    )
    (net (code "59") (name "DIB_SCLK") (class "Default")
      (node (ref "IC2") (pin "4") (pinfunction "A2_4") (pintype "input"))
      (node (ref "RN2") (pin "3") (pinfunction "1_3") (pintype "passive"))
    )
    (net (code "60") (name "DIB_SDA") (class "Default")
      (node (ref "IC1") (pin "5") (pinfunction "SDA_5") (pintype "bidirectional"))
      (node (ref "X1") (pin "8") (pinfunction "1_8") (pintype "passive"))
    )
    (net (code "61") (name "DIN0") (class "Default")
      (node (ref "C76") (pin "1") (pinfunction "1_1") (pintype "passive"))
      (node (ref "C81") (pin "1") (pinfunction "1_1") (pintype "passive"))
      (node (ref "D7") (pin "3") (pinfunction "C1A2_3") (pintype "passive"))
      (node (ref "IC8") (pin "34") (pinfunction "PA0-WKUP_34") (pintype "bidirectional"))
      (node (ref "R36") (pin "2") (pinfunction "2_2") (pintype "passive"))
      (node (ref "R44") (pin "2") (pinfunction "2_2") (pintype "passive"))
      (node (ref "R52") (pin "1") (pinfunction "1_1") (pintype "passive"))
    )
    (net (code "62") (name "DIN1") (class "Default")
      (node (ref "C77") (pin "1") (pinfunction "1_1") (pintype "passive"))
      (node (ref "C82") (pin "1") (pinfunction "1_1") (pintype "passive"))
      (node (ref "D8") (pin "3") (pinfunction "C1A2_3") (pintype "passive"))
      (node (ref "IC8") (pin "35") (pinfunction "PA1_35") (pintype "bidirectional"))
      (node (ref "R37") (pin "2") (pinfunction "2_2") (pintype "passive"))
      (node (ref "R45") (pin "2") (pinfunction "2_2") (pintype "passive"))
      (node (ref "R53") (pin "1") (pinfunction "1_1") (pintype "passive"))
    )
    (net (code "63") (name "DIN2") (class "Default")
      (node (ref "C78") (pin "1") (pinfunction "1_1") (pintype "passive"))
      (node (ref "D9") (pin "3") (pinfunction "C1A2_3") (pintype "passive"))
      (node (ref "IC8") (pin "96") (pinfunction "PC6_96") (pintype "bidirectional"))
      (node (ref "R38") (pin "2") (pinfunction "2_2") (pintype "passive"))
      (node (ref "R46") (pin "2") (pinfunction "2_2") (pintype "passive"))
      (node (ref "R54") (pin "1") (pinfunction "1_1") (pintype "passive"))
    )
    (net (code "64") (name "DIN3") (class "Default")
      (node (ref "C83") (pin "1") (pinfunction "1_1") (pintype "passive"))
      (node (ref "D10") (pin "3") (pinfunction "C1A2_3") (pintype "passive"))
      (node (ref "IC8") (pin "97") (pinfunction "PC7_97") (pintype "bidirectional"))
      (node (ref "R39") (pin "2") (pinfunction "2_2") (pintype "passive"))
      (node (ref "R47") (pin "2") (pinfunction "2_2") (pintype "passive"))
      (node (ref "R55") (pin "1") (pinfunction "1_1") (pintype "passive"))
    )
    (net (code "65") (name "DIN4") (class "Default")
      (node (ref "C79") (pin "1") (pinfunction "1_1") (pintype "passive"))
      (node (ref "D11") (pin "3") (pinfunction "C1A2_3") (pintype "passive"))
      (node (ref "IC8") (pin "134") (pinfunction "PB4_134") (pintype "bidirectional"))
      (node (ref "R40") (pin "2") (pinfunction "2_2") (pintype "passive"))
      (node (ref "R48") (pin "2") (pinfunction "2_2") (pintype "passive"))
      (node (ref "R56") (pin "1") (pinfunction "1_1") (pintype "passive"))
    )
    (net (code "66") (name "DIN5") (class "Default")
      (node (ref "C84") (pin "1") (pinfunction "1_1") (pintype "passive"))
      (node (ref "D12") (pin "3") (pinfunction "C1A2_3") (pintype "passive"))
      (node (ref "IC8") (pin "135") (pinfunction "PB5_135") (pintype "bidirectional"))
      (node (ref "R41") (pin "2") (pinfunction "2_2") (pintype "passive"))
      (node (ref "R49") (pin "2") (pinfunction "2_2") (pintype "passive"))
      (node (ref "R57") (pin "1") (pinfunction "1_1") (pintype "passive"))
    )
    (net (code "67") (name "DIN6") (class "Default")
      (node (ref "C80") (pin "1") (pinfunction "1_1") (pintype "passive"))
      (node (ref "D13") (pin "3") (pinfunction "C1A2_3") (pintype "passive"))
      (node (ref "IC8") (pin "136") (pinfunction "PB6_136") (pintype "bidirectional"))
      (node (ref "R42") (pin "2") (pinfunction "2_2") (pintype "passive"))
      (node (ref "R50") (pin "2") (pinfunction "2_2") (pintype "passive"))
      (node (ref "R58") (pin "1") (pinfunction "1_1") (pintype "passive"))
    )
    (net (code "68") (name "DIN7") (class "Default")
      (node (ref "C85") (pin "1") (pinfunction "1_1") (pintype "passive"))
      (node (ref "D14") (pin "3") (pinfunction "C1A2_3") (pintype "passive"))
      (node (ref "IC8") (pin "137") (pinfunction "PB7_137") (pintype "bidirectional"))
      (node (ref "R43") (pin "2") (pinfunction "2_2") (pintype "passive"))
      (node (ref "R51") (pin "2") (pinfunction "2_2") (pintype "passive"))
      (node (ref "R59") (pin "1") (pinfunction "1_1") (pintype "passive"))
    )
    (net (code "69") (name "DOUT0") (class "Default")
      (node (ref "IC18") (pin "2") (pinfunction "IN1_2") (pintype "input"))
      (node (ref "IC8") (pin "36") (pinfunction "PA2_36") (pintype "bidirectional"))
    )
    (net (code "70") (name "DOUT1") (class "Default")
      (node (ref "IC18") (pin "3") (pinfunction "IN2_3") (pintype "input"))
      (node (ref "IC8") (pin "101") (pinfunction "PA9_101") (pintype "bidirectional"))
    )
    (net (code "71") (name "DOUT2") (class "Default")
      (node (ref "IC17") (pin "2") (pinfunction "IN1_2") (pintype "input"))
      (node (ref "IC8") (pin "91") (pinfunction "PG6_91") (pintype "bidirectional"))
    )
    (net (code "72") (name "DOUT3") (class "Default")
      (node (ref "IC17") (pin "3") (pinfunction "IN2_3") (pintype "input"))
      (node (ref "IC8") (pin "92") (pinfunction "PG7_92") (pintype "bidirectional"))
    )
    (net (code "73") (name "DOUT4") (class "Default")
      (node (ref "IC16") (pin "2") (pinfunction "IN1_2") (pintype "input"))
      (node (ref "IC8") (pin "44") (pinfunction "PC4_44") (pintype "bidirectional"))
    )
    (net (code "74") (name "DOUT5") (class "Default")
      (node (ref "IC16") (pin "3") (pinfunction "IN2_3") (pintype "input"))
      (node (ref "IC8") (pin "45") (pinfunction "PC5_45") (pintype "bidirectional"))
    )
    (net (code "75") (name "DOUT6") (class "Default")
      (node (ref "IC15") (pin "2") (pinfunction "IN1_2") (pintype "input"))
      (node (ref "IC8") (pin "46") (pinfunction "PB0_46") (pintype "bidirectional"))
    )
    (net (code "76") (name "DOUT7") (class "Default")
      (node (ref "IC15") (pin "3") (pinfunction "IN2_3") (pintype "input"))
      (node (ref "IC8") (pin "47") (pinfunction "PB1_47") (pintype "bidirectional"))
    )
    (net (code "77") (name "GND") (class "Default")
      (node (ref "C10") (pin "2") (pinfunction "2_2") (pintype "passive"))
      (node (ref "C11") (pin "1") (pinfunction "1_1") (pintype "passive"))
      (node (ref "C13") (pin "1") (pinfunction "1_1") (pintype "passive"))
      (node (ref "C14") (pin "2") (pinfunction "2_2") (pintype "passive"))
      (node (ref "C15") (pin "2") (pinfunction "2_2") (pintype "passive"))
      (node (ref "C16") (pin "1") (pinfunction "1_1") (pintype "passive"))
      (node (ref "C17") (pin "1") (pinfunction "1_1") (pintype "passive"))
      (node (ref "C19") (pin "2") (pinfunction "2_2") (pintype "passive"))
      (node (ref "C20") (pin "1") (pinfunction "1_1") (pintype "passive"))
      (node (ref "C21") (pin "1") (pinfunction "1_1") (pintype "passive"))
      (node (ref "C23") (pin "-") (pinfunction "-_-") (pintype "passive"))
      (node (ref "C24") (pin "2") (pinfunction "2_2") (pintype "passive"))
      (node (ref "C25") (pin "2") (pinfunction "2_2") (pintype "passive"))
      (node (ref "C26") (pin "2") (pinfunction "2_2") (pintype "passive"))
      (node (ref "C27") (pin "2") (pinfunction "2_2") (pintype "passive"))
      (node (ref "C28") (pin "2") (pinfunction "2_2") (pintype "passive"))
      (node (ref "C29") (pin "2") (pinfunction "2_2") (pintype "passive"))
      (node (ref "C3") (pin "1") (pinfunction "1_1") (pintype "passive"))
      (node (ref "C30") (pin "2") (pinfunction "2_2") (pintype "passive"))
      (node (ref "C31") (pin "2") (pinfunction "2_2") (pintype "passive"))
      (node (ref "C32") (pin "2") (pinfunction "2_2") (pintype "passive"))
      (node (ref "C33") (pin "2") (pinfunction "2_2") (pintype "passive"))
      (node (ref "C34") (pin "2") (pinfunction "2_2") (pintype "passive"))
      (node (ref "C35") (pin "2") (pinfunction "2_2") (pintype "passive"))
      (node (ref "C36") (pin "2") (pinfunction "2_2") (pintype "passive"))
      (node (ref "C37") (pin "1") (pinfunction "1_1") (pintype "passive"))
      (node (ref "C38") (pin "1") (pinfunction "1_1") (pintype "passive"))
      (node (ref "C40") (pin "2") (pinfunction "2_2") (pintype "passive"))
      (node (ref "C41") (pin "2") (pinfunction "2_2") (pintype "passive"))
      (node (ref "C42") (pin "1") (pinfunction "1_1") (pintype "passive"))
      (node (ref "C43") (pin "2") (pinfunction "2_2") (pintype "passive"))
      (node (ref "C44") (pin "2") (pinfunction "2_2") (pintype "passive"))
      (node (ref "C45") (pin "2") (pinfunction "2_2") (pintype "passive"))
      (node (ref "C46") (pin "1") (pinfunction "1_1") (pintype "passive"))
      (node (ref "C47") (pin "1") (pinfunction "1_1") (pintype "passive"))
      (node (ref "C49") (pin "2") (pinfunction "2_2") (pintype "passive"))
      (node (ref "C5") (pin "1") (pinfunction "1_1") (pintype "passive"))
      (node (ref "C50") (pin "2") (pinfunction "2_2") (pintype "passive"))
      (node (ref "C51") (pin "1") (pinfunction "1_1") (pintype "passive"))
      (node (ref "C52") (pin "2") (pinfunction "2_2") (pintype "passive"))
      (node (ref "C53") (pin "2") (pinfunction "2_2") (pintype "passive"))
      (node (ref "C54") (pin "2") (pinfunction "2_2") (pintype "passive"))
      (node (ref "C55") (pin "2") (pinfunction "2_2") (pintype "passive"))
      (node (ref "C56") (pin "2") (pinfunction "2_2") (pintype "passive"))
      (node (ref "C57") (pin "1") (pinfunction "1_1") (pintype "passive"))
      (node (ref "C58") (pin "1") (pinfunction "1_1") (pintype "passive"))
      (node (ref "C59") (pin "2") (pinfunction "2_2") (pintype "passive"))
      (node (ref "C60") (pin "2") (pinfunction "2_2") (pintype "passive"))
      (node (ref "C61") (pin "1") (pinfunction "1_1") (pintype "passive"))
      (node (ref "C62") (pin "2") (pinfunction "2_2") (pintype "passive"))
      (node (ref "C63") (pin "2") (pinfunction "2_2") (pintype "passive"))
      (node (ref "C64") (pin "1") (pinfunction "1_1") (pintype "passive"))
      (node (ref "C65") (pin "2") (pinfunction "2_2") (pintype "passive"))
      (node (ref "C66") (pin "2") (pinfunction "2_2") (pintype "passive"))
      (node (ref "C67") (pin "1") (pinfunction "1_1") (pintype "passive"))
      (node (ref "C68") (pin "1") (pinfunction "1_1") (pintype "passive"))
      (node (ref "C69") (pin "1") (pinfunction "1_1") (pintype "passive"))
      (node (ref "C70") (pin "1") (pinfunction "1_1") (pintype "passive"))
      (node (ref "C71") (pin "1") (pinfunction "1_1") (pintype "passive"))
      (node (ref "C72") (pin "2") (pinfunction "2_2") (pintype "passive"))
      (node (ref "C73") (pin "2") (pinfunction "2_2") (pintype "passive"))
      (node (ref "C74") (pin "2") (pinfunction "2_2") (pintype "passive"))
      (node (ref "C75") (pin "2") (pinfunction "2_2") (pintype "passive"))
      (node (ref "C76") (pin "2") (pinfunction "2_2") (pintype "passive"))
      (node (ref "C77") (pin "2") (pinfunction "2_2") (pintype "passive"))
      (node (ref "C78") (pin "2") (pinfunction "2_2") (pintype "passive"))
      (node (ref "C79") (pin "2") (pinfunction "2_2") (pintype "passive"))
      (node (ref "C80") (pin "2") (pinfunction "2_2") (pintype "passive"))
      (node (ref "C83") (pin "2") (pinfunction "2_2") (pintype "passive"))
      (node (ref "C84") (pin "2") (pinfunction "2_2") (pintype "passive"))
      (node (ref "C85") (pin "2") (pinfunction "2_2") (pintype "passive"))
      (node (ref "C86") (pin "2") (pinfunction "2_2") (pintype "passive"))
      (node (ref "C87") (pin "2") (pinfunction "2_2") (pintype "passive"))
      (node (ref "C88") (pin "2") (pinfunction "2_2") (pintype "passive"))
      (node (ref "C89") (pin "2") (pinfunction "2_2") (pintype "passive"))
      (node (ref "C92") (pin "1") (pinfunction "1_1") (pintype "passive"))
      (node (ref "C93") (pin "1") (pinfunction "1_1") (pintype "passive"))
      (node (ref "C94") (pin "1") (pinfunction "1_1") (pintype "passive"))
      (node (ref "C95") (pin "1") (pinfunction "1_1") (pintype "passive"))
      (node (ref "C96") (pin "1") (pinfunction "1_1") (pintype "passive"))
      (node (ref "D10") (pin "1") (pinfunction "A1_1") (pintype "passive"))
      (node (ref "D11") (pin "1") (pinfunction "A1_1") (pintype "passive"))
      (node (ref "D12") (pin "1") (pinfunction "A1_1") (pintype "passive"))
      (node (ref "D13") (pin "1") (pinfunction "A1_1") (pintype "passive"))
      (node (ref "D14") (pin "1") (pinfunction "A1_1") (pintype "passive"))
      (node (ref "D5") (pin "1") (pinfunction "A1_1") (pintype "passive"))
      (node (ref "D6") (pin "1") (pinfunction "A1_1") (pintype "passive"))
      (node (ref "D7") (pin "1") (pinfunction "A1_1") (pintype "passive"))
      (node (ref "D8") (pin "1") (pinfunction "A1_1") (pintype "passive"))
      (node (ref "D9") (pin "1") (pinfunction "A1_1") (pintype "passive"))
      (node (ref "IC10") (pin "11") (pinfunction "GND_11") (pintype "power_in"))
      (node (ref "IC10") (pin "12") (pinfunction "GND_12") (pintype "power_in"))
      (node (ref "IC10") (pin "16") (pinfunction "DVDD-EN_16") (pintype "power_in"))
      (node (ref "IC10") (pin "4") (pinfunction "GND_4") (pintype "power_in"))
      (node (ref "IC11") (pin "11") (pinfunction "GND_11") (pintype "power_in"))
      (node (ref "IC11") (pin "12") (pinfunction "GND_12") (pintype "power_in"))
      (node (ref "IC11") (pin "16") (pinfunction "DVDD-EN_16") (pintype "power_in"))
      (node (ref "IC11") (pin "4") (pinfunction "GND_4") (pintype "power_in"))
      (node (ref "IC12") (pin "2") (pinfunction "V-_2") (pintype "power_in"))
      (node (ref "IC13") (pin "3") (pinfunction "GND_3") (pintype "power_in"))
      (node (ref "IC13") (pin "4") (pinfunction "~{LDAC}_4") (pintype "input"))
      (node (ref "IC19") (pin "7") (pinfunction "V-_7") (pintype "power_in"))
      (node (ref "IC2") (pin "15") (pinfunction "GND2_15") (pintype "passive"))
      (node (ref "IC2") (pin "9") (pinfunction "GND2_2_9") (pintype "passive"))
      (node (ref "IC20") (pin "3") (pinfunction "A_3") (pintype "passive"))
      (node (ref "IC21") (pin "4") (pinfunction "GND_4") (pintype "passive"))
      (node (ref "IC22") (pin "4") (pinfunction "GND_4") (pintype "passive"))
      (node (ref "IC23") (pin "4") (pinfunction "GND_4") (pintype "passive"))
      (node (ref "IC24") (pin "4") (pinfunction "GND_4") (pintype "passive"))
      (node (ref "IC25") (pin "4") (pinfunction "GND_4") (pintype "passive"))
      (node (ref "IC26") (pin "4") (pinfunction "GND_4") (pintype "passive"))
      (node (ref "IC27") (pin "4") (pinfunction "GND_4") (pintype "passive"))
      (node (ref "IC28") (pin "4") (pinfunction "GND_4") (pintype "passive"))
      (node (ref "IC29") (pin "4") (pinfunction "GND_4") (pintype "passive"))
      (node (ref "IC3") (pin "15") (pinfunction "GND2_15") (pintype "passive"))
      (node (ref "IC3") (pin "9") (pinfunction "GND2_2_9") (pintype "passive"))
      (node (ref "IC30") (pin "4") (pinfunction "GND_4") (pintype "passive"))
      (node (ref "IC31") (pin "4") (pinfunction "GND_4") (pintype "passive"))
      (node (ref "IC32") (pin "4") (pinfunction "GND_4") (pintype "passive"))
      (node (ref "IC33") (pin "4") (pinfunction "GND_4") (pintype "passive"))
      (node (ref "IC34") (pin "4") (pinfunction "GND_4") (pintype "passive"))
      (node (ref "IC35") (pin "2") (pinfunction "V-_2") (pintype "power_in"))
      (node (ref "IC36") (pin "11") (pinfunction "AUX_GND_11") (pintype "power_in"))
      (node (ref "IC36") (pin "28") (pinfunction "AGND_28") (pintype "power_in"))
      (node (ref "IC36") (pin "29") (pinfunction "AGND_29") (pintype "power_in"))
      (node (ref "IC36") (pin "3") (pinfunction "DAISY_3") (pintype "input"))
      (node (ref "IC36") (pin "31") (pinfunction "AGND_31") (pintype "power_in"))
      (node (ref "IC36") (pin "32") (pinfunction "AGND_32") (pintype "power_in"))
      (node (ref "IC36") (pin "33") (pinfunction "DGND_33") (pintype "power_in"))
      (node (ref "IC36") (pin "4") (pinfunction "~{REFSEL}_4") (pintype "input"))
      (node (ref "IC36") (pin "6") (pinfunction "REFGND_6") (pintype "power_in"))
      (node (ref "IC36") (pin "8") (pinfunction "AGND_8") (pintype "power_in"))
      (node (ref "IC4") (pin "2") (pinfunction "GND_2") (pintype "passive"))
      (node (ref "IC4") (pin "3") (pinfunction "GND_3") (pintype "passive"))
      (node (ref "IC4") (pin "6") (pinfunction "GND_6") (pintype "passive"))
      (node (ref "IC4") (pin "7") (pinfunction "GND_7") (pintype "passive"))
      (node (ref "IC5") (pin "1") (pinfunction "ADJ/GND_1") (pintype "passive"))
      (node (ref "IC6") (pin "2") (pinfunction "GND_2") (pintype "passive"))
      (node (ref "IC7") (pin "5") (pinfunction "GND_5") (pintype "passive"))
      (node (ref "IC8") (pin "107") (pinfunction "VSS_8_107") (pintype "power_in"))
      (node (ref "IC8") (pin "120") (pinfunction "VSS_9_120") (pintype "power_in"))
      (node (ref "IC8") (pin "130") (pinfunction "VSS_130") (pintype "power_in"))
      (node (ref "IC8") (pin "16") (pinfunction "VSS_2_16") (pintype "bidirectional"))
      (node (ref "IC8") (pin "31") (pinfunction "VSSA_31") (pintype "power_in"))
      (node (ref "IC8") (pin "38") (pinfunction "VSS_3_38") (pintype "power_in"))
      (node (ref "IC8") (pin "48") (pinfunction "PB2-BOOT1_48") (pintype "bidirectional"))
      (node (ref "IC8") (pin "51") (pinfunction "VSS_4_51") (pintype "power_in"))
      (node (ref "IC8") (pin "61") (pinfunction "VSS_5_61") (pintype "power_in"))
      (node (ref "IC8") (pin "83") (pinfunction "VSS_6_83") (pintype "power_in"))
      (node (ref "IC8") (pin "94") (pinfunction "VSS_7_94") (pintype "power_in"))
      (node (ref "J2") (pin "6") (pinfunction "VSS_6") (pintype "power_in"))
      (node (ref "J2") (pin "S") (pinfunction "SH_S") (pintype "passive"))
      (node (ref "J2") (pin "S1") (pinfunction "SH_S1") (pintype "passive"))
      (node (ref "J2") (pin "S2") (pinfunction "SH_S2") (pintype "passive"))
      (node (ref "J2") (pin "SW2") (pinfunction "SW2_SW2") (pintype "passive"))
      (node (ref "JP10") (pin "2") (pinfunction "2_2") (pintype "passive"))
      (node (ref "JP12") (pin "2") (pinfunction "2_2") (pintype "passive"))
      (node (ref "JP7") (pin "2") (pinfunction "2_2") (pintype "passive"))
      (node (ref "JP8") (pin "2") (pinfunction "2_2") (pintype "passive"))
      (node (ref "L2") (pin "3") (pinfunction "3_3") (pintype "passive"))
      (node (ref "L3") (pin "2") (pinfunction "2_2") (pintype "passive"))
      (node (ref "Q1") (pin "1") (pinfunction "S_1") (pintype "passive"))
      (node (ref "Q1") (pin "4") (pinfunction "S_4") (pintype "passive"))
      (node (ref "Q2") (pin "1") (pinfunction "S_1") (pintype "passive"))
      (node (ref "Q2") (pin "4") (pinfunction "S_4") (pintype "passive"))
      (node (ref "Q3") (pin "1") (pinfunction "S_1") (pintype "passive"))
      (node (ref "Q3") (pin "4") (pinfunction "S_4") (pintype "passive"))
      (node (ref "Q4") (pin "1") (pinfunction "S_1") (pintype "passive"))
      (node (ref "Q4") (pin "4") (pinfunction "S_4") (pintype "passive"))
      (node (ref "Q5") (pin "1") (pinfunction "S_1") (pintype "passive"))
      (node (ref "Q5") (pin "4") (pinfunction "S_4") (pintype "passive"))
      (node (ref "R10") (pin "1") (pinfunction "1_1") (pintype "passive"))
      (node (ref "R14") (pin "1") (pinfunction "1_1") (pintype "passive"))
      (node (ref "R22") (pin "2") (pinfunction "2_2") (pintype "passive"))
      (node (ref "R23") (pin "2") (pinfunction "2_2") (pintype "passive"))
      (node (ref "R29") (pin "2") (pinfunction "2_2") (pintype "passive"))
      (node (ref "R35") (pin "2") (pinfunction "2_2") (pintype "passive"))
      (node (ref "R44") (pin "1") (pinfunction "1_1") (pintype "passive"))
      (node (ref "R45") (pin "1") (pinfunction "1_1") (pintype "passive"))
      (node (ref "R46") (pin "1") (pinfunction "1_1") (pintype "passive"))
      (node (ref "R47") (pin "1") (pinfunction "1_1") (pintype "passive"))
      (node (ref "R48") (pin "1") (pinfunction "1_1") (pintype "passive"))
      (node (ref "R49") (pin "1") (pinfunction "1_1") (pintype "passive"))
      (node (ref "R50") (pin "1") (pinfunction "1_1") (pintype "passive"))
      (node (ref "R51") (pin "1") (pinfunction "1_1") (pintype "passive"))
      (node (ref "R61") (pin "2") (pinfunction "2_2") (pintype "passive"))
      (node (ref "R7") (pin "1") (pinfunction "1_1") (pintype "passive"))
      (node (ref "SH1") (pin "1") (pinfunction "GND_A_1") (pintype "bidirectional"))
      (node (ref "SH2") (pin "1") (pinfunction "GND_A_1") (pintype "bidirectional"))
      (node (ref "TP1") (pin "1") (pinfunction "P$1_1") (pintype "bidirectional"))
      (node (ref "TVS1") (pin "C1") (pinfunction "1_C1") (pintype "passive"))
      (node (ref "TVS2") (pin "C1") (pinfunction "1_C1") (pintype "passive"))
      (node (ref "TVS3") (pin "C1") (pinfunction "1_C1") (pintype "passive"))
      (node (ref "TVS4") (pin "C1") (pinfunction "1_C1") (pintype "passive"))
      (node (ref "X2") (pin "3") (pinfunction "1_3") (pintype "passive"))
      (node (ref "X3") (pin "1") (pinfunction "1_1") (pintype "passive"))
      (node (ref "X3") (pin "8") (pinfunction "1_8") (pintype "passive"))
      (node (ref "X5") (pin "1") (pinfunction "1_1") (pintype "passive"))
      (node (ref "X7") (pin "1") (pinfunction "1_1") (pintype "passive"))
      (node (ref "ZD1") (pin "A") (pinfunction "A_A") (pintype "passive"))
      (node (ref "ZD2") (pin "A") (pinfunction "A_A") (pintype "passive"))
    )
    (net (code "78") (name "GNDIO") (class "Default")
      (node (ref "C1") (pin "1") (pinfunction "1_1") (pintype "passive"))
      (node (ref "C2") (pin "2") (pinfunction "2_2") (pintype "passive"))
      (node (ref "C4") (pin "2") (pinfunction "2_2") (pintype "passive"))
      (node (ref "C7") (pin "1") (pinfunction "1_1") (pintype "passive"))
      (node (ref "IC1") (pin "4") (pinfunction "GND_4") (pintype "passive"))
      (node (ref "IC1") (pin "7") (pinfunction "WP_7") (pintype "input"))
      (node (ref "IC2") (pin "2") (pinfunction "GND1_2_2") (pintype "passive"))
      (node (ref "IC2") (pin "8") (pinfunction "GND1_8") (pintype "passive"))
      (node (ref "IC3") (pin "2") (pinfunction "GND1_2_2") (pintype "passive"))
      (node (ref "IC3") (pin "8") (pinfunction "GND1_8") (pintype "passive"))
      (node (ref "L1") (pin "1") (pinfunction "1_1") (pintype "passive"))
      (node (ref "X1") (pin "11") (pinfunction "1_11") (pintype "passive"))
      (node (ref "X1") (pin "16") (pinfunction "1_16") (pintype "passive"))
      (node (ref "X1") (pin "20") (pinfunction "1_20") (pintype "passive"))
      (node (ref "X1") (pin "25") (pinfunction "1_25") (pintype "passive"))
      (node (ref "X1") (pin "7") (pinfunction "1_7") (pintype "passive"))
    )
    (net (code "79") (name "IN_CTRL0") (class "Default")
      (node (ref "IC8") (pin "123") (pinfunction "PD7_123") (pintype "bidirectional"))
      (node (ref "Q2") (pin "2") (pinfunction "G_2") (pintype "passive"))
    )
    (net (code "80") (name "IN_CTRL1") (class "Default")
      (node (ref "IC8") (pin "124") (pinfunction "PG9_124") (pintype "bidirectional"))
      (node (ref "Q2") (pin "5") (pinfunction "G_5") (pintype "passive"))
    )
    (net (code "81") (name "IN_CTRL2") (class "Default")
      (node (ref "IC8") (pin "125") (pinfunction "PG10_125") (pintype "bidirectional"))
      (node (ref "Q3") (pin "2") (pinfunction "G_2") (pintype "passive"))
    )
    (net (code "82") (name "IN_CTRL3") (class "Default")
      (node (ref "IC8") (pin "126") (pinfunction "PG11_126") (pintype "bidirectional"))
      (node (ref "Q3") (pin "5") (pinfunction "G_5") (pintype "passive"))
    )
    (net (code "83") (name "IN_CTRL4") (class "Default")
      (node (ref "IC8") (pin "127") (pinfunction "PG12_127") (pintype "bidirectional"))
      (node (ref "Q4") (pin "2") (pinfunction "G_2") (pintype "passive"))
    )
    (net (code "84") (name "IN_CTRL5") (class "Default")
      (node (ref "IC8") (pin "128") (pinfunction "PG13_128") (pintype "bidirectional"))
      (node (ref "Q4") (pin "5") (pinfunction "G_5") (pintype "passive"))
    )
    (net (code "85") (name "IN_CTRL6") (class "Default")
      (node (ref "IC8") (pin "129") (pinfunction "PG14_129") (pintype "bidirectional"))
      (node (ref "Q5") (pin "2") (pinfunction "G_2") (pintype "passive"))
    )
    (net (code "86") (name "IN_CTRL7") (class "Default")
      (node (ref "IC8") (pin "133") (pinfunction "PB3_133") (pintype "bidirectional"))
      (node (ref "Q5") (pin "5") (pinfunction "G_5") (pintype "passive"))
    )
    (net (code "87") (name "IRQ") (class "Default")
      (node (ref "IC3") (pin "11") (pinfunction "B4_11") (pintype "input"))
      (node (ref "IC8") (pin "69") (pinfunction "PB10_69") (pintype "bidirectional"))
    )
    (net (code "88") (name "MISO") (class "Default")
      (node (ref "IC8") (pin "66") (pinfunction "PE13_66") (pintype "bidirectional"))
      (node (ref "RN1") (pin "6") (pinfunction "2_6") (pintype "passive"))
    )
    (net (code "89") (name "MOSI") (class "Default")
      (node (ref "IC8") (pin "67") (pinfunction "PE14_67") (pintype "bidirectional"))
      (node (ref "RN1") (pin "5") (pinfunction "2_5") (pintype "passive"))
    )
    (net (code "90") (name "NSS") (class "Default")
      (node (ref "IC8") (pin "64") (pinfunction "PE11_64") (pintype "bidirectional"))
      (node (ref "RN1") (pin "8") (pinfunction "2_8") (pintype "passive"))
    )
    (net (code "91") (name "Net-(D1-C1A2)") (class "Default")
      (node (ref "C40") (pin "1") (pinfunction "1_1") (pintype "passive"))
      (node (ref "D1") (pin "3") (pinfunction "C1A2_3") (pintype "passive"))
      (node (ref "L5") (pin "P$2") (pinfunction "2_P$2") (pintype "passive"))
      (node (ref "TVS1") (pin "C2") (pinfunction "2_C2") (pintype "passive"))
      (node (ref "X3") (pin "2") (pinfunction "1_2") (pintype "passive"))
    )
    (net (code "92") (name "Net-(D2-C1A2)") (class "Default")
      (node (ref "C49") (pin "1") (pinfunction "1_1") (pintype "passive"))
      (node (ref "D2") (pin "3") (pinfunction "C1A2_3") (pintype "passive"))
      (node (ref "L6") (pin "P$2") (pinfunction "2_P$2") (pintype "passive"))
      (node (ref "TVS2") (pin "C2") (pinfunction "2_C2") (pintype "passive"))
      (node (ref "X3") (pin "3") (pinfunction "1_3") (pintype "passive"))
    )
    (net (code "93") (name "Net-(D3-C1A2)") (class "Default")
      (node (ref "C60") (pin "1") (pinfunction "1_1") (pintype "passive"))
      (node (ref "D3") (pin "3") (pinfunction "C1A2_3") (pintype "passive"))
      (node (ref "R17") (pin "1") (pinfunction "1_1") (pintype "passive"))
      (node (ref "R20") (pin "2") (pinfunction "2_2") (pintype "passive"))
      (node (ref "X3") (pin "4") (pinfunction "1_4") (pintype "passive"))
    )
    (net (code "94") (name "Net-(D4-C1A2)") (class "Default")
      (node (ref "C66") (pin "1") (pinfunction "1_1") (pintype "passive"))
      (node (ref "D4") (pin "3") (pinfunction "C1A2_3") (pintype "passive"))
      (node (ref "R25") (pin "1") (pinfunction "1_1") (pintype "passive"))
      (node (ref "R27") (pin "2") (pinfunction "2_2") (pintype "passive"))
      (node (ref "X3") (pin "5") (pinfunction "1_5") (pintype "passive"))
    )
    (net (code "95") (name "Net-(D5-C1A2)") (class "Default")
      (node (ref "D5") (pin "3") (pinfunction "C1A2_3") (pintype "passive"))
      (node (ref "IC19") (pin "3") (pinfunction "O_3") (pintype "output"))
      (node (ref "IC19") (pin "6") (pinfunction "O_6") (pintype "output"))
      (node (ref "JP4") (pin "1") (pinfunction "1_1") (pintype "passive"))
    )
    (net (code "96") (name "Net-(D6-C1A2)") (class "Default")
      (node (ref "D6") (pin "3") (pinfunction "C1A2_3") (pintype "passive"))
      (node (ref "IC19") (pin "11") (pinfunction "O_11") (pintype "output"))
      (node (ref "IC19") (pin "8") (pinfunction "O_8") (pintype "output"))
      (node (ref "JP5") (pin "1") (pinfunction "1_1") (pintype "passive"))
    )
    (net (code "97") (name "Net-(IC2-B1)") (class "Default")
      (node (ref "IC2") (pin "14") (pinfunction "B1_14") (pintype "output"))
      (node (ref "RN1") (pin "4") (pinfunction "1_4") (pintype "passive"))
    )
    (net (code "98") (name "Net-(IC2-B2)") (class "Default")
      (node (ref "IC2") (pin "13") (pinfunction "B2_13") (pintype "output"))
      (node (ref "RN1") (pin "2") (pinfunction "1_2") (pintype "passive"))
    )
    (net (code "99") (name "Net-(IC2-B3)") (class "Default")
      (node (ref "IC2") (pin "12") (pinfunction "B3_12") (pintype "output"))
      (node (ref "RN1") (pin "1") (pinfunction "1_1") (pintype "passive"))
    )
    (net (code "100") (name "Net-(IC2-B4)") (class "Default")
      (node (ref "IC2") (pin "11") (pinfunction "B4_11") (pintype "input"))
      (node (ref "RN1") (pin "3") (pinfunction "1_3") (pintype "passive"))
    )
    (net (code "101") (name "Net-(IC3-A4)") (class "Default")
      (node (ref "IC3") (pin "6") (pinfunction "A4_6") (pintype "output"))
      (node (ref "JP1") (pin "COM") (pinfunction "COM_COM") (pintype "passive"))
    )
    (net (code "102") (name "Net-(IC6-BYPASS)") (class "Default")
      (node (ref "C17") (pin "2") (pinfunction "2_2") (pintype "passive"))
      (node (ref "IC6") (pin "4") (pinfunction "BYPASS_4") (pintype "passive"))
    )
    (net (code "103") (name "Net-(IC8A-PA4)") (class "Default")
      (node (ref "IC8") (pin "40") (pinfunction "PA4_40") (pintype "bidirectional"))
      (node (ref "RN4") (pin "8") (pinfunction "2_8") (pintype "passive"))
    )
    (net (code "104") (name "Net-(IC8A-PA5)") (class "Default")
      (node (ref "IC8") (pin "41") (pinfunction "PA5_41") (pintype "bidirectional"))
      (node (ref "RN4") (pin "7") (pinfunction "2_7") (pintype "passive"))
    )
    (net (code "105") (name "Net-(IC8A-PA6)") (class "Default")
      (node (ref "IC8") (pin "42") (pinfunction "PA6_42") (pintype "bidirectional"))
      (node (ref "RN4") (pin "6") (pinfunction "2_6") (pintype "passive"))
    )
    (net (code "106") (name "Net-(IC8A-PA7)") (class "Default")
      (node (ref "IC8") (pin "43") (pinfunction "PA7_43") (pintype "bidirectional"))
      (node (ref "RN4") (pin "5") (pinfunction "2_5") (pintype "passive"))
    )
    (net (code "107") (name "Net-(IC8A-PB12)") (class "Default")
      (node (ref "IC8") (pin "73") (pinfunction "PB12_73") (pintype "bidirectional"))
      (node (ref "RN5") (pin "8") (pinfunction "2_8") (pintype "passive"))
    )
    (net (code "108") (name "Net-(IC8A-PB13)") (class "Default")
      (node (ref "IC8") (pin "74") (pinfunction "PB13_74") (pintype "bidirectional"))
      (node (ref "RN5") (pin "7") (pinfunction "2_7") (pintype "passive"))
    )
    (net (code "109") (name "Net-(IC8A-PB14)") (class "Default")
      (node (ref "IC8") (pin "75") (pinfunction "PB14_75") (pintype "bidirectional"))
      (node (ref "RN5") (pin "6") (pinfunction "2_6") (pintype "passive"))
    )
    (net (code "110") (name "Net-(IC8A-PB15)") (class "Default")
      (node (ref "IC8") (pin "76") (pinfunction "PB15_76") (pintype "bidirectional"))
      (node (ref "RN5") (pin "5") (pinfunction "2_5") (pintype "passive"))
    )
    (net (code "111") (name "Net-(IC8B-PH0-OSC_IN)") (class "Default")
      (node (ref "C20") (pin "2") (pinfunction "2_2") (pintype "passive"))
      (node (ref "IC8") (pin "23") (pinfunction "PH0-OSC_IN_23") (pintype "bidirectional"))
      (node (ref "Y1") (pin "2") (pinfunction "2_2") (pintype "passive"))
    )
    (net (code "112") (name "Net-(IC8B-PH1-OSC_OUT)") (class "Default")
      (node (ref "C21") (pin "2") (pinfunction "2_2") (pintype "passive"))
      (node (ref "IC8") (pin "24") (pinfunction "PH1-OSC_OUT_24") (pintype "bidirectional"))
      (node (ref "Y1") (pin "1") (pinfunction "1_1") (pintype "passive"))
    )
    (net (code "113") (name "Net-(IC8C-VCAP_1)") (class "Default")
      (node (ref "C38") (pin "2") (pinfunction "2_2") (pintype "passive"))
      (node (ref "IC8") (pin "71") (pinfunction "VCAP_1_71") (pintype "power_in"))
    )
    (net (code "114") (name "Net-(IC8C-VCAP_2)") (class "Default")
      (node (ref "C37") (pin "2") (pinfunction "2_2") (pintype "passive"))
      (node (ref "IC8") (pin "106") (pinfunction "VCAP_2_106") (pintype "power_in"))
    )
    (net (code "115") (name "Net-(IC8C-VDDA)") (class "Default")
      (node (ref "C35") (pin "1") (pinfunction "1_1") (pintype "passive"))
      (node (ref "C36") (pin "1") (pinfunction "1_1") (pintype "passive"))
      (node (ref "IC8") (pin "33") (pinfunction "VDDA_33") (pintype "power_in"))
      (node (ref "L4") (pin "P$2") (pinfunction "2_P$2") (pintype "passive"))
      (node (ref "R8") (pin "1") (pinfunction "1_1") (pintype "passive"))
    )
    (net (code "116") (name "Net-(IC8C-VREF+)") (class "Default")
      (node (ref "IC8") (pin "32") (pinfunction "VREF+_32") (pintype "power_in"))
      (node (ref "R8") (pin "2") (pinfunction "2_2") (pintype "passive"))
    )
    (net (code "117") (name "Net-(IC9A-+IN)") (class "Default")
      (node (ref "IC9") (pin "3") (pinfunction "+IN_3") (pintype "input"))
      (node (ref "L5") (pin "P$1") (pinfunction "1_P$1") (pintype "passive"))
      (node (ref "R11") (pin "1") (pinfunction "1_1") (pintype "passive"))
      (node (ref "R9") (pin "1") (pinfunction "1_1") (pintype "passive"))
    )
    (net (code "118") (name "Net-(IC9B-+IN)") (class "Default")
      (node (ref "IC9") (pin "5") (pinfunction "+IN_5") (pintype "input"))
      (node (ref "L6") (pin "P$1") (pinfunction "1_P$1") (pintype "passive"))
      (node (ref "R13") (pin "1") (pinfunction "1_1") (pintype "passive"))
      (node (ref "R15") (pin "1") (pinfunction "1_1") (pintype "passive"))
    )
    (net (code "119") (name "Net-(IC10-+VSENSE)") (class "Default")
      (node (ref "IC10") (pin "22") (pinfunction "+VSENSE_22") (pintype "input"))
      (node (ref "IC9") (pin "1") (pinfunction "OUT_1") (pintype "output"))
      (node (ref "IC9") (pin "2") (pinfunction "-IN_2") (pintype "input"))
    )
    (net (code "120") (name "Net-(IC10--VSENSE)") (class "Default")
      (node (ref "IC10") (pin "23") (pinfunction "-VSENSE_23") (pintype "input"))
      (node (ref "IC11") (pin "23") (pinfunction "-VSENSE_23") (pintype "input"))
      (node (ref "SH1") (pin "2") (pinfunction "GND_B_2") (pintype "bidirectional"))
    )
    (net (code "121") (name "Net-(IC10-CMP)") (class "Default")
      (node (ref "C39") (pin "2") (pinfunction "2_2") (pintype "passive"))
      (node (ref "IC10") (pin "17") (pinfunction "CMP_17") (pintype "output"))
    )
    (net (code "122") (name "Net-(IC10-HART-IN)") (class "Default")
      (node (ref "C42") (pin "2") (pinfunction "2_2") (pintype "passive"))
      (node (ref "IC10") (pin "18") (pinfunction "HART-IN_18") (pintype "input"))
    )
    (net (code "123") (name "Net-(IC10-IOUT)") (class "Default")
      (node (ref "IC10") (pin "19") (pinfunction "IOUT_19") (pintype "output"))
      (node (ref "R9") (pin "2") (pinfunction "2_2") (pintype "passive"))
    )
    (net (code "124") (name "Net-(IC10-ISET-R)") (class "Default")
      (node (ref "IC10") (pin "13") (pinfunction "ISET-R_13") (pintype "input"))
      (node (ref "R10") (pin "2") (pinfunction "2_2") (pintype "passive"))
    )
    (net (code "125") (name "Net-(IC10-REFIN)") (class "Default")
      (node (ref "C43") (pin "1") (pinfunction "1_1") (pintype "passive"))
      (node (ref "IC10") (pin "14") (pinfunction "REFOUT_14") (pintype "output"))
      (node (ref "IC10") (pin "15") (pinfunction "REFIN_15") (pintype "input"))
    )
    (net (code "126") (name "Net-(IC10-VOUT)") (class "Default")
      (node (ref "C39") (pin "1") (pinfunction "1_1") (pintype "passive"))
      (node (ref "IC10") (pin "21") (pinfunction "VOUT_21") (pintype "output"))
      (node (ref "R11") (pin "2") (pinfunction "2_2") (pintype "passive"))
    )
    (net (code "127") (name "Net-(IC11-+VSENSE)") (class "Default")
      (node (ref "IC11") (pin "22") (pinfunction "+VSENSE_22") (pintype "input"))
      (node (ref "IC9") (pin "6") (pinfunction "-IN_6") (pintype "input"))
      (node (ref "IC9") (pin "7") (pinfunction "OUT_7") (pintype "output"))
    )
    (net (code "128") (name "Net-(IC11-CMP)") (class "Default")
      (node (ref "C48") (pin "2") (pinfunction "2_2") (pintype "passive"))
      (node (ref "IC11") (pin "17") (pinfunction "CMP_17") (pintype "output"))
    )
    (net (code "129") (name "Net-(IC11-HART-IN)") (class "Default")
      (node (ref "C51") (pin "2") (pinfunction "2_2") (pintype "passive"))
      (node (ref "IC11") (pin "18") (pinfunction "HART-IN_18") (pintype "input"))
    )
    (net (code "130") (name "Net-(IC11-IOUT)") (class "Default")
      (node (ref "IC11") (pin "19") (pinfunction "IOUT_19") (pintype "output"))
      (node (ref "R13") (pin "2") (pinfunction "2_2") (pintype "passive"))
    )
    (net (code "131") (name "Net-(IC11-ISET-R)") (class "Default")
      (node (ref "IC11") (pin "13") (pinfunction "ISET-R_13") (pintype "input"))
      (node (ref "R14") (pin "2") (pinfunction "2_2") (pintype "passive"))
    )
    (net (code "132") (name "Net-(IC11-REFIN)") (class "Default")
      (node (ref "C52") (pin "1") (pinfunction "1_1") (pintype "passive"))
      (node (ref "IC11") (pin "14") (pinfunction "REFOUT_14") (pintype "output"))
      (node (ref "IC11") (pin "15") (pinfunction "REFIN_15") (pintype "input"))
    )
    (net (code "133") (name "Net-(IC11-VOUT)") (class "Default")
      (node (ref "C48") (pin "1") (pinfunction "1_1") (pintype "passive"))
      (node (ref "IC11") (pin "21") (pinfunction "VOUT_21") (pintype "output"))
      (node (ref "R15") (pin "2") (pinfunction "2_2") (pintype "passive"))
    )
    (net (code "134") (name "Net-(IC12A-+IN)") (class "Default")
      (node (ref "IC12") (pin "3") (pinfunction "+IN_3") (pintype "input"))
      (node (ref "R18") (pin "2") (pinfunction "2_2") (pintype "passive"))
      (node (ref "R22") (pin "1") (pinfunction "1_1") (pintype "passive"))
    )
    (net (code "135") (name "Net-(IC12B-V+)") (class "Default")
      (node (ref "C63") (pin "1") (pinfunction "1_1") (pintype "passive"))
      (node (ref "C64") (pin "2") (pinfunction "2_2") (pintype "passive"))
      (node (ref "C65") (pin "1") (pinfunction "1_1") (pintype "passive"))
      (node (ref "IC12") (pin "5") (pinfunction "V+_5") (pintype "power_in"))
      (node (ref "IC13") (pin "9") (pinfunction "VDD_9") (pintype "power_in"))
      (node (ref "L7") (pin "P$1") (pinfunction "1_P$1") (pintype "passive"))
    )
    (net (code "136") (name "Net-(IC13-VOUTA)") (class "Default")
      (node (ref "IC13") (pin "1") (pinfunction "VOUTA_1") (pintype "output"))
      (node (ref "R21") (pin "2") (pinfunction "2_2") (pintype "passive"))
    )
    (net (code "137") (name "Net-(IC13-VOUTB)") (class "Default")
      (node (ref "IC13") (pin "2") (pinfunction "VOUTB_2") (pintype "output"))
      (node (ref "R28") (pin "2") (pinfunction "2_2") (pintype "passive"))
    )
    (net (code "138") (name "Net-(IC13-VREF)") (class "Default")
      (node (ref "C61") (pin "2") (pinfunction "2_2") (pintype "passive"))
      (node (ref "IC13") (pin "10") (pinfunction "VREF_10") (pintype "bidirectional"))
      (node (ref "R18") (pin "1") (pinfunction "1_1") (pintype "passive"))
    )
    (net (code "139") (name "Net-(IC14A-+IN)") (class "Default")
      (node (ref "IC14") (pin "3") (pinfunction "+IN_3") (pintype "input"))
      (node (ref "R28") (pin "1") (pinfunction "1_1") (pintype "passive"))
      (node (ref "R29") (pin "1") (pinfunction "1_1") (pintype "passive"))
    )
    (net (code "140") (name "Net-(IC14A--IN)") (class "Default")
      (node (ref "IC14") (pin "2") (pinfunction "-IN_2") (pintype "input"))
      (node (ref "R24") (pin "1") (pinfunction "1_1") (pintype "passive"))
      (node (ref "R25") (pin "2") (pinfunction "2_2") (pintype "passive"))
    )
    (net (code "141") (name "Net-(IC14A-OUT)") (class "Default")
      (node (ref "IC14") (pin "1") (pinfunction "OUT_1") (pintype "output"))
      (node (ref "R26") (pin "1") (pinfunction "1_1") (pintype "passive"))
    )
    (net (code "142") (name "Net-(IC14B-+IN)") (class "Default")
      (node (ref "IC14") (pin "5") (pinfunction "+IN_5") (pintype "input"))
      (node (ref "R21") (pin "1") (pinfunction "1_1") (pintype "passive"))
      (node (ref "R23") (pin "1") (pinfunction "1_1") (pintype "passive"))
    )
    (net (code "143") (name "Net-(IC14B--IN)") (class "Default")
      (node (ref "IC14") (pin "6") (pinfunction "-IN_6") (pintype "input"))
      (node (ref "R16") (pin "1") (pinfunction "1_1") (pintype "passive"))
      (node (ref "R17") (pin "2") (pinfunction "2_2") (pintype "passive"))
    )
    (net (code "144") (name "Net-(IC14B-OUT)") (class "Default")
      (node (ref "IC14") (pin "7") (pinfunction "OUT_7") (pintype "output"))
      (node (ref "R19") (pin "1") (pinfunction "1_1") (pintype "passive"))
    )
    (net (code "145") (name "Net-(IC15-GND)") (class "Default")
      (node (ref "IC15") (pin "6") (pinfunction "GND_6") (pintype "passive"))
      (node (ref "IC16") (pin "6") (pinfunction "GND_6") (pintype "passive"))
      (node (ref "IC17") (pin "6") (pinfunction "GND_6") (pintype "passive"))
      (node (ref "IC18") (pin "6") (pinfunction "GND_6") (pintype "passive"))
      (node (ref "SH2") (pin "2") (pinfunction "GND_B_2") (pintype "bidirectional"))
    )
    (net (code "146") (name "Net-(IC20-R)") (class "Default")
      (node (ref "IC20") (pin "2") (pinfunction "R_2") (pintype "passive"))
      (node (ref "R34") (pin "2") (pinfunction "2_2") (pintype "passive"))
      (node (ref "R35") (pin "1") (pinfunction "1_1") (pintype "passive"))
    )
    (net (code "147") (name "Net-(IC21B-COM)") (class "Default")
      (node (ref "IC21") (pin "6") (pinfunction "COM_6") (pintype "bidirectional"))
      (node (ref "IC26") (pin "6") (pinfunction "COM_6") (pintype "bidirectional"))
      (node (ref "JP6") (pin "COM") (pinfunction "COM_COM") (pintype "passive"))
    )
    (net (code "148") (name "Net-(IC21B-NO)") (class "Default")
      (node (ref "IC21") (pin "1") (pinfunction "NO_1") (pintype "bidirectional"))
      (node (ref "R62") (pin "1") (pinfunction "1_1") (pintype "passive"))
    )
    (net (code "149") (name "Net-(IC22B-COM)") (class "Default")
      (node (ref "IC22") (pin "6") (pinfunction "COM_6") (pintype "bidirectional"))
      (node (ref "IC31") (pin "6") (pinfunction "COM_6") (pintype "bidirectional"))
      (node (ref "R67") (pin "1") (pinfunction "1_1") (pintype "passive"))
    )
    (net (code "150") (name "Net-(IC22B-NO)") (class "Default")
      (node (ref "IC22") (pin "1") (pinfunction "NO_1") (pintype "bidirectional"))
      (node (ref "IC27") (pin "6") (pinfunction "COM_6") (pintype "bidirectional"))
      (node (ref "R70") (pin "2") (pinfunction "2_2") (pintype "passive"))
    )
    (net (code "151") (name "Net-(IC23B-COM)") (class "Default")
      (node (ref "IC23") (pin "6") (pinfunction "COM_6") (pintype "bidirectional"))
      (node (ref "IC32") (pin "6") (pinfunction "COM_6") (pintype "bidirectional"))
      (node (ref "R73") (pin "1") (pinfunction "1_1") (pintype "passive"))
    )
    (net (code "152") (name "Net-(IC23B-NO)") (class "Default")
      (node (ref "IC23") (pin "1") (pinfunction "NO_1") (pintype "bidirectional"))
      (node (ref "IC28") (pin "6") (pinfunction "COM_6") (pintype "bidirectional"))
      (node (ref "R74") (pin "2") (pinfunction "2_2") (pintype "passive"))
    )
    (net (code "153") (name "Net-(IC24B-COM)") (class "Default")
      (node (ref "IC24") (pin "6") (pinfunction "COM_6") (pintype "bidirectional"))
      (node (ref "IC33") (pin "6") (pinfunction "COM_6") (pintype "bidirectional"))
      (node (ref "JP9") (pin "2") (pinfunction "2_2") (pintype "passive"))
      (node (ref "R77") (pin "1") (pinfunction "1_1") (pintype "passive"))
    )
    (net (code "154") (name "Net-(IC24B-NO)") (class "Default")
      (node (ref "IC24") (pin "1") (pinfunction "NO_1") (pintype "bidirectional"))
      (node (ref "IC29") (pin "6") (pinfunction "COM_6") (pintype "bidirectional"))
      (node (ref "R78") (pin "2") (pinfunction "2_2") (pintype "passive"))
    )
    (net (code "155") (name "Net-(IC25B-COM)") (class "Default")
      (node (ref "IC25") (pin "6") (pinfunction "COM_6") (pintype "bidirectional"))
      (node (ref "IC34") (pin "6") (pinfunction "COM_6") (pintype "bidirectional"))
      (node (ref "JP11") (pin "2") (pinfunction "2_2") (pintype "passive"))
      (node (ref "R81") (pin "1") (pinfunction "1_1") (pintype "passive"))
    )
    (net (code "156") (name "Net-(IC25B-NO)") (class "Default")
      (node (ref "IC25") (pin "1") (pinfunction "NO_1") (pintype "bidirectional"))
      (node (ref "IC30") (pin "6") (pinfunction "COM_6") (pintype "bidirectional"))
      (node (ref "R82") (pin "2") (pinfunction "2_2") (pintype "passive"))
    )
    (net (code "157") (name "Net-(IC26B-NO)") (class "Default")
      (node (ref "IC26") (pin "1") (pinfunction "NO_1") (pintype "bidirectional"))
      (node (ref "R63") (pin "1") (pinfunction "1_1") (pintype "passive"))
    )
    (net (code "158") (name "Net-(IC27B-NO)") (class "Default")
      (node (ref "IC27") (pin "1") (pinfunction "NO_1") (pintype "bidirectional"))
      (node (ref "IC31") (pin "1") (pinfunction "NO_1") (pintype "bidirectional"))
      (node (ref "Q7") (pin "3") (pinfunction "D_3") (pintype "passive"))
    )
    (net (code "159") (name "Net-(IC28B-NO)") (class "Default")
      (node (ref "IC28") (pin "1") (pinfunction "NO_1") (pintype "bidirectional"))
      (node (ref "IC32") (pin "1") (pinfunction "NO_1") (pintype "bidirectional"))
      (node (ref "Q9") (pin "3") (pinfunction "D_3") (pintype "passive"))
    )
    (net (code "160") (name "Net-(IC29B-NO)") (class "Default")
      (node (ref "IC29") (pin "1") (pinfunction "NO_1") (pintype "bidirectional"))
      (node (ref "IC33") (pin "1") (pinfunction "NO_1") (pintype "bidirectional"))
      (node (ref "Q11") (pin "3") (pinfunction "D_3") (pintype "passive"))
    )
    (net (code "161") (name "Net-(IC30B-NO)") (class "Default")
      (node (ref "IC30") (pin "1") (pinfunction "NO_1") (pintype "bidirectional"))
      (node (ref "IC34") (pin "1") (pinfunction "NO_1") (pintype "bidirectional"))
      (node (ref "Q13") (pin "3") (pinfunction "D_3") (pintype "passive"))
    )
    (net (code "162") (name "Net-(IC35A--IN)") (class "Default")
      (node (ref "IC35") (pin "1") (pinfunction "OUT_1") (pintype "output"))
      (node (ref "IC35") (pin "4") (pinfunction "-IN_4") (pintype "input"))
      (node (ref "JP6") (pin "NC") (pinfunction "NC_NC") (pintype "passive"))
    )
    (net (code "163") (name "Net-(IC36-REFCAP)") (class "Default")
      (node (ref "C93") (pin "2") (pinfunction "2_2") (pintype "passive"))
      (node (ref "C94") (pin "2") (pinfunction "2_2") (pintype "passive"))
      (node (ref "IC36") (pin "7") (pinfunction "REFCAP_7") (pintype "output"))
    )
    (net (code "164") (name "Net-(JP4-Pad2)") (class "Default")
      (node (ref "JP4") (pin "2") (pinfunction "2_2") (pintype "passive"))
      (node (ref "R31") (pin "1") (pinfunction "1_1") (pintype "passive"))
    )
    (net (code "165") (name "Net-(JP5-Pad2)") (class "Default")
      (node (ref "JP5") (pin "2") (pinfunction "2_2") (pintype "passive"))
      (node (ref "R32") (pin "1") (pinfunction "1_1") (pintype "passive"))
    )
    (net (code "166") (name "Net-(L8-1)") (class "Default")
      (node (ref "L8") (pin "P$1") (pinfunction "1_P$1") (pintype "passive"))
      (node (ref "X4") (pin "1") (pinfunction "1_1") (pintype "passive"))
      (node (ref "X6") (pin "1") (pinfunction "1_1") (pintype "passive"))
    )
    (net (code "167") (name "Net-(L8-2)") (class "Default")
      (node (ref "L8") (pin "P$2") (pinfunction "2_P$2") (pintype "passive"))
      (node (ref "Q6") (pin "3") (pinfunction "D_3") (pintype "passive"))
      (node (ref "R62") (pin "2") (pinfunction "2_2") (pintype "passive"))
      (node (ref "TVS5") (pin "C2") (pinfunction "2_C2") (pintype "passive"))
    )
    (net (code "168") (name "Net-(L9-1)") (class "Default")
      (node (ref "L9") (pin "P$1") (pinfunction "1_P$1") (pintype "passive"))
      (node (ref "X4") (pin "3") (pinfunction "1_3") (pintype "passive"))
      (node (ref "X6") (pin "5") (pinfunction "1_5") (pintype "passive"))
    )
    (net (code "169") (name "Net-(L9-2)") (class "Default")
      (node (ref "L9") (pin "P$2") (pinfunction "2_P$2") (pintype "passive"))
      (node (ref "Q8") (pin "3") (pinfunction "D_3") (pintype "passive"))
      (node (ref "R63") (pin "2") (pinfunction "2_2") (pintype "passive"))
      (node (ref "TVS6") (pin "C2") (pinfunction "2_C2") (pintype "passive"))
    )
    (net (code "170") (name "Net-(L10-1)") (class "Default")
      (node (ref "L10") (pin "P$1") (pinfunction "1_P$1") (pintype "passive"))
      (node (ref "X4") (pin "5") (pinfunction "1_5") (pintype "passive"))
      (node (ref "X6") (pin "7") (pinfunction "1_7") (pintype "passive"))
    )
    (net (code "171") (name "Net-(L10-2)") (class "Default")
      (node (ref "JP9") (pin "1") (pinfunction "1_1") (pintype "passive"))
      (node (ref "L10") (pin "P$2") (pinfunction "2_P$2") (pintype "passive"))
      (node (ref "Q10") (pin "3") (pinfunction "D_3") (pintype "passive"))
      (node (ref "TVS7") (pin "C2") (pinfunction "2_C2") (pintype "passive"))
    )
    (net (code "172") (name "Net-(L12-1)") (class "Default")
      (node (ref "L12") (pin "P$1") (pinfunction "1_P$1") (pintype "passive"))
      (node (ref "X4") (pin "7") (pinfunction "1_7") (pintype "passive"))
      (node (ref "X6") (pin "9") (pinfunction "1_9") (pintype "passive"))
    )
    (net (code "173") (name "Net-(L12-2)") (class "Default")
      (node (ref "JP11") (pin "1") (pinfunction "1_1") (pintype "passive"))
      (node (ref "L12") (pin "P$2") (pinfunction "2_P$2") (pintype "passive"))
      (node (ref "Q12") (pin "3") (pinfunction "D_3") (pintype "passive"))
      (node (ref "TVS8") (pin "C2") (pinfunction "2_C2") (pintype "passive"))
    )
    (net (code "174") (name "Net-(Q1A-D)") (class "Default")
      (node (ref "C81") (pin "2") (pinfunction "2_2") (pintype "passive"))
      (node (ref "Q1") (pin "6") (pinfunction "D_6") (pintype "passive"))
    )
    (net (code "175") (name "Net-(Q1B-D)") (class "Default")
      (node (ref "C82") (pin "2") (pinfunction "2_2") (pintype "passive"))
      (node (ref "Q1") (pin "3") (pinfunction "D_3") (pintype "passive"))
    )
    (net (code "176") (name "Net-(Q2A-D)") (class "Default")
      (node (ref "Q2") (pin "6") (pinfunction "D_6") (pintype "passive"))
      (node (ref "R52") (pin "2") (pinfunction "2_2") (pintype "passive"))
    )
    (net (code "177") (name "Net-(Q2B-D)") (class "Default")
      (node (ref "Q2") (pin "3") (pinfunction "D_3") (pintype "passive"))
      (node (ref "R53") (pin "2") (pinfunction "2_2") (pintype "passive"))
    )
    (net (code "178") (name "Net-(Q3A-D)") (class "Default")
      (node (ref "Q3") (pin "6") (pinfunction "D_6") (pintype "passive"))
      (node (ref "R54") (pin "2") (pinfunction "2_2") (pintype "passive"))
    )
    (net (code "179") (name "Net-(Q3B-D)") (class "Default")
      (node (ref "Q3") (pin "3") (pinfunction "D_3") (pintype "passive"))
      (node (ref "R55") (pin "2") (pinfunction "2_2") (pintype "passive"))
    )
    (net (code "180") (name "Net-(Q4A-D)") (class "Default")
      (node (ref "Q4") (pin "6") (pinfunction "D_6") (pintype "passive"))
      (node (ref "R56") (pin "2") (pinfunction "2_2") (pintype "passive"))
    )
    (net (code "181") (name "Net-(Q4B-D)") (class "Default")
      (node (ref "Q4") (pin "3") (pinfunction "D_3") (pintype "passive"))
      (node (ref "R57") (pin "2") (pinfunction "2_2") (pintype "passive"))
    )
    (net (code "182") (name "Net-(Q5A-D)") (class "Default")
      (node (ref "Q5") (pin "6") (pinfunction "D_6") (pintype "passive"))
      (node (ref "R58") (pin "2") (pinfunction "2_2") (pintype "passive"))
    )
    (net (code "183") (name "Net-(Q5B-D)") (class "Default")
      (node (ref "Q5") (pin "3") (pinfunction "D_3") (pintype "passive"))
      (node (ref "R59") (pin "2") (pinfunction "2_2") (pintype "passive"))
    )
    (net (code "184") (name "Net-(Q6-G)") (class "Default")
      (node (ref "Q6") (pin "1") (pinfunction "G_1") (pintype "passive"))
      (node (ref "Q7") (pin "2") (pinfunction "S_2") (pintype "passive"))
      (node (ref "R66") (pin "1") (pinfunction "1_1") (pintype "passive"))
    )
    (net (code "185") (name "Net-(Q6-S)") (class "Default")
      (node (ref "Q6") (pin "2") (pinfunction "S_2") (pintype "passive"))
      (node (ref "Q7") (pin "1") (pinfunction "G_1") (pintype "passive"))
      (node (ref "R66") (pin "2") (pinfunction "2_2") (pintype "passive"))
    )
    (net (code "186") (name "Net-(Q8-G)") (class "Default")
      (node (ref "Q8") (pin "1") (pinfunction "G_1") (pintype "passive"))
      (node (ref "Q9") (pin "2") (pinfunction "S_2") (pintype "passive"))
      (node (ref "R72") (pin "1") (pinfunction "1_1") (pintype "passive"))
    )
    (net (code "187") (name "Net-(Q8-S)") (class "Default")
      (node (ref "Q8") (pin "2") (pinfunction "S_2") (pintype "passive"))
      (node (ref "Q9") (pin "1") (pinfunction "G_1") (pintype "passive"))
      (node (ref "R72") (pin "2") (pinfunction "2_2") (pintype "passive"))
    )
    (net (code "188") (name "Net-(Q10-G)") (class "Default")
      (node (ref "Q10") (pin "1") (pinfunction "G_1") (pintype "passive"))
      (node (ref "Q11") (pin "2") (pinfunction "S_2") (pintype "passive"))
      (node (ref "R76") (pin "1") (pinfunction "1_1") (pintype "passive"))
    )
    (net (code "189") (name "Net-(Q10-S)") (class "Default")
      (node (ref "Q10") (pin "2") (pinfunction "S_2") (pintype "passive"))
      (node (ref "Q11") (pin "1") (pinfunction "G_1") (pintype "passive"))
      (node (ref "R76") (pin "2") (pinfunction "2_2") (pintype "passive"))
    )
    (net (code "190") (name "Net-(Q12-G)") (class "Default")
      (node (ref "Q12") (pin "1") (pinfunction "G_1") (pintype "passive"))
      (node (ref "Q13") (pin "2") (pinfunction "S_2") (pintype "passive"))
      (node (ref "R80") (pin "1") (pinfunction "1_1") (pintype "passive"))
    )
    (net (code "191") (name "Net-(Q12-S)") (class "Default")
      (node (ref "Q12") (pin "2") (pinfunction "S_2") (pintype "passive"))
      (node (ref "Q13") (pin "1") (pinfunction "G_1") (pintype "passive"))
      (node (ref "R80") (pin "2") (pinfunction "2_2") (pintype "passive"))
    )
    (net (code "192") (name "Net-(R60-Pad2)") (class "Default")
      (node (ref "R60") (pin "2") (pinfunction "2_2") (pintype "passive"))
      (node (ref "R61") (pin "1") (pinfunction "1_1") (pintype "passive"))
    )
    (net (code "193") (name "Net-(RN2A-2)") (class "Default")
      (node (ref "RN2") (pin "8") (pinfunction "2_8") (pintype "passive"))
      (node (ref "X1") (pin "14") (pinfunction "1_14") (pintype "passive"))
    )
    (net (code "194") (name "Net-(RN2B-2)") (class "Default")
      (node (ref "RN2") (pin "7") (pinfunction "2_7") (pintype "passive"))
      (node (ref "X1") (pin "9") (pinfunction "1_9") (pintype "passive"))
    )
    (net (code "195") (name "Net-(RN2C-2)") (class "Default")
      (node (ref "RN2") (pin "6") (pinfunction "2_6") (pintype "passive"))
      (node (ref "X1") (pin "13") (pinfunction "1_13") (pintype "passive"))
    )
    (net (code "196") (name "Net-(RN2D-2)") (class "Default")
      (node (ref "RN2") (pin "5") (pinfunction "2_5") (pintype "passive"))
      (node (ref "X1") (pin "15") (pinfunction "1_15") (pintype "passive"))
    )
    (net (code "197") (name "Net-(TR1-COMM)") (class "Default")
      (node (ref "C12") (pin "2") (pinfunction "2_2") (pintype "passive"))
      (node (ref "C18") (pin "2") (pinfunction "2_2") (pintype "passive"))
      (node (ref "C6") (pin "2") (pinfunction "2_2") (pintype "passive"))
      (node (ref "C9") (pin "1") (pinfunction "1_1") (pintype "passive"))
      (node (ref "L2") (pin "4") (pinfunction "4_4") (pintype "passive"))
      (node (ref "L3") (pin "1") (pinfunction "1_1") (pintype "passive"))
      (node (ref "TR1") (pin "5") (pinfunction "COMM_5") (pintype "passive"))
      (node (ref "TR2") (pin "6") (pinfunction "COMM_6") (pintype "passive"))
    )
    (net (code "198") (name "Net-(TR1-IN+)") (class "Default")
      (node (ref "C6") (pin "1") (pinfunction "1_1") (pintype "passive"))
      (node (ref "C8") (pin "2") (pinfunction "2_2") (pintype "passive"))
      (node (ref "L1") (pin "3") (pinfunction "3_3") (pintype "passive"))
      (node (ref "TR1") (pin "1") (pinfunction "IN+_1") (pintype "input"))
      (node (ref "TR2") (pin "1") (pinfunction "IN+_1") (pintype "input"))
    )
    (net (code "199") (name "Net-(TR1-IN-)") (class "Default")
      (node (ref "C12") (pin "1") (pinfunction "1_1") (pintype "passive"))
      (node (ref "C8") (pin "1") (pinfunction "1_1") (pintype "passive"))
      (node (ref "L1") (pin "2") (pinfunction "2_2") (pintype "passive"))
      (node (ref "TR1") (pin "2") (pinfunction "IN-_2") (pintype "input"))
      (node (ref "TR2") (pin "2") (pinfunction "IN-_2") (pintype "input"))
    )
    (net (code "200") (name "Net-(TR1-OUT+)") (class "Default")
      (node (ref "C9") (pin "2") (pinfunction "2_2") (pintype "passive"))
      (node (ref "L2") (pin "1") (pinfunction "1_1") (pintype "passive"))
      (node (ref "TR1") (pin "6") (pinfunction "OUT+_6") (pintype "passive"))
      (node (ref "TR2") (pin "7") (pinfunction "OUT+_7") (pintype "passive"))
    )
    (net (code "201") (name "Net-(TR1-OUT-)") (class "Default")
      (node (ref "C18") (pin "1") (pinfunction "1_1") (pintype "passive"))
      (node (ref "L3") (pin "4") (pinfunction "4_4") (pintype "passive"))
      (node (ref "TR1") (pin "4") (pinfunction "OUT-_4") (pintype "passive"))
      (node (ref "TR2") (pin "5") (pinfunction "OUT-_5") (pintype "passive"))
    )
    (net (code "202") (name "Net-(TVS3-2)") (class "Default")
      (node (ref "R19") (pin "2") (pinfunction "2_2") (pintype "passive"))
      (node (ref "R20") (pin "1") (pinfunction "1_1") (pintype "passive"))
      (node (ref "TVS3") (pin "C2") (pinfunction "2_C2") (pintype "passive"))
    )
    (net (code "203") (name "Net-(TVS4-2)") (class "Default")
      (node (ref "R26") (pin "2") (pinfunction "2_2") (pintype "passive"))
      (node (ref "R27") (pin "1") (pinfunction "1_1") (pintype "passive"))
      (node (ref "TVS4") (pin "C2") (pinfunction "2_C2") (pintype "passive"))
    )
    (net (code "204") (name "Net-(TVS5-1)") (class "Default")
      (node (ref "JP7") (pin "1") (pinfunction "1_1") (pintype "passive"))
      (node (ref "R70") (pin "1") (pinfunction "1_1") (pintype "passive"))
      (node (ref "R71") (pin "1") (pinfunction "1_1") (pintype "passive"))
      (node (ref "TVS5") (pin "C1") (pinfunction "1_C1") (pintype "passive"))
      (node (ref "X4") (pin "2") (pinfunction "1_2") (pintype "passive"))
      (node (ref "X6") (pin "2") (pinfunction "1_2") (pintype "passive"))
    )
    (net (code "205") (name "Net-(TVS6-1)") (class "Default")
      (node (ref "JP8") (pin "1") (pinfunction "1_1") (pintype "passive"))
      (node (ref "R74") (pin "1") (pinfunction "1_1") (pintype "passive"))
      (node (ref "R75") (pin "1") (pinfunction "1_1") (pintype "passive"))
      (node (ref "TVS6") (pin "C1") (pinfunction "1_C1") (pintype "passive"))
      (node (ref "X4") (pin "4") (pinfunction "1_4") (pintype "passive"))
      (node (ref "X6") (pin "6") (pinfunction "1_6") (pintype "passive"))
    )
    (net (code "206") (name "Net-(TVS7-1)") (class "Default")
      (node (ref "JP10") (pin "1") (pinfunction "1_1") (pintype "passive"))
      (node (ref "R78") (pin "1") (pinfunction "1_1") (pintype "passive"))
      (node (ref "R79") (pin "1") (pinfunction "1_1") (pintype "passive"))
      (node (ref "TVS7") (pin "C1") (pinfunction "1_C1") (pintype "passive"))
      (node (ref "X4") (pin "6") (pinfunction "1_6") (pintype "passive"))
      (node (ref "X6") (pin "8") (pinfunction "1_8") (pintype "passive"))
    )
    (net (code "207") (name "Net-(TVS8-1)") (class "Default")
      (node (ref "JP12") (pin "1") (pinfunction "1_1") (pintype "passive"))
      (node (ref "R82") (pin "1") (pinfunction "1_1") (pintype "passive"))
      (node (ref "R83") (pin "1") (pinfunction "1_1") (pintype "passive"))
      (node (ref "TVS8") (pin "C1") (pinfunction "1_C1") (pintype "passive"))
      (node (ref "X4") (pin "8") (pinfunction "1_8") (pintype "passive"))
      (node (ref "X6") (pin "10") (pinfunction "1_10") (pintype "passive"))
    )
    (net (code "208") (name "Net-(X3M-1)") (class "Default")
      (node (ref "R31") (pin "2") (pinfunction "2_2") (pintype "passive"))
      (node (ref "X3") (pin "6") (pinfunction "1_6") (pintype "passive"))
    )
    (net (code "209") (name "Net-(X3N-1)") (class "Default")
      (node (ref "R32") (pin "2") (pinfunction "2_2") (pintype "passive"))
      (node (ref "X3") (pin "7") (pinfunction "1_7") (pintype "passive"))
    )
    (net (code "210") (name "Net-(X4B-1)") (class "Default")
      (node (ref "R37") (pin "1") (pinfunction "1_1") (pintype "passive"))
      (node (ref "X4") (pin "10") (pinfunction "1_10") (pintype "passive"))
    )
    (net (code "211") (name "Net-(X4C-1)") (class "Default")
      (node (ref "R38") (pin "1") (pinfunction "1_1") (pintype "passive"))
      (node (ref "X4") (pin "11") (pinfunction "1_11") (pintype "passive"))
    )
    (net (code "212") (name "Net-(X4D-1)") (class "Default")
      (node (ref "R39") (pin "1") (pinfunction "1_1") (pintype "passive"))
      (node (ref "X4") (pin "12") (pinfunction "1_12") (pintype "passive"))
    )
    (net (code "213") (name "Net-(X4E-1)") (class "Default")
      (node (ref "R40") (pin "1") (pinfunction "1_1") (pintype "passive"))
      (node (ref "X4") (pin "13") (pinfunction "1_13") (pintype "passive"))
    )
    (net (code "214") (name "Net-(X4F-1)") (class "Default")
      (node (ref "R41") (pin "1") (pinfunction "1_1") (pintype "passive"))
      (node (ref "X4") (pin "14") (pinfunction "1_14") (pintype "passive"))
    )
    (net (code "215") (name "Net-(X4G-1)") (class "Default")
      (node (ref "R42") (pin "1") (pinfunction "1_1") (pintype "passive"))
      (node (ref "X4") (pin "15") (pinfunction "1_15") (pintype "passive"))
    )
    (net (code "216") (name "Net-(X4H-1)") (class "Default")
      (node (ref "R43") (pin "1") (pinfunction "1_1") (pintype "passive"))
      (node (ref "X4") (pin "16") (pinfunction "1_16") (pintype "passive"))
    )
    (net (code "217") (name "Net-(X4P-1)") (class "Default")
      (node (ref "R36") (pin "1") (pinfunction "1_1") (pintype "passive"))
      (node (ref "X4") (pin "9") (pinfunction "1_9") (pintype "passive"))
    )
    (net (code "218") (name "OE_SYNC") (class "Default")
      (node (ref "IC3") (pin "3") (pinfunction "A1_3") (pintype "input"))
      (node (ref "X1") (pin "6") (pinfunction "1_6") (pintype "passive"))
    )
    (net (code "219") (name "OUT_EN") (class "Default")
      (node (ref "IC15") (pin "4") (pinfunction "ENA_4") (pintype "input"))
      (node (ref "IC16") (pin "4") (pinfunction "ENA_4") (pintype "input"))
      (node (ref "IC17") (pin "4") (pinfunction "ENA_4") (pintype "input"))
      (node (ref "IC18") (pin "4") (pinfunction "ENA_4") (pintype "input"))
      (node (ref "IC19") (pin "1") (pinfunction "EN_1") (pintype "input"))
      (node (ref "IC19") (pin "10") (pinfunction "EN_10") (pintype "input"))
      (node (ref "IC19") (pin "13") (pinfunction "EN_13") (pintype "input"))
      (node (ref "IC19") (pin "4") (pinfunction "EN_4") (pintype "input"))
      (node (ref "IC8") (pin "70") (pinfunction "PB11_70") (pintype "bidirectional"))
    )
    (net (code "220") (name "PE") (class "Default")
      (node (ref "C89") (pin "1") (pinfunction "1_1") (pintype "passive"))
      (node (ref "J1") (pin "1") (pinfunction "P$1_1") (pintype "bidirectional"))
      (node (ref "J1") (pin "2") (pinfunction "P$1_2") (pintype "bidirectional"))
      (node (ref "R60") (pin "1") (pinfunction "1_1") (pintype "passive"))
    )
    (net (code "221") (name "POUT0") (class "Default")
      (node (ref "IC18") (pin "7") (pinfunction "OUT1_7") (pintype "output"))
      (node (ref "X3") (pin "9") (pinfunction "1_9") (pintype "passive"))
    )
    (net (code "222") (name "POUT1") (class "Default")
      (node (ref "IC18") (pin "5") (pinfunction "OUT2_5") (pintype "output"))
      (node (ref "X3") (pin "10") (pinfunction "1_10") (pintype "passive"))
    )
    (net (code "223") (name "POUT2") (class "Default")
      (node (ref "IC17") (pin "7") (pinfunction "OUT1_7") (pintype "output"))
      (node (ref "X3") (pin "11") (pinfunction "1_11") (pintype "passive"))
    )
    (net (code "224") (name "POUT3") (class "Default")
      (node (ref "IC17") (pin "5") (pinfunction "OUT2_5") (pintype "output"))
      (node (ref "X3") (pin "12") (pinfunction "1_12") (pintype "passive"))
    )
    (net (code "225") (name "POUT4") (class "Default")
      (node (ref "IC16") (pin "7") (pinfunction "OUT1_7") (pintype "output"))
      (node (ref "X3") (pin "13") (pinfunction "1_13") (pintype "passive"))
    )
    (net (code "226") (name "POUT5") (class "Default")
      (node (ref "IC16") (pin "5") (pinfunction "OUT2_5") (pintype "output"))
      (node (ref "X3") (pin "14") (pinfunction "1_14") (pintype "passive"))
    )
    (net (code "227") (name "POUT6") (class "Default")
      (node (ref "IC15") (pin "7") (pinfunction "OUT1_7") (pintype "output"))
      (node (ref "X3") (pin "15") (pinfunction "1_15") (pintype "passive"))
    )
    (net (code "228") (name "POUT7") (class "Default")
      (node (ref "IC15") (pin "5") (pinfunction "OUT2_5") (pintype "output"))
      (node (ref "X3") (pin "16") (pinfunction "1_16") (pintype "passive"))
    )
    (net (code "229") (name "PWM#1") (class "Default")
      (node (ref "IC19") (pin "2") (pinfunction "I_2") (pintype "input"))
      (node (ref "IC19") (pin "5") (pinfunction "I_5") (pintype "input"))
      (node (ref "IC8") (pin "81") (pinfunction "PD12_81") (pintype "bidirectional"))
    )
    (net (code "230") (name "PWM#2") (class "Default")
      (node (ref "IC19") (pin "12") (pinfunction "I_12") (pintype "input"))
      (node (ref "IC19") (pin "9") (pinfunction "I_9") (pintype "input"))
      (node (ref "IC8") (pin "37") (pinfunction "PA3_37") (pintype "bidirectional"))
    )
    (net (code "231") (name "SCLK") (class "Default")
      (node (ref "IC8") (pin "65") (pinfunction "PE12_65") (pintype "bidirectional"))
      (node (ref "RN1") (pin "7") (pinfunction "2_7") (pintype "passive"))
    )
    (net (code "232") (name "SDIO_CLK") (class "Default")
      (node (ref "IC8") (pin "113") (pinfunction "PC12_113") (pintype "bidirectional"))
      (node (ref "J2") (pin "5") (pinfunction "CLK_5") (pintype "passive"))
    )
    (net (code "233") (name "SDIO_CMD") (class "Default")
      (node (ref "IC8") (pin "116") (pinfunction "PD2_116") (pintype "bidirectional"))
      (node (ref "J2") (pin "3") (pinfunction "CMD_3") (pintype "passive"))
      (node (ref "R4") (pin "2") (pinfunction "2_2") (pintype "passive"))
    )
    (net (code "234") (name "SDIO_D0") (class "Default")
      (node (ref "IC8") (pin "98") (pinfunction "PC8_98") (pintype "bidirectional"))
      (node (ref "J2") (pin "7") (pinfunction "DAT0_7") (pintype "passive"))
      (node (ref "R2") (pin "2") (pinfunction "2_2") (pintype "passive"))
    )
    (net (code "235") (name "SDIO_D1") (class "Default")
      (node (ref "IC8") (pin "99") (pinfunction "PC9_99") (pintype "bidirectional"))
      (node (ref "J2") (pin "8") (pinfunction "DAT1_8") (pintype "passive"))
      (node (ref "R5") (pin "2") (pinfunction "2_2") (pintype "passive"))
    )
    (net (code "236") (name "SDIO_D2") (class "Default")
      (node (ref "IC8") (pin "111") (pinfunction "PC10_111") (pintype "bidirectional"))
      (node (ref "J2") (pin "1") (pinfunction "DAT2_1") (pintype "passive"))
      (node (ref "R3") (pin "2") (pinfunction "2_2") (pintype "passive"))
    )
    (net (code "237") (name "SDIO_D3") (class "Default")
      (node (ref "IC8") (pin "112") (pinfunction "PC11_112") (pintype "bidirectional"))
      (node (ref "J2") (pin "2") (pinfunction "CD/DAT3_2") (pintype "passive"))
      (node (ref "R1") (pin "2") (pinfunction "2_2") (pintype "passive"))
    )
    (net (code "238") (name "SD_DETECT") (class "Default")
      (node (ref "IC8") (pin "110") (pinfunction "PA15_110") (pintype "bidirectional"))
      (node (ref "J2") (pin "SW1") (pinfunction "SW1_SW1") (pintype "passive"))
    )
    (net (code "239") (name "SLOW_DIN#0") (class "Default")
      (node (ref "IC8") (pin "139") (pinfunction "PB8_139") (pintype "bidirectional"))
      (node (ref "Q1") (pin "2") (pinfunction "G_2") (pintype "passive"))
    )
    (net (code "240") (name "SLOW_DIN#1") (class "Default")
      (node (ref "IC8") (pin "140") (pinfunction "PB9_140") (pintype "bidirectional"))
      (node (ref "Q1") (pin "5") (pinfunction "G_5") (pintype "passive"))
    )
    (net (code "241") (name "SWCLK") (class "Default")
      (node (ref "IC8") (pin "109") (pinfunction "PA14_109") (pintype "bidirectional"))
      (node (ref "X2") (pin "2") (pinfunction "1_2") (pintype "passive"))
    )
    (net (code "242") (name "SWDIO") (class "Default")
      (node (ref "IC8") (pin "105") (pinfunction "PA13_105") (pintype "bidirectional"))
      (node (ref "X2") (pin "4") (pinfunction "1_4") (pintype "passive"))
    )
    (net (code "243") (name "SYNC") (class "Default")
      (node (ref "IC3") (pin "14") (pinfunction "B1_14") (pintype "output"))
      (node (ref "IC8") (pin "80") (pinfunction "PD11_80") (pintype "bidirectional"))
    )
    (net (code "244") (name "TEMP_SW#1") (class "Default")
      (node (ref "IC21") (pin "3") (pinfunction "IN_3") (pintype "input"))
      (node (ref "IC8") (pin "7") (pinfunction "PC13_7") (pintype "bidirectional"))
    )
    (net (code "245") (name "TEMP_SW#2") (class "Default")
      (node (ref "IC26") (pin "3") (pinfunction "IN_3") (pintype "input"))
      (node (ref "IC8") (pin "8") (pinfunction "PC14-OSC32_IN_8") (pintype "bidirectional"))
    )
    (net (code "246") (name "VOLT_SW0") (class "Default")
      (node (ref "IC31") (pin "3") (pinfunction "IN_3") (pintype "input"))
      (node (ref "IC8") (pin "10") (pinfunction "PF0_10") (pintype "bidirectional"))
    )
    (net (code "247") (name "VOLT_SW1") (class "Default")
      (node (ref "IC32") (pin "3") (pinfunction "IN_3") (pintype "input"))
      (node (ref "IC8") (pin "11") (pinfunction "PF1_11") (pintype "bidirectional"))
    )
    (net (code "248") (name "VOLT_SW2") (class "Default")
      (node (ref "IC33") (pin "3") (pinfunction "IN_3") (pintype "input"))
      (node (ref "IC8") (pin "12") (pinfunction "PF2_12") (pintype "bidirectional"))
    )
    (net (code "249") (name "VOLT_SW3") (class "Default")
      (node (ref "IC34") (pin "3") (pinfunction "IN_3") (pintype "input"))
      (node (ref "IC8") (pin "13") (pinfunction "PF3_13") (pintype "bidirectional"))
    )
    (net (code "250") (name "unconnected-(IC8A-PA8-Pad100)") (class "Default")
      (node (ref "IC8") (pin "100") (pinfunction "PA8_100") (pintype "bidirectional"))
    )
    (net (code "251") (name "unconnected-(IC8A-PA10-Pad102)") (class "Default")
      (node (ref "IC8") (pin "102") (pinfunction "PA10_102") (pintype "bidirectional"))
    )
    (net (code "252") (name "unconnected-(IC8A-PA11-Pad103)") (class "Default")
      (node (ref "IC8") (pin "103") (pinfunction "PA11_103") (pintype "bidirectional"))
    )
    (net (code "253") (name "unconnected-(IC8A-PA12-Pad104)") (class "Default")
      (node (ref "IC8") (pin "104") (pinfunction "PA12_104") (pintype "bidirectional"))
    )
    (net (code "254") (name "unconnected-(IC8A-PC0-Pad26)") (class "Default")
      (node (ref "IC8") (pin "26") (pinfunction "PC0_26") (pintype "bidirectional"))
    )
    (net (code "255") (name "unconnected-(IC8A-PC2-Pad28)") (class "Default")
      (node (ref "IC8") (pin "28") (pinfunction "PC2_28") (pintype "bidirectional"))
    )
    (net (code "256") (name "unconnected-(IC8A-PC3-Pad29)") (class "Default")
      (node (ref "IC8") (pin "29") (pinfunction "PC3_29") (pintype "bidirectional"))
    )
    (net (code "257") (name "unconnected-(IC8A-PD0-Pad114)") (class "Default")
      (node (ref "IC8") (pin "114") (pinfunction "PD0_114") (pintype "bidirectional"))
    )
    (net (code "258") (name "unconnected-(IC8A-PD1-Pad115)") (class "Default")
      (node (ref "IC8") (pin "115") (pinfunction "PD1_115") (pintype "bidirectional"))
    )
    (net (code "259") (name "unconnected-(IC8A-PD9-Pad78)") (class "Default")
      (node (ref "IC8") (pin "78") (pinfunction "PD9_78") (pintype "bidirectional"))
    )
    (net (code "260") (name "unconnected-(IC8A-PD10-Pad79)") (class "Default")
      (node (ref "IC8") (pin "79") (pinfunction "PD10_79") (pintype "bidirectional"))
    )
    (net (code "261") (name "unconnected-(IC8A-PD13-Pad82)") (class "Default")
      (node (ref "IC8") (pin "82") (pinfunction "PD13_82") (pintype "bidirectional"))
    )
    (net (code "262") (name "unconnected-(IC8A-PD14-Pad85)") (class "Default")
      (node (ref "IC8") (pin "85") (pinfunction "PD14_85") (pintype "bidirectional"))
    )
    (net (code "263") (name "unconnected-(IC8A-PD15-Pad86)") (class "Default")
      (node (ref "IC8") (pin "86") (pinfunction "PD15_86") (pintype "bidirectional"))
    )
    (net (code "264") (name "unconnected-(IC8B-PE0-Pad141)") (class "Default")
      (node (ref "IC8") (pin "141") (pinfunction "PE0_141") (pintype "bidirectional"))
    )
    (net (code "265") (name "unconnected-(IC8B-PE1-Pad142)") (class "Default")
      (node (ref "IC8") (pin "142") (pinfunction "PE1_142") (pintype "bidirectional"))
    )
    (net (code "266") (name "unconnected-(IC8B-PE2-Pad1)") (class "Default")
      (node (ref "IC8") (pin "1") (pinfunction "PE2_1") (pintype "bidirectional"))
    )
    (net (code "267") (name "unconnected-(IC8B-PE3-Pad2)") (class "Default")
      (node (ref "IC8") (pin "2") (pinfunction "PE3_2") (pintype "bidirectional"))
    )
    (net (code "268") (name "unconnected-(IC8B-PE4-Pad3)") (class "Default")
      (node (ref "IC8") (pin "3") (pinfunction "PE4_3") (pintype "bidirectional"))
    )
    (net (code "269") (name "unconnected-(IC8B-PE5-Pad4)") (class "Default")
      (node (ref "IC8") (pin "4") (pinfunction "PE5_4") (pintype "bidirectional"))
    )
    (net (code "270") (name "unconnected-(IC8B-PE6-Pad5)") (class "Default")
      (node (ref "IC8") (pin "5") (pinfunction "PE6_5") (pintype "bidirectional"))
    )
    (net (code "271") (name "unconnected-(IC8B-PE7-Pad58)") (class "Default")
      (node (ref "IC8") (pin "58") (pinfunction "PE7_58") (pintype "bidirectional"))
    )
    (net (code "272") (name "unconnected-(IC8B-PE8-Pad59)") (class "Default")
      (node (ref "IC8") (pin "59") (pinfunction "PE8_59") (pintype "bidirectional"))
    )
    (net (code "273") (name "unconnected-(IC8B-PE9-Pad60)") (class "Default")
      (node (ref "IC8") (pin "60") (pinfunction "PE9_60") (pintype "bidirectional"))
    )
    (net (code "274") (name "unconnected-(IC8B-PE10-Pad63)") (class "Default")
      (node (ref "IC8") (pin "63") (pinfunction "PE10_63") (pintype "bidirectional"))
    )
    (net (code "275") (name "unconnected-(IC8B-PE15-Pad68)") (class "Default")
      (node (ref "IC8") (pin "68") (pinfunction "PE15_68") (pintype "bidirectional"))
    )
    (net (code "276") (name "unconnected-(IC8B-PF4-Pad14)") (class "Default")
      (node (ref "IC8") (pin "14") (pinfunction "PF4_14") (pintype "bidirectional"))
    )
    (net (code "277") (name "unconnected-(IC8B-PF5-Pad15)") (class "Default")
      (node (ref "IC8") (pin "15") (pinfunction "PF5_15") (pintype "bidirectional"))
    )
    (net (code "278") (name "unconnected-(IC8B-PF11-Pad49)") (class "Default")
      (node (ref "IC8") (pin "49") (pinfunction "PF11_49") (pintype "bidirectional"))
    )
    (net (code "279") (name "unconnected-(IC8B-PF12-Pad50)") (class "Default")
      (node (ref "IC8") (pin "50") (pinfunction "PF12_50") (pintype "bidirectional"))
    )
    (net (code "280") (name "unconnected-(IC8B-PF13-Pad53)") (class "Default")
      (node (ref "IC8") (pin "53") (pinfunction "PF13_53") (pintype "bidirectional"))
    )
    (net (code "281") (name "unconnected-(IC8B-PF14-Pad54)") (class "Default")
      (node (ref "IC8") (pin "54") (pinfunction "PF14_54") (pintype "bidirectional"))
    )
    (net (code "282") (name "unconnected-(IC8B-PF15-Pad55)") (class "Default")
      (node (ref "IC8") (pin "55") (pinfunction "PF15_55") (pintype "bidirectional"))
    )
    (net (code "283") (name "unconnected-(IC8B-PG0-Pad56)") (class "Default")
      (node (ref "IC8") (pin "56") (pinfunction "PG0_56") (pintype "bidirectional"))
    )
    (net (code "284") (name "unconnected-(IC8B-PG1-Pad57)") (class "Default")
      (node (ref "IC8") (pin "57") (pinfunction "PG1_57") (pintype "bidirectional"))
    )
    (net (code "285") (name "unconnected-(IC8B-PG2-Pad87)") (class "Default")
      (node (ref "IC8") (pin "87") (pinfunction "PG2_87") (pintype "bidirectional"))
    )
    (net (code "286") (name "unconnected-(IC8B-PG4-Pad89)") (class "Default")
      (node (ref "IC8") (pin "89") (pinfunction "PG4_89") (pintype "bidirectional"))
    )
    (net (code "287") (name "unconnected-(IC8B-PG5-Pad90)") (class "Default")
      (node (ref "IC8") (pin "90") (pinfunction "PG5_90") (pintype "bidirectional"))
    )
    (net (code "288") (name "unconnected-(IC8B-PG8-Pad93)") (class "Default")
      (node (ref "IC8") (pin "93") (pinfunction "PG8_93") (pintype "bidirectional"))
    )
    (net (code "289") (name "unconnected-(IC8B-PG15-Pad132)") (class "Default")
      (node (ref "IC8") (pin "132") (pinfunction "PG15_132") (pintype "bidirectional"))
    )
    (net (code "290") (name "unconnected-(IC10-BOOST-Pad20)") (class "Default")
      (node (ref "IC10") (pin "20") (pinfunction "BOOST_20") (pintype "output"))
    )
    (net (code "291") (name "unconnected-(IC11-BOOST-Pad20)") (class "Default")
      (node (ref "IC11") (pin "20") (pinfunction "BOOST_20") (pintype "output"))
    )
    (net (code "292") (name "unconnected-(IC36-AUX_IN-Pad10)") (class "Default")
      (node (ref "IC36") (pin "10") (pinfunction "AUX_IN_10") (pintype "input"))
    )
    (net (code "293") (name "~{ADC_CS}") (class "Default")
      (node (ref "IC36") (pin "38") (pinfunction "~{CS}_38") (pintype "input"))
      (node (ref "RN5") (pin "1") (pinfunction "1_1") (pintype "passive"))
      (node (ref "X5") (pin "6") (pinfunction "1_6") (pintype "passive"))
    )
    (net (code "294") (name "~{DAC_ALARM}") (class "Default")
      (node (ref "IC10") (pin "3") (pinfunction "~{ALARM}_3") (pintype "output"))
      (node (ref "IC11") (pin "3") (pinfunction "~{ALARM}_3") (pintype "output"))
      (node (ref "IC8") (pin "9") (pinfunction "PC15-OSC32_OUT_9") (pintype "bidirectional"))
      (node (ref "R12") (pin "2") (pinfunction "2_2") (pintype "passive"))
    )
    (net (code "295") (name "~{DAC_CS_DUAL}") (class "Default")
      (node (ref "IC13") (pin "6") (pinfunction "~{SYNC}_6") (pintype "input"))
      (node (ref "RN4") (pin "1") (pinfunction "1_1") (pintype "passive"))
    )
    (net (code "296") (name "~{OUT_FAULT}") (class "Default")
      (node (ref "IC15") (pin "1") (pinfunction "~{FAULT}_1") (pintype "output"))
      (node (ref "IC16") (pin "1") (pinfunction "~{FAULT}_1") (pintype "output"))
      (node (ref "IC17") (pin "1") (pinfunction "~{FAULT}_1") (pintype "output"))
      (node (ref "IC18") (pin "1") (pinfunction "~{FAULT}_1") (pintype "output"))
      (node (ref "IC8") (pin "88") (pinfunction "PG3_88") (pintype "bidirectional"))
      (node (ref "R30") (pin "2") (pinfunction "2_2") (pintype "passive"))
    )
    (net (code "297") (name "~{RESET}") (class "Default")
      (node (ref "IC13") (pin "5") (pinfunction "~{CLR}_5") (pintype "input"))
      (node (ref "IC3") (pin "12") (pinfunction "B3_12") (pintype "output"))
      (node (ref "IC36") (pin "2") (pinfunction "~{RST/}PD_2") (pintype "input"))
      (node (ref "IC8") (pin "25") (pinfunction "NRST_25") (pintype "bidirectional"))
      (node (ref "R6") (pin "2") (pinfunction "2_2") (pintype "passive"))
      (node (ref "X5") (pin "4") (pinfunction "1_4") (pintype "passive"))
    )
  )
)
